# trig3_board_de0-nano_rack.net
KiCad netlist of a schematic drawn in EAGLE
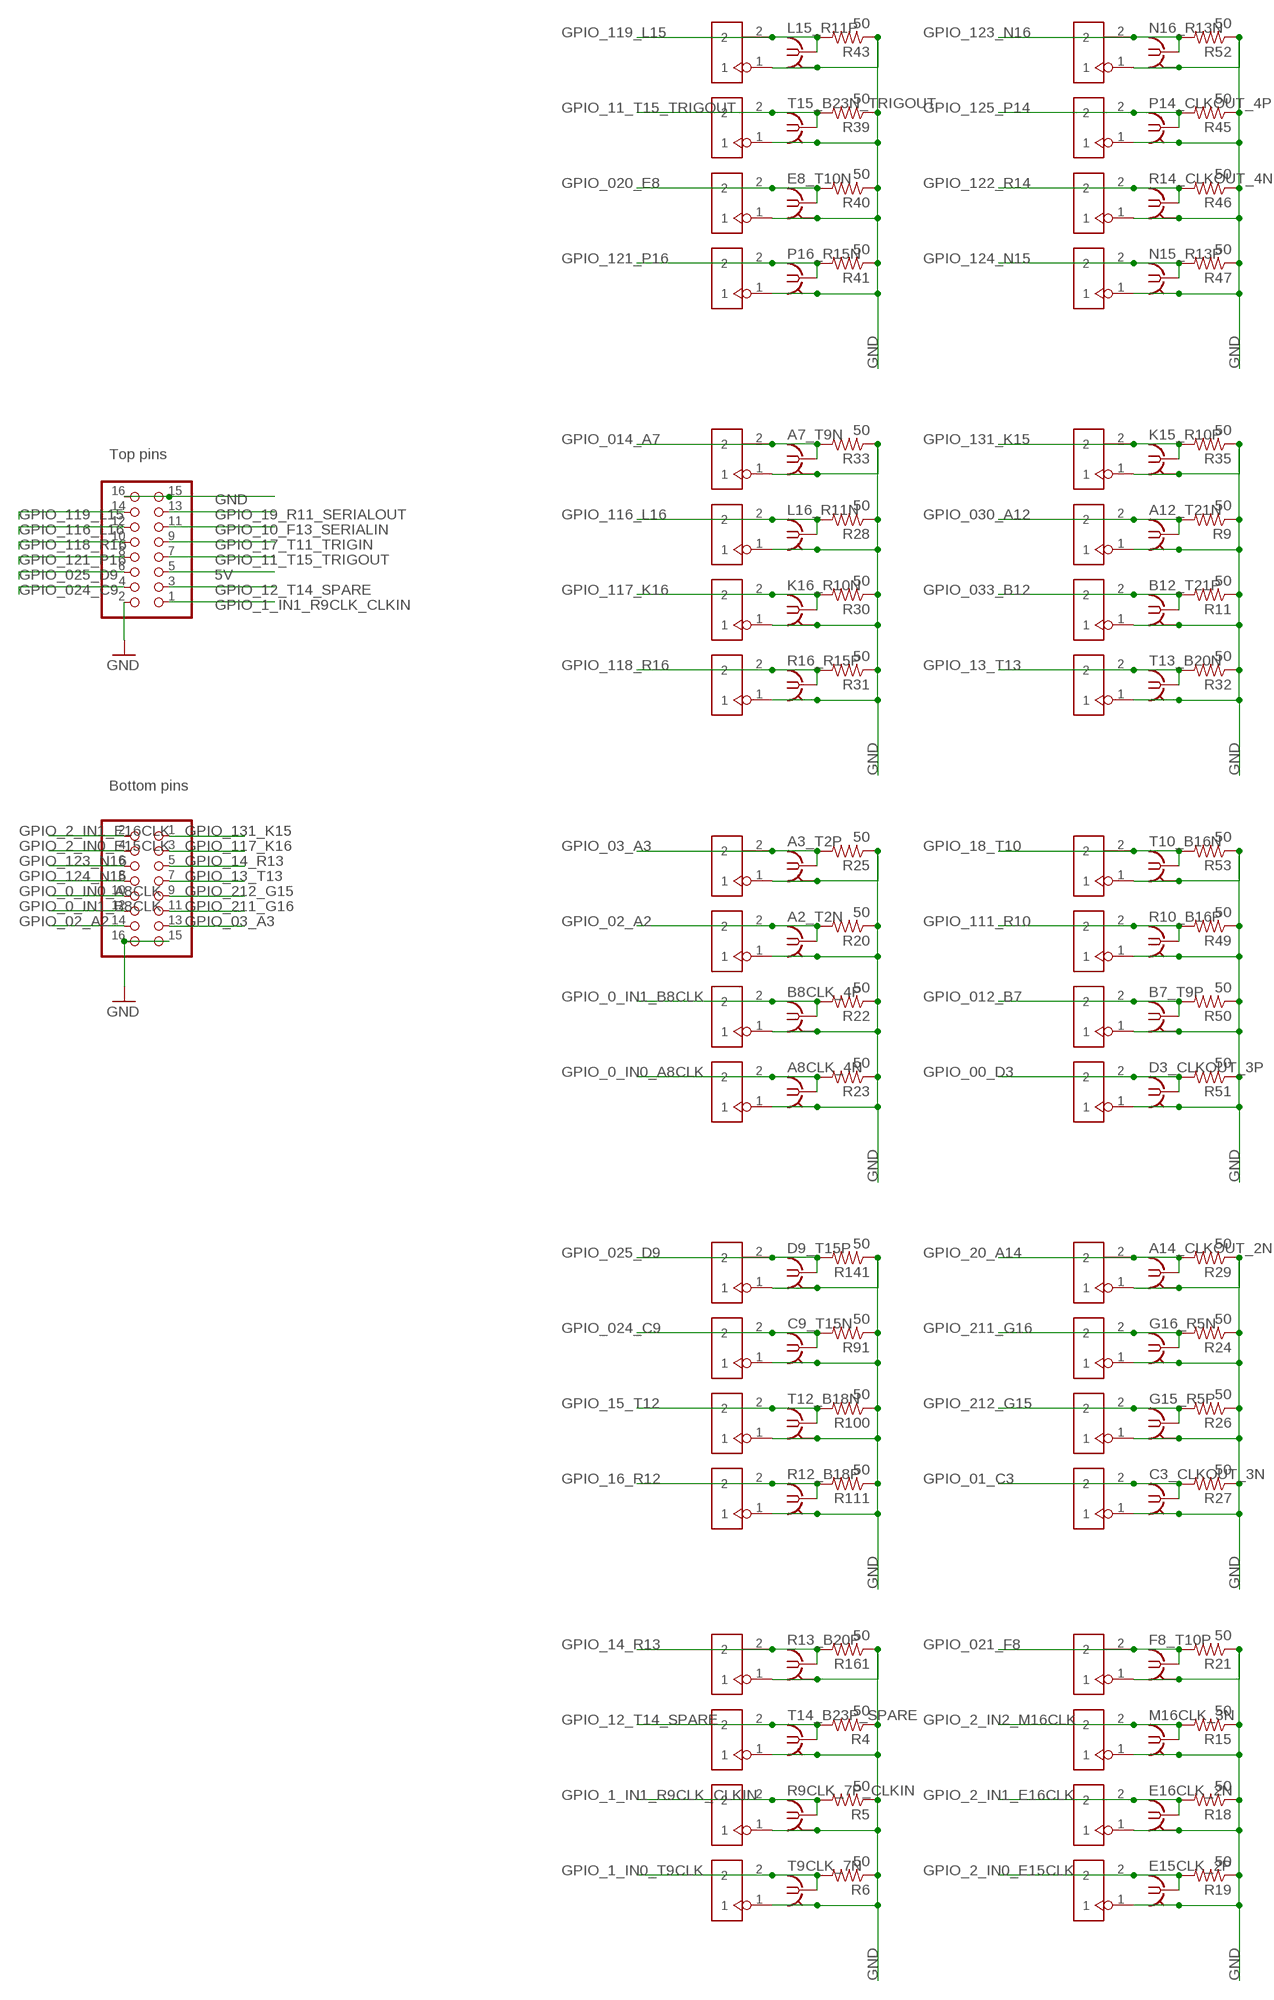
[diagram p0: schematic, sheet 1, part 1 of 3]
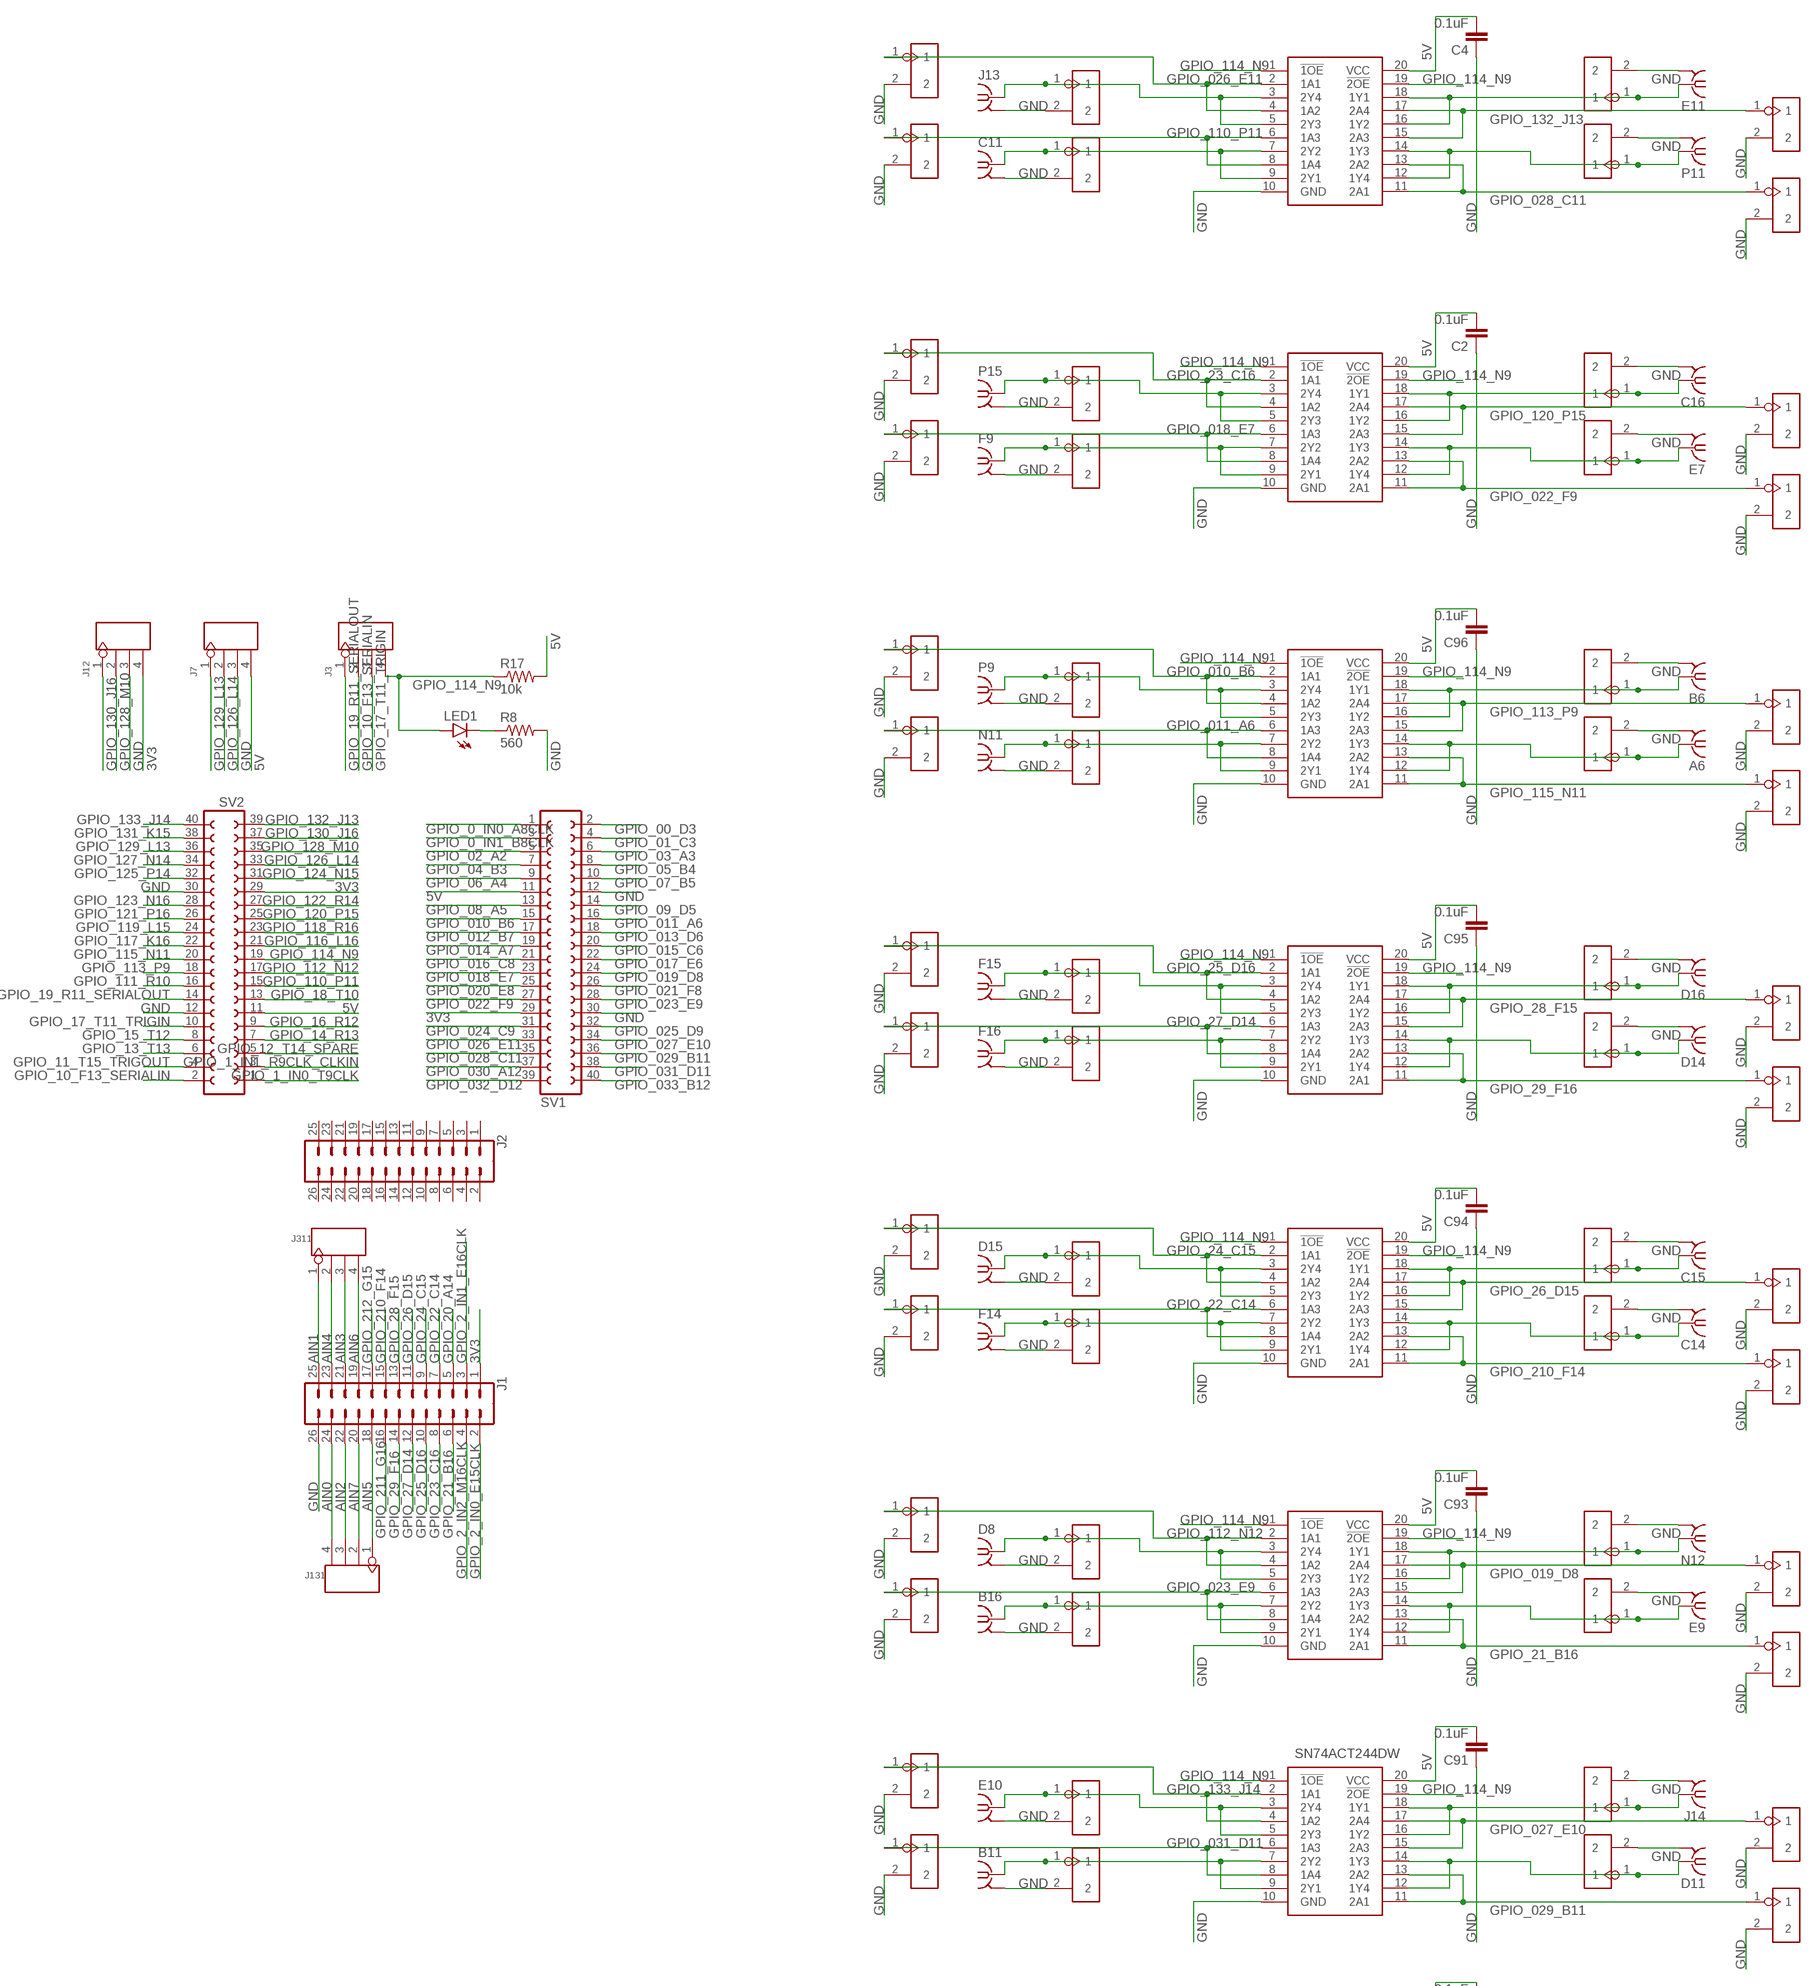
[diagram p1: schematic, sheet 1, part 2 of 3]
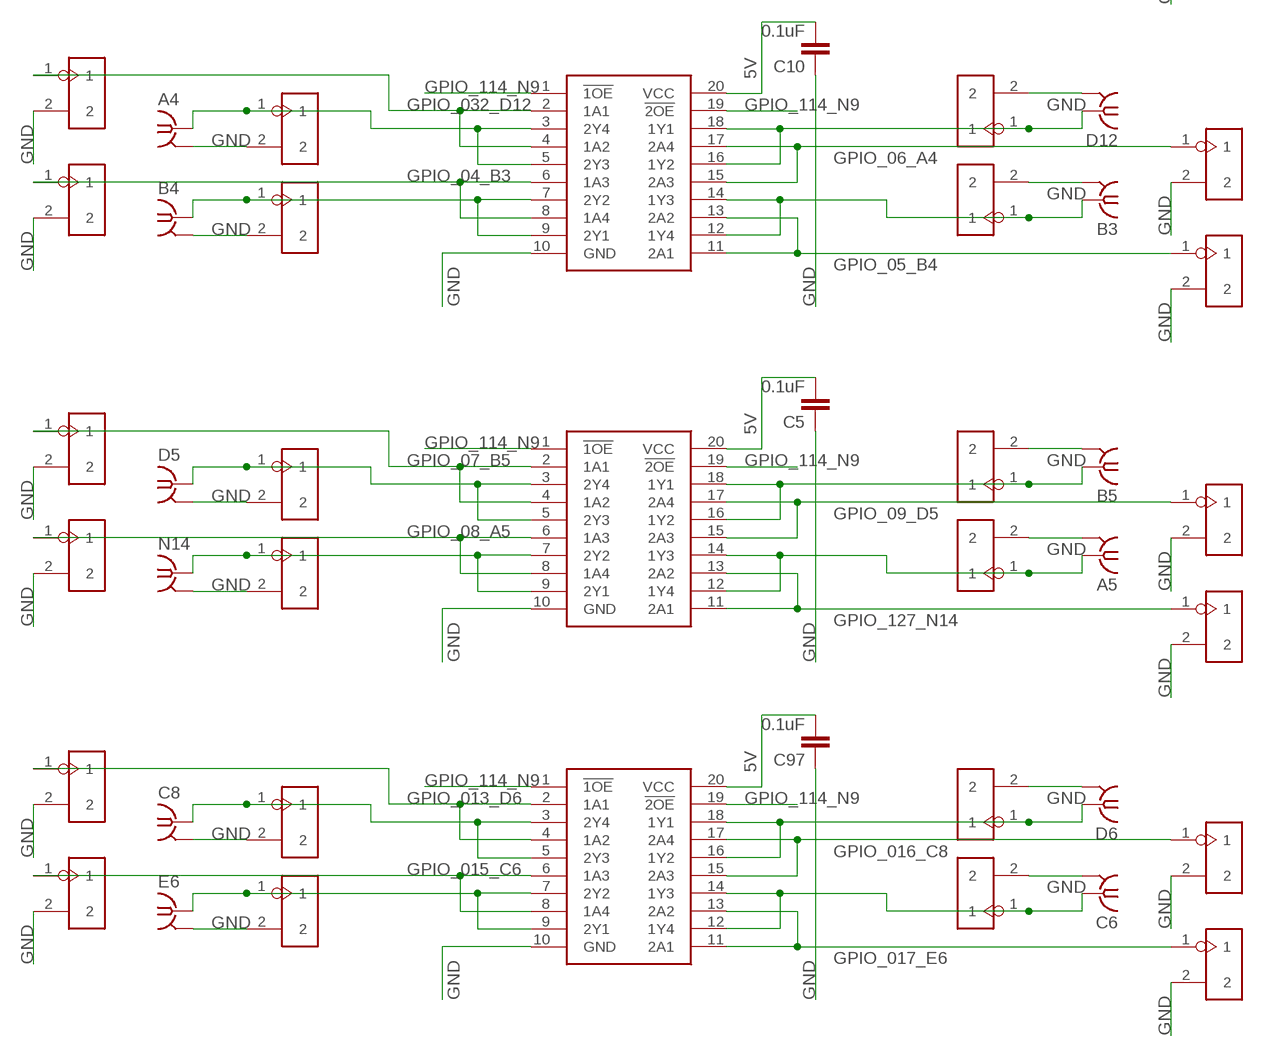
[diagram p2: schematic, sheet 1, part 3 of 3]

(export (version "E")
  (design (tool "Eeschema 10.0.6"))
  (components
    (comp (ref "A2_T2N")
      (value "BU-SMB-V")
      (footprint "eagle-import:BU-SMB-V")
      (libsource (lib "eagle-import") (part "BU-SMB-V"))
    )
    (comp (ref "A3_T2P")
      (value "BU-SMB-V")
      (footprint "eagle-import:BU-SMB-V")
      (libsource (lib "eagle-import") (part "BU-SMB-V"))
    )
    (comp (ref "A4")
      (value "BU-SMB-V")
      (footprint "eagle-import:BU-SMB-V")
      (libsource (lib "eagle-import") (part "BU-SMB-V"))
    )
    (comp (ref "A5")
      (value "BU-SMB-V")
      (footprint "eagle-import:BU-SMB-V")
      (libsource (lib "eagle-import") (part "BU-SMB-V"))
    )
    (comp (ref "A6")
      (value "BU-SMB-V")
      (footprint "eagle-import:BU-SMB-V")
      (libsource (lib "eagle-import") (part "BU-SMB-V"))
    )
    (comp (ref "A7_T9N")
      (value "BU-SMB-V")
      (footprint "eagle-import:BU-SMB-V")
      (libsource (lib "eagle-import") (part "BU-SMB-V"))
    )
    (comp (ref "A8CLK_4N")
      (value "BU-SMB-V")
      (footprint "eagle-import:BU-SMB-V")
      (libsource (lib "eagle-import") (part "BU-SMB-V"))
    )
    (comp (ref "A12_T21N")
      (value "BU-SMB-V")
      (footprint "eagle-import:BU-SMB-V")
      (libsource (lib "eagle-import") (part "BU-SMB-V"))
    )
    (comp (ref "A14_CLKOUT_2N")
      (value "BU-SMB-V")
      (footprint "eagle-import:BU-SMB-V")
      (libsource (lib "eagle-import") (part "BU-SMB-V"))
    )
    (comp (ref "B3")
      (value "BU-SMB-V")
      (footprint "eagle-import:BU-SMB-V")
      (libsource (lib "eagle-import") (part "BU-SMB-V"))
    )
    (comp (ref "B4")
      (value "BU-SMB-V")
      (footprint "eagle-import:BU-SMB-V")
      (libsource (lib "eagle-import") (part "BU-SMB-V"))
    )
    (comp (ref "B5")
      (value "BU-SMB-V")
      (footprint "eagle-import:BU-SMB-V")
      (libsource (lib "eagle-import") (part "BU-SMB-V"))
    )
    (comp (ref "B6")
      (value "BU-SMB-V")
      (footprint "eagle-import:BU-SMB-V")
      (libsource (lib "eagle-import") (part "BU-SMB-V"))
    )
    (comp (ref "B7_T9P")
      (value "BU-SMB-V")
      (footprint "eagle-import:BU-SMB-V")
      (libsource (lib "eagle-import") (part "BU-SMB-V"))
    )
    (comp (ref "B8CLK_4P")
      (value "BU-SMB-V")
      (footprint "eagle-import:BU-SMB-V")
      (libsource (lib "eagle-import") (part "BU-SMB-V"))
    )
    (comp (ref "B11")
      (value "BU-SMB-V")
      (footprint "eagle-import:BU-SMB-V")
      (libsource (lib "eagle-import") (part "BU-SMB-V"))
    )
    (comp (ref "B12_T21P")
      (value "BU-SMB-V")
      (footprint "eagle-import:BU-SMB-V")
      (libsource (lib "eagle-import") (part "BU-SMB-V"))
    )
    (comp (ref "B16")
      (value "BU-SMB-V")
      (footprint "eagle-import:BU-SMB-V")
      (libsource (lib "eagle-import") (part "BU-SMB-V"))
    )
    (comp (ref "C2")
      (value "0.1uF")
      (footprint "eagle-import:0805")
      (libsource (lib "eagle-import") (part "CAP0805"))
    )
    (comp (ref "C3_CLKOUT_3N")
      (value "BU-SMB-V")
      (footprint "eagle-import:BU-SMB-V")
      (libsource (lib "eagle-import") (part "BU-SMB-V"))
    )
    (comp (ref "C4")
      (value "0.1uF")
      (footprint "eagle-import:0805")
      (libsource (lib "eagle-import") (part "CAP0805"))
    )
    (comp (ref "C5")
      (value "0.1uF")
      (footprint "eagle-import:0805")
      (libsource (lib "eagle-import") (part "CAP0805"))
    )
    (comp (ref "C6")
      (value "BU-SMB-V")
      (footprint "eagle-import:BU-SMB-V")
      (libsource (lib "eagle-import") (part "BU-SMB-V"))
    )
    (comp (ref "C8")
      (value "BU-SMB-V")
      (footprint "eagle-import:BU-SMB-V")
      (libsource (lib "eagle-import") (part "BU-SMB-V"))
    )
    (comp (ref "C9_T15N")
      (value "BU-SMB-V")
      (footprint "eagle-import:BU-SMB-V")
      (libsource (lib "eagle-import") (part "BU-SMB-V"))
    )
    (comp (ref "C10")
      (value "0.1uF")
      (footprint "eagle-import:0805")
      (libsource (lib "eagle-import") (part "CAP0805"))
    )
    (comp (ref "C11")
      (value "BU-SMB-V")
      (footprint "eagle-import:BU-SMB-V")
      (libsource (lib "eagle-import") (part "BU-SMB-V"))
    )
    (comp (ref "C14")
      (value "BU-SMB-V")
      (footprint "eagle-import:BU-SMB-V")
      (libsource (lib "eagle-import") (part "BU-SMB-V"))
    )
    (comp (ref "C15")
      (value "BU-SMB-V")
      (footprint "eagle-import:BU-SMB-V")
      (libsource (lib "eagle-import") (part "BU-SMB-V"))
    )
    (comp (ref "C16")
      (value "BU-SMB-V")
      (footprint "eagle-import:BU-SMB-V")
      (libsource (lib "eagle-import") (part "BU-SMB-V"))
    )
    (comp (ref "C91")
      (value "0.1uF")
      (footprint "eagle-import:0805")
      (libsource (lib "eagle-import") (part "CAP0805"))
    )
    (comp (ref "C93")
      (value "0.1uF")
      (footprint "eagle-import:0805")
      (libsource (lib "eagle-import") (part "CAP0805"))
    )
    (comp (ref "C94")
      (value "0.1uF")
      (footprint "eagle-import:0805")
      (libsource (lib "eagle-import") (part "CAP0805"))
    )
    (comp (ref "C95")
      (value "0.1uF")
      (footprint "eagle-import:0805")
      (libsource (lib "eagle-import") (part "CAP0805"))
    )
    (comp (ref "C96")
      (value "0.1uF")
      (footprint "eagle-import:0805")
      (libsource (lib "eagle-import") (part "CAP0805"))
    )
    (comp (ref "C97")
      (value "0.1uF")
      (footprint "eagle-import:0805")
      (libsource (lib "eagle-import") (part "CAP0805"))
    )
    (comp (ref "D3_CLKOUT_3P")
      (value "BU-SMB-V")
      (footprint "eagle-import:BU-SMB-V")
      (libsource (lib "eagle-import") (part "BU-SMB-V"))
    )
    (comp (ref "D5")
      (value "BU-SMB-V")
      (footprint "eagle-import:BU-SMB-V")
      (libsource (lib "eagle-import") (part "BU-SMB-V"))
    )
    (comp (ref "D6")
      (value "BU-SMB-V")
      (footprint "eagle-import:BU-SMB-V")
      (libsource (lib "eagle-import") (part "BU-SMB-V"))
    )
    (comp (ref "D8")
      (value "BU-SMB-V")
      (footprint "eagle-import:BU-SMB-V")
      (libsource (lib "eagle-import") (part "BU-SMB-V"))
    )
    (comp (ref "D9_T15P")
      (value "BU-SMB-V")
      (footprint "eagle-import:BU-SMB-V")
      (libsource (lib "eagle-import") (part "BU-SMB-V"))
    )
    (comp (ref "D11")
      (value "BU-SMB-V")
      (footprint "eagle-import:BU-SMB-V")
      (libsource (lib "eagle-import") (part "BU-SMB-V"))
    )
    (comp (ref "D12")
      (value "BU-SMB-V")
      (footprint "eagle-import:BU-SMB-V")
      (libsource (lib "eagle-import") (part "BU-SMB-V"))
    )
    (comp (ref "D14")
      (value "BU-SMB-V")
      (footprint "eagle-import:BU-SMB-V")
      (libsource (lib "eagle-import") (part "BU-SMB-V"))
    )
    (comp (ref "D15")
      (value "BU-SMB-V")
      (footprint "eagle-import:BU-SMB-V")
      (libsource (lib "eagle-import") (part "BU-SMB-V"))
    )
    (comp (ref "D16")
      (value "BU-SMB-V")
      (footprint "eagle-import:BU-SMB-V")
      (libsource (lib "eagle-import") (part "BU-SMB-V"))
    )
    (comp (ref "E6")
      (value "BU-SMB-V")
      (footprint "eagle-import:BU-SMB-V")
      (libsource (lib "eagle-import") (part "BU-SMB-V"))
    )
    (comp (ref "E7")
      (value "BU-SMB-V")
      (footprint "eagle-import:BU-SMB-V")
      (libsource (lib "eagle-import") (part "BU-SMB-V"))
    )
    (comp (ref "E8_T10N")
      (value "BU-SMB-V")
      (footprint "eagle-import:BU-SMB-V")
      (libsource (lib "eagle-import") (part "BU-SMB-V"))
    )
    (comp (ref "E9")
      (value "BU-SMB-V")
      (footprint "eagle-import:BU-SMB-V")
      (libsource (lib "eagle-import") (part "BU-SMB-V"))
    )
    (comp (ref "E10")
      (value "BU-SMB-V")
      (footprint "eagle-import:BU-SMB-V")
      (libsource (lib "eagle-import") (part "BU-SMB-V"))
    )
    (comp (ref "E11")
      (value "BU-SMB-V")
      (footprint "eagle-import:BU-SMB-V")
      (libsource (lib "eagle-import") (part "BU-SMB-V"))
    )
    (comp (ref "E15CLK_2P")
      (value "BU-SMB-V")
      (footprint "eagle-import:BU-SMB-V")
      (libsource (lib "eagle-import") (part "BU-SMB-V"))
    )
    (comp (ref "E16CLK_2N")
      (value "BU-SMB-V")
      (footprint "eagle-import:BU-SMB-V")
      (libsource (lib "eagle-import") (part "BU-SMB-V"))
    )
    (comp (ref "F8_T10P")
      (value "BU-SMB-V")
      (footprint "eagle-import:BU-SMB-V")
      (libsource (lib "eagle-import") (part "BU-SMB-V"))
    )
    (comp (ref "F9")
      (value "BU-SMB-V")
      (footprint "eagle-import:BU-SMB-V")
      (libsource (lib "eagle-import") (part "BU-SMB-V"))
    )
    (comp (ref "F14")
      (value "BU-SMB-V")
      (footprint "eagle-import:BU-SMB-V")
      (libsource (lib "eagle-import") (part "BU-SMB-V"))
    )
    (comp (ref "F15")
      (value "BU-SMB-V")
      (footprint "eagle-import:BU-SMB-V")
      (libsource (lib "eagle-import") (part "BU-SMB-V"))
    )
    (comp (ref "F16")
      (value "BU-SMB-V")
      (footprint "eagle-import:BU-SMB-V")
      (libsource (lib "eagle-import") (part "BU-SMB-V"))
    )
    (comp (ref "G15_R5P")
      (value "BU-SMB-V")
      (footprint "eagle-import:BU-SMB-V")
      (libsource (lib "eagle-import") (part "BU-SMB-V"))
    )
    (comp (ref "G16_R5N")
      (value "BU-SMB-V")
      (footprint "eagle-import:BU-SMB-V")
      (libsource (lib "eagle-import") (part "BU-SMB-V"))
    )
    (comp (ref "J1")
      (value "M13X22X13")
      (footprint "eagle-import:2X13")
      (libsource (lib "eagle-import") (part "M13X22X13"))
    )
    (comp (ref "J2")
      (value "M13X22X13")
      (footprint "eagle-import:2X13")
      (libsource (lib "eagle-import") (part "M13X22X13"))
    )
    (comp (ref "J3")
      (value "4p-2.54")
      (footprint "eagle-import:H4-2.54")
      (fields (field (name "MPN") "F185-1104A1BSYA1"))
      (libsource (lib "eagle-import") (part "DIP-BLACK-FEMALE-HEADER-VERT(4P-2.54)"))
    )
    (comp (ref "J4")
      (value "2p-2.54")
      (footprint "eagle-import:H2-2.54")
      (fields (field (name "MPN") "P125-1102A0BS116A1"))
      (libsource (lib "eagle-import") (part "DIP-BLACK-MALE-HEADER-VERT(2P-2.54)"))
    )
    (comp (ref "J5")
      (value "2p-2.54")
      (footprint "eagle-import:H2-2.54")
      (fields (field (name "MPN") "P125-1102A0BS116A1"))
      (libsource (lib "eagle-import") (part "DIP-BLACK-MALE-HEADER-VERT(2P-2.54)"))
    )
    (comp (ref "J6")
      (value "2p-2.54")
      (footprint "eagle-import:H2-2.54")
      (fields (field (name "MPN") "P125-1102A0BS116A1"))
      (libsource (lib "eagle-import") (part "DIP-BLACK-MALE-HEADER-VERT(2P-2.54)"))
    )
    (comp (ref "J7")
      (value "4p-2.54")
      (footprint "eagle-import:H4-2.54")
      (fields (field (name "MPN") "F185-1104A1BSYA1"))
      (libsource (lib "eagle-import") (part "DIP-BLACK-FEMALE-HEADER-VERT(4P-2.54)"))
    )
    (comp (ref "J8")
      (value "2p-2.54")
      (footprint "eagle-import:H2-2.54")
      (fields (field (name "MPN") "P125-1102A0BS116A1"))
      (libsource (lib "eagle-import") (part "DIP-BLACK-MALE-HEADER-VERT(2P-2.54)"))
    )
    (comp (ref "J9")
      (value "2p-2.54")
      (footprint "eagle-import:H2-2.54")
      (fields (field (name "MPN") "P125-1102A0BS116A1"))
      (libsource (lib "eagle-import") (part "DIP-BLACK-MALE-HEADER-VERT(2P-2.54)"))
    )
    (comp (ref "J10")
      (value "2p-2.54")
      (footprint "eagle-import:H2-2.54")
      (fields (field (name "MPN") "P125-1102A0BS116A1"))
      (libsource (lib "eagle-import") (part "DIP-BLACK-MALE-HEADER-VERT(2P-2.54)"))
    )
    (comp (ref "J11")
      (value "2p-2.54")
      (footprint "eagle-import:H2-2.54")
      (fields (field (name "MPN") "P125-1102A0BS116A1"))
      (libsource (lib "eagle-import") (part "DIP-BLACK-MALE-HEADER-VERT(2P-2.54)"))
    )
    (comp (ref "J12")
      (value "4p-2.54")
      (footprint "eagle-import:H4-2.54")
      (fields (field (name "MPN") "F185-1104A1BSYA1"))
      (libsource (lib "eagle-import") (part "DIP-BLACK-FEMALE-HEADER-VERT(4P-2.54)"))
    )
    (comp (ref "J13")
      (value "BU-SMB-V")
      (footprint "eagle-import:BU-SMB-V")
      (libsource (lib "eagle-import") (part "BU-SMB-V"))
    )
    (comp (ref "J14")
      (value "BU-SMB-V")
      (footprint "eagle-import:BU-SMB-V")
      (libsource (lib "eagle-import") (part "BU-SMB-V"))
    )
    (comp (ref "J15")
      (value "2p-2.54")
      (footprint "eagle-import:H2-2.54")
      (fields (field (name "MPN") "P125-1102A0BS116A1"))
      (libsource (lib "eagle-import") (part "DIP-BLACK-MALE-HEADER-VERT(2P-2.54)"))
    )
    (comp (ref "J16")
      (value "2p-2.54")
      (footprint "eagle-import:H2-2.54")
      (fields (field (name "MPN") "P125-1102A0BS116A1"))
      (libsource (lib "eagle-import") (part "DIP-BLACK-MALE-HEADER-VERT(2P-2.54)"))
    )
    (comp (ref "J17")
      (value "2p-2.54")
      (footprint "eagle-import:H2-2.54")
      (fields (field (name "MPN") "P125-1102A0BS116A1"))
      (libsource (lib "eagle-import") (part "DIP-BLACK-MALE-HEADER-VERT(2P-2.54)"))
    )
    (comp (ref "J18")
      (value "2p-2.54")
      (footprint "eagle-import:H2-2.54")
      (fields (field (name "MPN") "P125-1102A0BS116A1"))
      (libsource (lib "eagle-import") (part "DIP-BLACK-MALE-HEADER-VERT(2P-2.54)"))
    )
    (comp (ref "J22")
      (value "2p-2.54")
      (footprint "eagle-import:H2-2.54")
      (fields (field (name "MPN") "P125-1102A0BS116A1"))
      (libsource (lib "eagle-import") (part "DIP-BLACK-MALE-HEADER-VERT(2P-2.54)"))
    )
    (comp (ref "J23")
      (value "2p-2.54")
      (footprint "eagle-import:H2-2.54")
      (fields (field (name "MPN") "P125-1102A0BS116A1"))
      (libsource (lib "eagle-import") (part "DIP-BLACK-MALE-HEADER-VERT(2P-2.54)"))
    )
    (comp (ref "J24")
      (value "2p-2.54")
      (footprint "eagle-import:H2-2.54")
      (fields (field (name "MPN") "P125-1102A0BS116A1"))
      (libsource (lib "eagle-import") (part "DIP-BLACK-MALE-HEADER-VERT(2P-2.54)"))
    )
    (comp (ref "J25")
      (value "2p-2.54")
      (footprint "eagle-import:H2-2.54")
      (fields (field (name "MPN") "P125-1102A0BS116A1"))
      (libsource (lib "eagle-import") (part "DIP-BLACK-MALE-HEADER-VERT(2P-2.54)"))
    )
    (comp (ref "J28")
      (value "2p-2.54")
      (footprint "eagle-import:H2-2.54")
      (fields (field (name "MPN") "P125-1102A0BS116A1"))
      (libsource (lib "eagle-import") (part "DIP-BLACK-MALE-HEADER-VERT(2P-2.54)"))
    )
    (comp (ref "J29")
      (value "2p-2.54")
      (footprint "eagle-import:H2-2.54")
      (fields (field (name "MPN") "P125-1102A0BS116A1"))
      (libsource (lib "eagle-import") (part "DIP-BLACK-MALE-HEADER-VERT(2P-2.54)"))
    )
    (comp (ref "J30")
      (value "2p-2.54")
      (footprint "eagle-import:H2-2.54")
      (fields (field (name "MPN") "P125-1102A0BS116A1"))
      (libsource (lib "eagle-import") (part "DIP-BLACK-MALE-HEADER-VERT(2P-2.54)"))
    )
    (comp (ref "J31")
      (value "2p-2.54")
      (footprint "eagle-import:H2-2.54")
      (fields (field (name "MPN") "P125-1102A0BS116A1"))
      (libsource (lib "eagle-import") (part "DIP-BLACK-MALE-HEADER-VERT(2P-2.54)"))
    )
    (comp (ref "J32")
      (value "2p-2.54")
      (footprint "eagle-import:H2-2.54")
      (fields (field (name "MPN") "P125-1102A0BS116A1"))
      (libsource (lib "eagle-import") (part "DIP-BLACK-MALE-HEADER-VERT(2P-2.54)"))
    )
    (comp (ref "J33")
      (value "2p-2.54")
      (footprint "eagle-import:H2-2.54")
      (fields (field (name "MPN") "P125-1102A0BS116A1"))
      (libsource (lib "eagle-import") (part "DIP-BLACK-MALE-HEADER-VERT(2P-2.54)"))
    )
    (comp (ref "J34")
      (value "2p-2.54")
      (footprint "eagle-import:H2-2.54")
      (fields (field (name "MPN") "P125-1102A0BS116A1"))
      (libsource (lib "eagle-import") (part "DIP-BLACK-MALE-HEADER-VERT(2P-2.54)"))
    )
    (comp (ref "J35")
      (value "2p-2.54")
      (footprint "eagle-import:H2-2.54")
      (fields (field (name "MPN") "P125-1102A0BS116A1"))
      (libsource (lib "eagle-import") (part "DIP-BLACK-MALE-HEADER-VERT(2P-2.54)"))
    )
    (comp (ref "J36")
      (value "2p-2.54")
      (footprint "eagle-import:H2-2.54")
      (fields (field (name "MPN") "P125-1102A0BS116A1"))
      (libsource (lib "eagle-import") (part "DIP-BLACK-MALE-HEADER-VERT(2P-2.54)"))
    )
    (comp (ref "J37")
      (value "2p-2.54")
      (footprint "eagle-import:H2-2.54")
      (fields (field (name "MPN") "P125-1102A0BS116A1"))
      (libsource (lib "eagle-import") (part "DIP-BLACK-MALE-HEADER-VERT(2P-2.54)"))
    )
    (comp (ref "J38")
      (value "2p-2.54")
      (footprint "eagle-import:H2-2.54")
      (fields (field (name "MPN") "P125-1102A0BS116A1"))
      (libsource (lib "eagle-import") (part "DIP-BLACK-MALE-HEADER-VERT(2P-2.54)"))
    )
    (comp (ref "J39")
      (value "2p-2.54")
      (footprint "eagle-import:H2-2.54")
      (fields (field (name "MPN") "P125-1102A0BS116A1"))
      (libsource (lib "eagle-import") (part "DIP-BLACK-MALE-HEADER-VERT(2P-2.54)"))
    )
    (comp (ref "J40")
      (value "2p-2.54")
      (footprint "eagle-import:H2-2.54")
      (fields (field (name "MPN") "P125-1102A0BS116A1"))
      (libsource (lib "eagle-import") (part "DIP-BLACK-MALE-HEADER-VERT(2P-2.54)"))
    )
    (comp (ref "J41")
      (value "2p-2.54")
      (footprint "eagle-import:H2-2.54")
      (fields (field (name "MPN") "P125-1102A0BS116A1"))
      (libsource (lib "eagle-import") (part "DIP-BLACK-MALE-HEADER-VERT(2P-2.54)"))
    )
    (comp (ref "J42")
      (value "2p-2.54")
      (footprint "eagle-import:H2-2.54")
      (fields (field (name "MPN") "P125-1102A0BS116A1"))
      (libsource (lib "eagle-import") (part "DIP-BLACK-MALE-HEADER-VERT(2P-2.54)"))
    )
    (comp (ref "J43")
      (value "2p-2.54")
      (footprint "eagle-import:H2-2.54")
      (fields (field (name "MPN") "P125-1102A0BS116A1"))
      (libsource (lib "eagle-import") (part "DIP-BLACK-MALE-HEADER-VERT(2P-2.54)"))
    )
    (comp (ref "J48")
      (value "2p-2.54")
      (footprint "eagle-import:H2-2.54")
      (fields (field (name "MPN") "P125-1102A0BS116A1"))
      (libsource (lib "eagle-import") (part "DIP-BLACK-MALE-HEADER-VERT(2P-2.54)"))
    )
    (comp (ref "J49")
      (value "2p-2.54")
      (footprint "eagle-import:H2-2.54")
      (fields (field (name "MPN") "P125-1102A0BS116A1"))
      (libsource (lib "eagle-import") (part "DIP-BLACK-MALE-HEADER-VERT(2P-2.54)"))
    )
    (comp (ref "J50")
      (value "2p-2.54")
      (footprint "eagle-import:H2-2.54")
      (fields (field (name "MPN") "P125-1102A0BS116A1"))
      (libsource (lib "eagle-import") (part "DIP-BLACK-MALE-HEADER-VERT(2P-2.54)"))
    )
    (comp (ref "J51")
      (value "2p-2.54")
      (footprint "eagle-import:H2-2.54")
      (fields (field (name "MPN") "P125-1102A0BS116A1"))
      (libsource (lib "eagle-import") (part "DIP-BLACK-MALE-HEADER-VERT(2P-2.54)"))
    )
    (comp (ref "J52")
      (value "2p-2.54")
      (footprint "eagle-import:H2-2.54")
      (fields (field (name "MPN") "P125-1102A0BS116A1"))
      (libsource (lib "eagle-import") (part "DIP-BLACK-MALE-HEADER-VERT(2P-2.54)"))
    )
    (comp (ref "J53")
      (value "2p-2.54")
      (footprint "eagle-import:H2-2.54")
      (fields (field (name "MPN") "P125-1102A0BS116A1"))
      (libsource (lib "eagle-import") (part "DIP-BLACK-MALE-HEADER-VERT(2P-2.54)"))
    )
    (comp (ref "J54")
      (value "2p-2.54")
      (footprint "eagle-import:H2-2.54")
      (fields (field (name "MPN") "P125-1102A0BS116A1"))
      (libsource (lib "eagle-import") (part "DIP-BLACK-MALE-HEADER-VERT(2P-2.54)"))
    )
    (comp (ref "J55")
      (value "2p-2.54")
      (footprint "eagle-import:H2-2.54")
      (fields (field (name "MPN") "P125-1102A0BS116A1"))
      (libsource (lib "eagle-import") (part "DIP-BLACK-MALE-HEADER-VERT(2P-2.54)"))
    )
    (comp (ref "J131")
      (value "4p-2.54")
      (footprint "eagle-import:H4-2.54")
      (fields (field (name "MPN") "F185-1104A1BSYA1"))
      (libsource (lib "eagle-import") (part "DIP-BLACK-FEMALE-HEADER-VERT(4P-2.54)"))
    )
    (comp (ref "J141")
      (value "2p-2.54")
      (footprint "eagle-import:H2-2.54")
      (fields (field (name "MPN") "P125-1102A0BS116A1"))
      (libsource (lib "eagle-import") (part "DIP-BLACK-MALE-HEADER-VERT(2P-2.54)"))
    )
    (comp (ref "J311")
      (value "4p-2.54")
      (footprint "eagle-import:H4-2.54")
      (fields (field (name "MPN") "F185-1104A1BSYA1"))
      (libsource (lib "eagle-import") (part "DIP-BLACK-FEMALE-HEADER-VERT(4P-2.54)"))
    )
    (comp (ref "K15_R10P")
      (value "BU-SMB-V")
      (footprint "eagle-import:BU-SMB-V")
      (libsource (lib "eagle-import") (part "BU-SMB-V"))
    )
    (comp (ref "K16_R10N")
      (value "BU-SMB-V")
      (footprint "eagle-import:BU-SMB-V")
      (libsource (lib "eagle-import") (part "BU-SMB-V"))
    )
    (comp (ref "L15_R11P")
      (value "BU-SMB-V")
      (footprint "eagle-import:BU-SMB-V")
      (libsource (lib "eagle-import") (part "BU-SMB-V"))
    )
    (comp (ref "L16_R11N")
      (value "BU-SMB-V")
      (footprint "eagle-import:BU-SMB-V")
      (libsource (lib "eagle-import") (part "BU-SMB-V"))
    )
    (comp (ref "LED1")
      (value "red")
      (footprint "eagle-import:CHIP-LED0805")
      (libsource (lib "eagle-import") (part "LEDCHIP-LED0805"))
    )
    (comp (ref "M16CLK_3N")
      (value "BU-SMB-V")
      (footprint "eagle-import:BU-SMB-V")
      (libsource (lib "eagle-import") (part "BU-SMB-V"))
    )
    (comp (ref "N11")
      (value "BU-SMB-V")
      (footprint "eagle-import:BU-SMB-V")
      (libsource (lib "eagle-import") (part "BU-SMB-V"))
    )
    (comp (ref "N12")
      (value "BU-SMB-V")
      (footprint "eagle-import:BU-SMB-V")
      (libsource (lib "eagle-import") (part "BU-SMB-V"))
    )
    (comp (ref "N14")
      (value "BU-SMB-V")
      (footprint "eagle-import:BU-SMB-V")
      (libsource (lib "eagle-import") (part "BU-SMB-V"))
    )
    (comp (ref "N15_R13P")
      (value "BU-SMB-V")
      (footprint "eagle-import:BU-SMB-V")
      (libsource (lib "eagle-import") (part "BU-SMB-V"))
    )
    (comp (ref "N16_R13N")
      (value "BU-SMB-V")
      (footprint "eagle-import:BU-SMB-V")
      (libsource (lib "eagle-import") (part "BU-SMB-V"))
    )
    (comp (ref "OJ1")
      (value "2p-2.54")
      (footprint "eagle-import:H2-2.54")
      (fields (field (name "MPN") "P125-1102A0BS116A1"))
      (libsource (lib "eagle-import") (part "DIP-BLACK-MALE-HEADER-VERT(2P-2.54)"))
    )
    (comp (ref "OJ2")
      (value "2p-2.54")
      (footprint "eagle-import:H2-2.54")
      (fields (field (name "MPN") "P125-1102A0BS116A1"))
      (libsource (lib "eagle-import") (part "DIP-BLACK-MALE-HEADER-VERT(2P-2.54)"))
    )
    (comp (ref "OJ3")
      (value "2p-2.54")
      (footprint "eagle-import:H2-2.54")
      (fields (field (name "MPN") "P125-1102A0BS116A1"))
      (libsource (lib "eagle-import") (part "DIP-BLACK-MALE-HEADER-VERT(2P-2.54)"))
    )
    (comp (ref "OJ4")
      (value "2p-2.54")
      (footprint "eagle-import:H2-2.54")
      (fields (field (name "MPN") "P125-1102A0BS116A1"))
      (libsource (lib "eagle-import") (part "DIP-BLACK-MALE-HEADER-VERT(2P-2.54)"))
    )
    (comp (ref "OJ5")
      (value "2p-2.54")
      (footprint "eagle-import:H2-2.54")
      (fields (field (name "MPN") "P125-1102A0BS116A1"))
      (libsource (lib "eagle-import") (part "DIP-BLACK-MALE-HEADER-VERT(2P-2.54)"))
    )
    (comp (ref "OJ6")
      (value "2p-2.54")
      (footprint "eagle-import:H2-2.54")
      (fields (field (name "MPN") "P125-1102A0BS116A1"))
      (libsource (lib "eagle-import") (part "DIP-BLACK-MALE-HEADER-VERT(2P-2.54)"))
    )
    (comp (ref "OJ7")
      (value "2p-2.54")
      (footprint "eagle-import:H2-2.54")
      (fields (field (name "MPN") "P125-1102A0BS116A1"))
      (libsource (lib "eagle-import") (part "DIP-BLACK-MALE-HEADER-VERT(2P-2.54)"))
    )
    (comp (ref "OJ8")
      (value "2p-2.54")
      (footprint "eagle-import:H2-2.54")
      (fields (field (name "MPN") "P125-1102A0BS116A1"))
      (libsource (lib "eagle-import") (part "DIP-BLACK-MALE-HEADER-VERT(2P-2.54)"))
    )
    (comp (ref "OJ17")
      (value "2p-2.54")
      (footprint "eagle-import:H2-2.54")
      (fields (field (name "MPN") "P125-1102A0BS116A1"))
      (libsource (lib "eagle-import") (part "DIP-BLACK-MALE-HEADER-VERT(2P-2.54)"))
    )
    (comp (ref "OJ18")
      (value "2p-2.54")
      (footprint "eagle-import:H2-2.54")
      (fields (field (name "MPN") "P125-1102A0BS116A1"))
      (libsource (lib "eagle-import") (part "DIP-BLACK-MALE-HEADER-VERT(2P-2.54)"))
    )
    (comp (ref "OJ19")
      (value "2p-2.54")
      (footprint "eagle-import:H2-2.54")
      (fields (field (name "MPN") "P125-1102A0BS116A1"))
      (libsource (lib "eagle-import") (part "DIP-BLACK-MALE-HEADER-VERT(2P-2.54)"))
    )
    (comp (ref "OJ20")
      (value "2p-2.54")
      (footprint "eagle-import:H2-2.54")
      (fields (field (name "MPN") "P125-1102A0BS116A1"))
      (libsource (lib "eagle-import") (part "DIP-BLACK-MALE-HEADER-VERT(2P-2.54)"))
    )
    (comp (ref "OJ21")
      (value "2p-2.54")
      (footprint "eagle-import:H2-2.54")
      (fields (field (name "MPN") "P125-1102A0BS116A1"))
      (libsource (lib "eagle-import") (part "DIP-BLACK-MALE-HEADER-VERT(2P-2.54)"))
    )
    (comp (ref "OJ22")
      (value "2p-2.54")
      (footprint "eagle-import:H2-2.54")
      (fields (field (name "MPN") "P125-1102A0BS116A1"))
      (libsource (lib "eagle-import") (part "DIP-BLACK-MALE-HEADER-VERT(2P-2.54)"))
    )
    (comp (ref "OJ23")
      (value "2p-2.54")
      (footprint "eagle-import:H2-2.54")
      (fields (field (name "MPN") "P125-1102A0BS116A1"))
      (libsource (lib "eagle-import") (part "DIP-BLACK-MALE-HEADER-VERT(2P-2.54)"))
    )
    (comp (ref "OJ24")
      (value "2p-2.54")
      (footprint "eagle-import:H2-2.54")
      (fields (field (name "MPN") "P125-1102A0BS116A1"))
      (libsource (lib "eagle-import") (part "DIP-BLACK-MALE-HEADER-VERT(2P-2.54)"))
    )
    (comp (ref "OJ25")
      (value "2p-2.54")
      (footprint "eagle-import:H2-2.54")
      (fields (field (name "MPN") "P125-1102A0BS116A1"))
      (libsource (lib "eagle-import") (part "DIP-BLACK-MALE-HEADER-VERT(2P-2.54)"))
    )
    (comp (ref "OJ26")
      (value "2p-2.54")
      (footprint "eagle-import:H2-2.54")
      (fields (field (name "MPN") "P125-1102A0BS116A1"))
      (libsource (lib "eagle-import") (part "DIP-BLACK-MALE-HEADER-VERT(2P-2.54)"))
    )
    (comp (ref "OJ27")
      (value "2p-2.54")
      (footprint "eagle-import:H2-2.54")
      (fields (field (name "MPN") "P125-1102A0BS116A1"))
      (libsource (lib "eagle-import") (part "DIP-BLACK-MALE-HEADER-VERT(2P-2.54)"))
    )
    (comp (ref "OJ28")
      (value "2p-2.54")
      (footprint "eagle-import:H2-2.54")
      (fields (field (name "MPN") "P125-1102A0BS116A1"))
      (libsource (lib "eagle-import") (part "DIP-BLACK-MALE-HEADER-VERT(2P-2.54)"))
    )
    (comp (ref "OJ29")
      (value "2p-2.54")
      (footprint "eagle-import:H2-2.54")
      (fields (field (name "MPN") "P125-1102A0BS116A1"))
      (libsource (lib "eagle-import") (part "DIP-BLACK-MALE-HEADER-VERT(2P-2.54)"))
    )
    (comp (ref "OJ30")
      (value "2p-2.54")
      (footprint "eagle-import:H2-2.54")
      (fields (field (name "MPN") "P125-1102A0BS116A1"))
      (libsource (lib "eagle-import") (part "DIP-BLACK-MALE-HEADER-VERT(2P-2.54)"))
    )
    (comp (ref "OJ31")
      (value "2p-2.54")
      (footprint "eagle-import:H2-2.54")
      (fields (field (name "MPN") "P125-1102A0BS116A1"))
      (libsource (lib "eagle-import") (part "DIP-BLACK-MALE-HEADER-VERT(2P-2.54)"))
    )
    (comp (ref "OJ32")
      (value "2p-2.54")
      (footprint "eagle-import:H2-2.54")
      (fields (field (name "MPN") "P125-1102A0BS116A1"))
      (libsource (lib "eagle-import") (part "DIP-BLACK-MALE-HEADER-VERT(2P-2.54)"))
    )
    (comp (ref "OJ33")
      (value "2p-2.54")
      (footprint "eagle-import:H2-2.54")
      (fields (field (name "MPN") "P125-1102A0BS116A1"))
      (libsource (lib "eagle-import") (part "DIP-BLACK-MALE-HEADER-VERT(2P-2.54)"))
    )
    (comp (ref "OJ34")
      (value "2p-2.54")
      (footprint "eagle-import:H2-2.54")
      (fields (field (name "MPN") "P125-1102A0BS116A1"))
      (libsource (lib "eagle-import") (part "DIP-BLACK-MALE-HEADER-VERT(2P-2.54)"))
    )
    (comp (ref "OJ35")
      (value "2p-2.54")
      (footprint "eagle-import:H2-2.54")
      (fields (field (name "MPN") "P125-1102A0BS116A1"))
      (libsource (lib "eagle-import") (part "DIP-BLACK-MALE-HEADER-VERT(2P-2.54)"))
    )
    (comp (ref "OJ36")
      (value "2p-2.54")
      (footprint "eagle-import:H2-2.54")
      (fields (field (name "MPN") "P125-1102A0BS116A1"))
      (libsource (lib "eagle-import") (part "DIP-BLACK-MALE-HEADER-VERT(2P-2.54)"))
    )
    (comp (ref "OJ37")
      (value "2p-2.54")
      (footprint "eagle-import:H2-2.54")
      (fields (field (name "MPN") "P125-1102A0BS116A1"))
      (libsource (lib "eagle-import") (part "DIP-BLACK-MALE-HEADER-VERT(2P-2.54)"))
    )
    (comp (ref "OJ38")
      (value "2p-2.54")
      (footprint "eagle-import:H2-2.54")
      (fields (field (name "MPN") "P125-1102A0BS116A1"))
      (libsource (lib "eagle-import") (part "DIP-BLACK-MALE-HEADER-VERT(2P-2.54)"))
    )
    (comp (ref "OJ39")
      (value "2p-2.54")
      (footprint "eagle-import:H2-2.54")
      (fields (field (name "MPN") "P125-1102A0BS116A1"))
      (libsource (lib "eagle-import") (part "DIP-BLACK-MALE-HEADER-VERT(2P-2.54)"))
    )
    (comp (ref "OJ40")
      (value "2p-2.54")
      (footprint "eagle-import:H2-2.54")
      (fields (field (name "MPN") "P125-1102A0BS116A1"))
      (libsource (lib "eagle-import") (part "DIP-BLACK-MALE-HEADER-VERT(2P-2.54)"))
    )
    (comp (ref "OJ41")
      (value "2p-2.54")
      (footprint "eagle-import:H2-2.54")
      (fields (field (name "MPN") "P125-1102A0BS116A1"))
      (libsource (lib "eagle-import") (part "DIP-BLACK-MALE-HEADER-VERT(2P-2.54)"))
    )
    (comp (ref "OJ42")
      (value "2p-2.54")
      (footprint "eagle-import:H2-2.54")
      (fields (field (name "MPN") "P125-1102A0BS116A1"))
      (libsource (lib "eagle-import") (part "DIP-BLACK-MALE-HEADER-VERT(2P-2.54)"))
    )
    (comp (ref "OJ43")
      (value "2p-2.54")
      (footprint "eagle-import:H2-2.54")
      (fields (field (name "MPN") "P125-1102A0BS116A1"))
      (libsource (lib "eagle-import") (part "DIP-BLACK-MALE-HEADER-VERT(2P-2.54)"))
    )
    (comp (ref "OJ44")
      (value "2p-2.54")
      (footprint "eagle-import:H2-2.54")
      (fields (field (name "MPN") "P125-1102A0BS116A1"))
      (libsource (lib "eagle-import") (part "DIP-BLACK-MALE-HEADER-VERT(2P-2.54)"))
    )
    (comp (ref "OJ45")
      (value "2p-2.54")
      (footprint "eagle-import:H2-2.54")
      (fields (field (name "MPN") "P125-1102A0BS116A1"))
      (libsource (lib "eagle-import") (part "DIP-BLACK-MALE-HEADER-VERT(2P-2.54)"))
    )
    (comp (ref "OJ46")
      (value "2p-2.54")
      (footprint "eagle-import:H2-2.54")
      (fields (field (name "MPN") "P125-1102A0BS116A1"))
      (libsource (lib "eagle-import") (part "DIP-BLACK-MALE-HEADER-VERT(2P-2.54)"))
    )
    (comp (ref "OJ47")
      (value "2p-2.54")
      (footprint "eagle-import:H2-2.54")
      (fields (field (name "MPN") "P125-1102A0BS116A1"))
      (libsource (lib "eagle-import") (part "DIP-BLACK-MALE-HEADER-VERT(2P-2.54)"))
    )
    (comp (ref "OJ48")
      (value "2p-2.54")
      (footprint "eagle-import:H2-2.54")
      (fields (field (name "MPN") "P125-1102A0BS116A1"))
      (libsource (lib "eagle-import") (part "DIP-BLACK-MALE-HEADER-VERT(2P-2.54)"))
    )
    (comp (ref "OJ49")
      (value "2p-2.54")
      (footprint "eagle-import:H2-2.54")
      (fields (field (name "MPN") "P125-1102A0BS116A1"))
      (libsource (lib "eagle-import") (part "DIP-BLACK-MALE-HEADER-VERT(2P-2.54)"))
    )
    (comp (ref "OJ50")
      (value "2p-2.54")
      (footprint "eagle-import:H2-2.54")
      (fields (field (name "MPN") "P125-1102A0BS116A1"))
      (libsource (lib "eagle-import") (part "DIP-BLACK-MALE-HEADER-VERT(2P-2.54)"))
    )
    (comp (ref "OJ51")
      (value "2p-2.54")
      (footprint "eagle-import:H2-2.54")
      (fields (field (name "MPN") "P125-1102A0BS116A1"))
      (libsource (lib "eagle-import") (part "DIP-BLACK-MALE-HEADER-VERT(2P-2.54)"))
    )
    (comp (ref "OJ52")
      (value "2p-2.54")
      (footprint "eagle-import:H2-2.54")
      (fields (field (name "MPN") "P125-1102A0BS116A1"))
      (libsource (lib "eagle-import") (part "DIP-BLACK-MALE-HEADER-VERT(2P-2.54)"))
    )
    (comp (ref "OJ53")
      (value "2p-2.54")
      (footprint "eagle-import:H2-2.54")
      (fields (field (name "MPN") "P125-1102A0BS116A1"))
      (libsource (lib "eagle-import") (part "DIP-BLACK-MALE-HEADER-VERT(2P-2.54)"))
    )
    (comp (ref "OJ54")
      (value "2p-2.54")
      (footprint "eagle-import:H2-2.54")
      (fields (field (name "MPN") "P125-1102A0BS116A1"))
      (libsource (lib "eagle-import") (part "DIP-BLACK-MALE-HEADER-VERT(2P-2.54)"))
    )
    (comp (ref "OJ55")
      (value "2p-2.54")
      (footprint "eagle-import:H2-2.54")
      (fields (field (name "MPN") "P125-1102A0BS116A1"))
      (libsource (lib "eagle-import") (part "DIP-BLACK-MALE-HEADER-VERT(2P-2.54)"))
    )
    (comp (ref "OJ56")
      (value "2p-2.54")
      (footprint "eagle-import:H2-2.54")
      (fields (field (name "MPN") "P125-1102A0BS116A1"))
      (libsource (lib "eagle-import") (part "DIP-BLACK-MALE-HEADER-VERT(2P-2.54)"))
    )
    (comp (ref "OJ57")
      (value "2p-2.54")
      (footprint "eagle-import:H2-2.54")
      (fields (field (name "MPN") "P125-1102A0BS116A1"))
      (libsource (lib "eagle-import") (part "DIP-BLACK-MALE-HEADER-VERT(2P-2.54)"))
    )
    (comp (ref "OJ58")
      (value "2p-2.54")
      (footprint "eagle-import:H2-2.54")
      (fields (field (name "MPN") "P125-1102A0BS116A1"))
      (libsource (lib "eagle-import") (part "DIP-BLACK-MALE-HEADER-VERT(2P-2.54)"))
    )
    (comp (ref "OJ59")
      (value "2p-2.54")
      (footprint "eagle-import:H2-2.54")
      (fields (field (name "MPN") "P125-1102A0BS116A1"))
      (libsource (lib "eagle-import") (part "DIP-BLACK-MALE-HEADER-VERT(2P-2.54)"))
    )
    (comp (ref "OJ60")
      (value "2p-2.54")
      (footprint "eagle-import:H2-2.54")
      (fields (field (name "MPN") "P125-1102A0BS116A1"))
      (libsource (lib "eagle-import") (part "DIP-BLACK-MALE-HEADER-VERT(2P-2.54)"))
    )
    (comp (ref "OJ61")
      (value "2p-2.54")
      (footprint "eagle-import:H2-2.54")
      (fields (field (name "MPN") "P125-1102A0BS116A1"))
      (libsource (lib "eagle-import") (part "DIP-BLACK-MALE-HEADER-VERT(2P-2.54)"))
    )
    (comp (ref "OJ62")
      (value "2p-2.54")
      (footprint "eagle-import:H2-2.54")
      (fields (field (name "MPN") "P125-1102A0BS116A1"))
      (libsource (lib "eagle-import") (part "DIP-BLACK-MALE-HEADER-VERT(2P-2.54)"))
    )
    (comp (ref "OJ63")
      (value "2p-2.54")
      (footprint "eagle-import:H2-2.54")
      (fields (field (name "MPN") "P125-1102A0BS116A1"))
      (libsource (lib "eagle-import") (part "DIP-BLACK-MALE-HEADER-VERT(2P-2.54)"))
    )
    (comp (ref "OJ64")
      (value "2p-2.54")
      (footprint "eagle-import:H2-2.54")
      (fields (field (name "MPN") "P125-1102A0BS116A1"))
      (libsource (lib "eagle-import") (part "DIP-BLACK-MALE-HEADER-VERT(2P-2.54)"))
    )
    (comp (ref "OJ65")
      (value "2p-2.54")
      (footprint "eagle-import:H2-2.54")
      (fields (field (name "MPN") "P125-1102A0BS116A1"))
      (libsource (lib "eagle-import") (part "DIP-BLACK-MALE-HEADER-VERT(2P-2.54)"))
    )
    (comp (ref "OJ66")
      (value "2p-2.54")
      (footprint "eagle-import:H2-2.54")
      (fields (field (name "MPN") "P125-1102A0BS116A1"))
      (libsource (lib "eagle-import") (part "DIP-BLACK-MALE-HEADER-VERT(2P-2.54)"))
    )
    (comp (ref "OJ67")
      (value "2p-2.54")
      (footprint "eagle-import:H2-2.54")
      (fields (field (name "MPN") "P125-1102A0BS116A1"))
      (libsource (lib "eagle-import") (part "DIP-BLACK-MALE-HEADER-VERT(2P-2.54)"))
    )
    (comp (ref "OJ68")
      (value "2p-2.54")
      (footprint "eagle-import:H2-2.54")
      (fields (field (name "MPN") "P125-1102A0BS116A1"))
      (libsource (lib "eagle-import") (part "DIP-BLACK-MALE-HEADER-VERT(2P-2.54)"))
    )
    (comp (ref "OJ69")
      (value "2p-2.54")
      (footprint "eagle-import:H2-2.54")
      (fields (field (name "MPN") "P125-1102A0BS116A1"))
      (libsource (lib "eagle-import") (part "DIP-BLACK-MALE-HEADER-VERT(2P-2.54)"))
    )
    (comp (ref "OJ70")
      (value "2p-2.54")
      (footprint "eagle-import:H2-2.54")
      (fields (field (name "MPN") "P125-1102A0BS116A1"))
      (libsource (lib "eagle-import") (part "DIP-BLACK-MALE-HEADER-VERT(2P-2.54)"))
    )
    (comp (ref "OJ71")
      (value "2p-2.54")
      (footprint "eagle-import:H2-2.54")
      (fields (field (name "MPN") "P125-1102A0BS116A1"))
      (libsource (lib "eagle-import") (part "DIP-BLACK-MALE-HEADER-VERT(2P-2.54)"))
    )
    (comp (ref "OJ72")
      (value "2p-2.54")
      (footprint "eagle-import:H2-2.54")
      (fields (field (name "MPN") "P125-1102A0BS116A1"))
      (libsource (lib "eagle-import") (part "DIP-BLACK-MALE-HEADER-VERT(2P-2.54)"))
    )
    (comp (ref "OJ73")
      (value "2p-2.54")
      (footprint "eagle-import:H2-2.54")
      (fields (field (name "MPN") "P125-1102A0BS116A1"))
      (libsource (lib "eagle-import") (part "DIP-BLACK-MALE-HEADER-VERT(2P-2.54)"))
    )
    (comp (ref "OJ74")
      (value "2p-2.54")
      (footprint "eagle-import:H2-2.54")
      (fields (field (name "MPN") "P125-1102A0BS116A1"))
      (libsource (lib "eagle-import") (part "DIP-BLACK-MALE-HEADER-VERT(2P-2.54)"))
    )
    (comp (ref "OJ75")
      (value "2p-2.54")
      (footprint "eagle-import:H2-2.54")
      (fields (field (name "MPN") "P125-1102A0BS116A1"))
      (libsource (lib "eagle-import") (part "DIP-BLACK-MALE-HEADER-VERT(2P-2.54)"))
    )
    (comp (ref "OJ76")
      (value "2p-2.54")
      (footprint "eagle-import:H2-2.54")
      (fields (field (name "MPN") "P125-1102A0BS116A1"))
      (libsource (lib "eagle-import") (part "DIP-BLACK-MALE-HEADER-VERT(2P-2.54)"))
    )
    (comp (ref "OJ77")
      (value "2p-2.54")
      (footprint "eagle-import:H2-2.54")
      (fields (field (name "MPN") "P125-1102A0BS116A1"))
      (libsource (lib "eagle-import") (part "DIP-BLACK-MALE-HEADER-VERT(2P-2.54)"))
    )
    (comp (ref "OJ78")
      (value "2p-2.54")
      (footprint "eagle-import:H2-2.54")
      (fields (field (name "MPN") "P125-1102A0BS116A1"))
      (libsource (lib "eagle-import") (part "DIP-BLACK-MALE-HEADER-VERT(2P-2.54)"))
    )
    (comp (ref "OJ79")
      (value "2p-2.54")
      (footprint "eagle-import:H2-2.54")
      (fields (field (name "MPN") "P125-1102A0BS116A1"))
      (libsource (lib "eagle-import") (part "DIP-BLACK-MALE-HEADER-VERT(2P-2.54)"))
    )
    (comp (ref "OJ80")
      (value "2p-2.54")
      (footprint "eagle-import:H2-2.54")
      (fields (field (name "MPN") "P125-1102A0BS116A1"))
      (libsource (lib "eagle-import") (part "DIP-BLACK-MALE-HEADER-VERT(2P-2.54)"))
    )
    (comp (ref "OJ89")
      (value "2p-2.54")
      (footprint "eagle-import:H2-2.54")
      (fields (field (name "MPN") "P125-1102A0BS116A1"))
      (libsource (lib "eagle-import") (part "DIP-BLACK-MALE-HEADER-VERT(2P-2.54)"))
    )
    (comp (ref "OJ90")
      (value "2p-2.54")
      (footprint "eagle-import:H2-2.54")
      (fields (field (name "MPN") "P125-1102A0BS116A1"))
      (libsource (lib "eagle-import") (part "DIP-BLACK-MALE-HEADER-VERT(2P-2.54)"))
    )
    (comp (ref "OJ91")
      (value "2p-2.54")
      (footprint "eagle-import:H2-2.54")
      (fields (field (name "MPN") "P125-1102A0BS116A1"))
      (libsource (lib "eagle-import") (part "DIP-BLACK-MALE-HEADER-VERT(2P-2.54)"))
    )
    (comp (ref "OJ92")
      (value "2p-2.54")
      (footprint "eagle-import:H2-2.54")
      (fields (field (name "MPN") "P125-1102A0BS116A1"))
      (libsource (lib "eagle-import") (part "DIP-BLACK-MALE-HEADER-VERT(2P-2.54)"))
    )
    (comp (ref "OJ93")
      (value "2p-2.54")
      (footprint "eagle-import:H2-2.54")
      (fields (field (name "MPN") "P125-1102A0BS116A1"))
      (libsource (lib "eagle-import") (part "DIP-BLACK-MALE-HEADER-VERT(2P-2.54)"))
    )
    (comp (ref "OJ94")
      (value "2p-2.54")
      (footprint "eagle-import:H2-2.54")
      (fields (field (name "MPN") "P125-1102A0BS116A1"))
      (libsource (lib "eagle-import") (part "DIP-BLACK-MALE-HEADER-VERT(2P-2.54)"))
    )
    (comp (ref "OJ95")
      (value "2p-2.54")
      (footprint "eagle-import:H2-2.54")
      (fields (field (name "MPN") "P125-1102A0BS116A1"))
      (libsource (lib "eagle-import") (part "DIP-BLACK-MALE-HEADER-VERT(2P-2.54)"))
    )
    (comp (ref "OJ96")
      (value "2p-2.54")
      (footprint "eagle-import:H2-2.54")
      (fields (field (name "MPN") "P125-1102A0BS116A1"))
      (libsource (lib "eagle-import") (part "DIP-BLACK-MALE-HEADER-VERT(2P-2.54)"))
    )
    (comp (ref "P9")
      (value "BU-SMB-V")
      (footprint "eagle-import:BU-SMB-V")
      (libsource (lib "eagle-import") (part "BU-SMB-V"))
    )
    (comp (ref "P11")
      (value "BU-SMB-V")
      (footprint "eagle-import:BU-SMB-V")
      (libsource (lib "eagle-import") (part "BU-SMB-V"))
    )
    (comp (ref "P14_CLKOUT_4P")
      (value "BU-SMB-V")
      (footprint "eagle-import:BU-SMB-V")
      (libsource (lib "eagle-import") (part "BU-SMB-V"))
    )
    (comp (ref "P15")
      (value "BU-SMB-V")
      (footprint "eagle-import:BU-SMB-V")
      (libsource (lib "eagle-import") (part "BU-SMB-V"))
    )
    (comp (ref "P16_R15N")
      (value "BU-SMB-V")
      (footprint "eagle-import:BU-SMB-V")
      (libsource (lib "eagle-import") (part "BU-SMB-V"))
    )
    (comp (ref "PIN_AIN_PWRGND21")
      (value "15-91-2160")
      (footprint "eagle-import:2X08_90")
      (libsource (lib "eagle-import") (part "PINHD-2X8/90"))
    )
    (comp (ref "PIN_ANALOG_21")
      (value "15-91-2160")
      (footprint "eagle-import:2X08_90")
      (libsource (lib "eagle-import") (part "PINHD-2X8/90"))
    )
    (comp (ref "R4")
      (value "50")
      (footprint "eagle-import:AXIAL-0.3")
      (libsource (lib "eagle-import") (part "RESISTORAXIAL-0.3"))
    )
    (comp (ref "R5")
      (value "50")
      (footprint "eagle-import:AXIAL-0.3")
      (libsource (lib "eagle-import") (part "RESISTORAXIAL-0.3"))
    )
    (comp (ref "R6")
      (value "50")
      (footprint "eagle-import:AXIAL-0.3")
      (libsource (lib "eagle-import") (part "RESISTORAXIAL-0.3"))
    )
    (comp (ref "R8")
      (value "560")
      (footprint "eagle-import:R0805")
      (libsource (lib "eagle-import") (part "R-US_R0805"))
    )
    (comp (ref "R9")
      (value "50")
      (footprint "eagle-import:AXIAL-0.3")
      (libsource (lib "eagle-import") (part "RESISTORAXIAL-0.3"))
    )
    (comp (ref "R9CLK_7P_CLKIN")
      (value "BU-SMB-V")
      (footprint "eagle-import:BU-SMB-V")
      (libsource (lib "eagle-import") (part "BU-SMB-V"))
    )
    (comp (ref "R10_B16P")
      (value "BU-SMB-V")
      (footprint "eagle-import:BU-SMB-V")
      (libsource (lib "eagle-import") (part "BU-SMB-V"))
    )
    (comp (ref "R11")
      (value "50")
      (footprint "eagle-import:AXIAL-0.3")
      (libsource (lib "eagle-import") (part "RESISTORAXIAL-0.3"))
    )
    (comp (ref "R12_B18P")
      (value "BU-SMB-V")
      (footprint "eagle-import:BU-SMB-V")
      (libsource (lib "eagle-import") (part "BU-SMB-V"))
    )
    (comp (ref "R13_B20P")
      (value "BU-SMB-V")
      (footprint "eagle-import:BU-SMB-V")
      (libsource (lib "eagle-import") (part "BU-SMB-V"))
    )
    (comp (ref "R14_CLKOUT_4N")
      (value "BU-SMB-V")
      (footprint "eagle-import:BU-SMB-V")
      (libsource (lib "eagle-import") (part "BU-SMB-V"))
    )
    (comp (ref "R15")
      (value "50")
      (footprint "eagle-import:AXIAL-0.3")
      (libsource (lib "eagle-import") (part "RESISTORAXIAL-0.3"))
    )
    (comp (ref "R16_R15P")
      (value "BU-SMB-V")
      (footprint "eagle-import:BU-SMB-V")
      (libsource (lib "eagle-import") (part "BU-SMB-V"))
    )
    (comp (ref "R17")
      (value "10k")
      (footprint "eagle-import:R0805")
      (libsource (lib "eagle-import") (part "R-US_R0805"))
    )
    (comp (ref "R18")
      (value "50")
      (footprint "eagle-import:AXIAL-0.3")
      (libsource (lib "eagle-import") (part "RESISTORAXIAL-0.3"))
    )
    (comp (ref "R19")
      (value "50")
      (footprint "eagle-import:AXIAL-0.3")
      (libsource (lib "eagle-import") (part "RESISTORAXIAL-0.3"))
    )
    (comp (ref "R20")
      (value "50")
      (footprint "eagle-import:AXIAL-0.3")
      (libsource (lib "eagle-import") (part "RESISTORAXIAL-0.3"))
    )
    (comp (ref "R21")
      (value "50")
      (footprint "eagle-import:AXIAL-0.3")
      (libsource (lib "eagle-import") (part "RESISTORAXIAL-0.3"))
    )
    (comp (ref "R22")
      (value "50")
      (footprint "eagle-import:AXIAL-0.3")
      (libsource (lib "eagle-import") (part "RESISTORAXIAL-0.3"))
    )
    (comp (ref "R23")
      (value "50")
      (footprint "eagle-import:AXIAL-0.3")
      (libsource (lib "eagle-import") (part "RESISTORAXIAL-0.3"))
    )
    (comp (ref "R24")
      (value "50")
      (footprint "eagle-import:AXIAL-0.3")
      (libsource (lib "eagle-import") (part "RESISTORAXIAL-0.3"))
    )
    (comp (ref "R25")
      (value "50")
      (footprint "eagle-import:AXIAL-0.3")
      (libsource (lib "eagle-import") (part "RESISTORAXIAL-0.3"))
    )
    (comp (ref "R26")
      (value "50")
      (footprint "eagle-import:AXIAL-0.3")
      (libsource (lib "eagle-import") (part "RESISTORAXIAL-0.3"))
    )
    (comp (ref "R27")
      (value "50")
      (footprint "eagle-import:AXIAL-0.3")
      (libsource (lib "eagle-import") (part "RESISTORAXIAL-0.3"))
    )
    (comp (ref "R28")
      (value "50")
      (footprint "eagle-import:AXIAL-0.3")
      (libsource (lib "eagle-import") (part "RESISTORAXIAL-0.3"))
    )
    (comp (ref "R29")
      (value "50")
      (footprint "eagle-import:AXIAL-0.3")
      (libsource (lib "eagle-import") (part "RESISTORAXIAL-0.3"))
    )
    (comp (ref "R30")
      (value "50")
      (footprint "eagle-import:AXIAL-0.3")
      (libsource (lib "eagle-import") (part "RESISTORAXIAL-0.3"))
    )
    (comp (ref "R31")
      (value "50")
      (footprint "eagle-import:AXIAL-0.3")
      (libsource (lib "eagle-import") (part "RESISTORAXIAL-0.3"))
    )
    (comp (ref "R32")
      (value "50")
      (footprint "eagle-import:AXIAL-0.3")
      (libsource (lib "eagle-import") (part "RESISTORAXIAL-0.3"))
    )
    (comp (ref "R33")
      (value "50")
      (footprint "eagle-import:AXIAL-0.3")
      (libsource (lib "eagle-import") (part "RESISTORAXIAL-0.3"))
    )
    (comp (ref "R35")
      (value "50")
      (footprint "eagle-import:AXIAL-0.3")
      (libsource (lib "eagle-import") (part "RESISTORAXIAL-0.3"))
    )
    (comp (ref "R39")
      (value "50")
      (footprint "eagle-import:AXIAL-0.3")
      (libsource (lib "eagle-import") (part "RESISTORAXIAL-0.3"))
    )
    (comp (ref "R40")
      (value "50")
      (footprint "eagle-import:AXIAL-0.3")
      (libsource (lib "eagle-import") (part "RESISTORAXIAL-0.3"))
    )
    (comp (ref "R41")
      (value "50")
      (footprint "eagle-import:AXIAL-0.3")
      (libsource (lib "eagle-import") (part "RESISTORAXIAL-0.3"))
    )
    (comp (ref "R43")
      (value "50")
      (footprint "eagle-import:AXIAL-0.3")
      (libsource (lib "eagle-import") (part "RESISTORAXIAL-0.3"))
    )
    (comp (ref "R45")
      (value "50")
      (footprint "eagle-import:AXIAL-0.3")
      (libsource (lib "eagle-import") (part "RESISTORAXIAL-0.3"))
    )
    (comp (ref "R46")
      (value "50")
      (footprint "eagle-import:AXIAL-0.3")
      (libsource (lib "eagle-import") (part "RESISTORAXIAL-0.3"))
    )
    (comp (ref "R47")
      (value "50")
      (footprint "eagle-import:AXIAL-0.3")
      (libsource (lib "eagle-import") (part "RESISTORAXIAL-0.3"))
    )
    (comp (ref "R49")
      (value "50")
      (footprint "eagle-import:AXIAL-0.3")
      (libsource (lib "eagle-import") (part "RESISTORAXIAL-0.3"))
    )
    (comp (ref "R50")
      (value "50")
      (footprint "eagle-import:AXIAL-0.3")
      (libsource (lib "eagle-import") (part "RESISTORAXIAL-0.3"))
    )
    (comp (ref "R51")
      (value "50")
      (footprint "eagle-import:AXIAL-0.3")
      (libsource (lib "eagle-import") (part "RESISTORAXIAL-0.3"))
    )
    (comp (ref "R52")
      (value "50")
      (footprint "eagle-import:AXIAL-0.3")
      (libsource (lib "eagle-import") (part "RESISTORAXIAL-0.3"))
    )
    (comp (ref "R53")
      (value "50")
      (footprint "eagle-import:AXIAL-0.3")
      (libsource (lib "eagle-import") (part "RESISTORAXIAL-0.3"))
    )
    (comp (ref "R91")
      (value "50")
      (footprint "eagle-import:AXIAL-0.3")
      (libsource (lib "eagle-import") (part "RESISTORAXIAL-0.3"))
    )
    (comp (ref "R100")
      (value "50")
      (footprint "eagle-import:AXIAL-0.3")
      (libsource (lib "eagle-import") (part "RESISTORAXIAL-0.3"))
    )
    (comp (ref "R111")
      (value "50")
      (footprint "eagle-import:AXIAL-0.3")
      (libsource (lib "eagle-import") (part "RESISTORAXIAL-0.3"))
    )
    (comp (ref "R141")
      (value "50")
      (footprint "eagle-import:AXIAL-0.3")
      (libsource (lib "eagle-import") (part "RESISTORAXIAL-0.3"))
    )
    (comp (ref "R161")
      (value "50")
      (footprint "eagle-import:AXIAL-0.3")
      (libsource (lib "eagle-import") (part "RESISTORAXIAL-0.3"))
    )
    (comp (ref "SV1")
      (value "FE20-2")
      (footprint "eagle-import:FE20-2")
      (libsource (lib "eagle-import") (part "FE20-2"))
    )
    (comp (ref "SV2")
      (value "FE20-2")
      (footprint "eagle-import:FE20-2")
      (libsource (lib "eagle-import") (part "FE20-2"))
    )
    (comp (ref "T9CLK_7N")
      (value "BU-SMB-V")
      (footprint "eagle-import:BU-SMB-V")
      (libsource (lib "eagle-import") (part "BU-SMB-V"))
    )
    (comp (ref "T10_B16N")
      (value "BU-SMB-V")
      (footprint "eagle-import:BU-SMB-V")
      (libsource (lib "eagle-import") (part "BU-SMB-V"))
    )
    (comp (ref "T12_B18N")
      (value "BU-SMB-V")
      (footprint "eagle-import:BU-SMB-V")
      (libsource (lib "eagle-import") (part "BU-SMB-V"))
    )
    (comp (ref "T13_B20N")
      (value "BU-SMB-V")
      (footprint "eagle-import:BU-SMB-V")
      (libsource (lib "eagle-import") (part "BU-SMB-V"))
    )
    (comp (ref "T14_B23P_SPARE")
      (value "BU-SMB-V")
      (footprint "eagle-import:BU-SMB-V")
      (libsource (lib "eagle-import") (part "BU-SMB-V"))
    )
    (comp (ref "T15_B23N_TRIGOUT")
      (value "BU-SMB-V")
      (footprint "eagle-import:BU-SMB-V")
      (libsource (lib "eagle-import") (part "BU-SMB-V"))
    )
    (comp (ref "VSLUE")
      (value "SN74ACT244DW")
      (footprint "eagle-import:SOIC127P1030X265-20N")
      (fields (field (name "RS_PART_NUMBER") "4363169"))
      (libsource (lib "eagle-import") (part "SN74ACT244DW"))
    )
    (comp (ref "VSLUE2")
      (value "SN74ACT244DW")
      (footprint "eagle-import:SOIC127P1030X265-20N")
      (fields (field (name "RS_PART_NUMBER") "4363169"))
      (libsource (lib "eagle-import") (part "SN74ACT244DW"))
    )
    (comp (ref "VSLUE3")
      (value "SN74ACT244DW")
      (footprint "eagle-import:SOIC127P1030X265-20N")
      (fields (field (name "RS_PART_NUMBER") "4363169"))
      (libsource (lib "eagle-import") (part "SN74ACT244DW"))
    )
    (comp (ref "VSLUE4")
      (value "SN74ACT244DW")
      (footprint "eagle-import:SOIC127P1030X265-20N")
      (fields (field (name "RS_PART_NUMBER") "4363169"))
      (libsource (lib "eagle-import") (part "SN74ACT244DW"))
    )
    (comp (ref "VSLUE5")
      (value "SN74ACT244DW")
      (footprint "eagle-import:SOIC127P1030X265-20N")
      (fields (field (name "RS_PART_NUMBER") "4363169"))
      (libsource (lib "eagle-import") (part "SN74ACT244DW"))
    )
    (comp (ref "VSLUE6")
      (value "SN74ACT244DW")
      (footprint "eagle-import:SOIC127P1030X265-20N")
      (fields (field (name "RS_PART_NUMBER") "4363169"))
      (libsource (lib "eagle-import") (part "SN74ACT244DW"))
    )
    (comp (ref "VSLUE7")
      (value "SN74ACT244DW")
      (footprint "eagle-import:SOIC127P1030X265-20N")
      (fields (field (name "RS_PART_NUMBER") "4363169"))
      (libsource (lib "eagle-import") (part "SN74ACT244DW"))
    )
    (comp (ref "VSLUE8")
      (value "SN74ACT244DW")
      (footprint "eagle-import:SOIC127P1030X265-20N")
      (fields (field (name "RS_PART_NUMBER") "4363169"))
      (libsource (lib "eagle-import") (part "SN74ACT244DW"))
    )
    (comp (ref "VSLUE9")
      (value "SN74ACT244DW")
      (footprint "eagle-import:SOIC127P1030X265-20N")
      (fields (field (name "RS_PART_NUMBER") "4363169"))
      (libsource (lib "eagle-import") (part "SN74ACT244DW"))
    )
    (comp (ref "VSLUE11")
      (value "SN74ACT244DW")
      (footprint "eagle-import:SOIC127P1030X265-20N")
      (fields (field (name "RS_PART_NUMBER") "4363169"))
      (libsource (lib "eagle-import") (part "SN74ACT244DW"))
    )
  )
  (nets
    (net (code "1") (name "/3V3") (class "Default")
      (node (ref "J1") (pin "1") (pinfunction "1_1") (pintype "passive"))
      (node (ref "J12") (pin "4") (pinfunction "P$4_4") (pintype "bidirectional"))
      (node (ref "SV1") (pin "29") (pinfunction "29_29") (pintype "passive"))
      (node (ref "SV2") (pin "29") (pinfunction "29_29") (pintype "passive"))
    )
    (net (code "2") (name "/5V") (class "Default")
      (node (ref "C10") (pin "2") (pinfunction "2_2") (pintype "passive"))
      (node (ref "C2") (pin "2") (pinfunction "2_2") (pintype "passive"))
      (node (ref "C4") (pin "2") (pinfunction "2_2") (pintype "passive"))
      (node (ref "C5") (pin "2") (pinfunction "2_2") (pintype "passive"))
      (node (ref "C91") (pin "2") (pinfunction "2_2") (pintype "passive"))
      (node (ref "C93") (pin "2") (pinfunction "2_2") (pintype "passive"))
      (node (ref "C94") (pin "2") (pinfunction "2_2") (pintype "passive"))
      (node (ref "C95") (pin "2") (pinfunction "2_2") (pintype "passive"))
      (node (ref "C96") (pin "2") (pinfunction "2_2") (pintype "passive"))
      (node (ref "C97") (pin "2") (pinfunction "2_2") (pintype "passive"))
      (node (ref "J7") (pin "4") (pinfunction "P$4_4") (pintype "bidirectional"))
      (node (ref "PIN_ANALOG_21") (pin "5") (pinfunction "5_5") (pintype "passive"))
      (node (ref "R17") (pin "2") (pinfunction "2_2") (pintype "passive"))
      (node (ref "SV1") (pin "11") (pinfunction "11_11") (pintype "passive"))
      (node (ref "SV2") (pin "11") (pinfunction "11_11") (pintype "passive"))
      (node (ref "VSLUE") (pin "20") (pinfunction "VCC_20") (pintype "power_in"))
      (node (ref "VSLUE11") (pin "20") (pinfunction "VCC_20") (pintype "power_in"))
      (node (ref "VSLUE2") (pin "20") (pinfunction "VCC_20") (pintype "power_in"))
      (node (ref "VSLUE3") (pin "20") (pinfunction "VCC_20") (pintype "power_in"))
      (node (ref "VSLUE4") (pin "20") (pinfunction "VCC_20") (pintype "power_in"))
      (node (ref "VSLUE5") (pin "20") (pinfunction "VCC_20") (pintype "power_in"))
      (node (ref "VSLUE6") (pin "20") (pinfunction "VCC_20") (pintype "power_in"))
      (node (ref "VSLUE7") (pin "20") (pinfunction "VCC_20") (pintype "power_in"))
      (node (ref "VSLUE8") (pin "20") (pinfunction "VCC_20") (pintype "power_in"))
      (node (ref "VSLUE9") (pin "20") (pinfunction "VCC_20") (pintype "power_in"))
    )
    (net (code "3") (name "/AIN0") (class "Default")
      (node (ref "J1") (pin "24") (pinfunction "24_24") (pintype "passive"))
      (node (ref "J131") (pin "4") (pinfunction "P$4_4") (pintype "bidirectional"))
    )
    (net (code "4") (name "/AIN1") (class "Default")
      (node (ref "J1") (pin "25") (pinfunction "25_25") (pintype "passive"))
      (node (ref "J311") (pin "1") (pinfunction "P$1_1") (pintype "bidirectional"))
    )
    (net (code "5") (name "/AIN2") (class "Default")
      (node (ref "J1") (pin "22") (pinfunction "22_22") (pintype "passive"))
      (node (ref "J131") (pin "3") (pinfunction "P$3_3") (pintype "bidirectional"))
    )
    (net (code "6") (name "/AIN3") (class "Default")
      (node (ref "J1") (pin "21") (pinfunction "21_21") (pintype "passive"))
      (node (ref "J311") (pin "3") (pinfunction "P$3_3") (pintype "bidirectional"))
    )
    (net (code "7") (name "/AIN4") (class "Default")
      (node (ref "J1") (pin "23") (pinfunction "23_23") (pintype "passive"))
      (node (ref "J311") (pin "2") (pinfunction "P$2_2") (pintype "bidirectional"))
    )
    (net (code "8") (name "/AIN5") (class "Default")
      (node (ref "J1") (pin "18") (pinfunction "18_18") (pintype "passive"))
      (node (ref "J131") (pin "1") (pinfunction "P$1_1") (pintype "bidirectional"))
    )
    (net (code "9") (name "/AIN6") (class "Default")
      (node (ref "J1") (pin "19") (pinfunction "19_19") (pintype "passive"))
      (node (ref "J311") (pin "4") (pinfunction "P$4_4") (pintype "bidirectional"))
    )
    (net (code "10") (name "/AIN7") (class "Default")
      (node (ref "J1") (pin "20") (pinfunction "20_20") (pintype "passive"))
      (node (ref "J131") (pin "2") (pinfunction "P$2_2") (pintype "bidirectional"))
    )
    (net (code "11") (name "/GPIO_00_D3") (class "Default")
      (node (ref "D3_CLKOUT_3P") (pin "1") (pinfunction "1_1") (pintype "passive"))
      (node (ref "J50") (pin "2") (pinfunction "2_2") (pintype "bidirectional"))
      (node (ref "R51") (pin "P$2") (pinfunction "2_P$2") (pintype "passive"))
      (node (ref "SV1") (pin "2") (pinfunction "2_2") (pintype "passive"))
    )
    (net (code "12") (name "/GPIO_0_IN0_A8CLK") (class "Default")
      (node (ref "A8CLK_4N") (pin "1") (pinfunction "1_1") (pintype "passive"))
      (node (ref "J24") (pin "2") (pinfunction "2_2") (pintype "bidirectional"))
      (node (ref "PIN_AIN_PWRGND21") (pin "10") (pinfunction "10_10") (pintype "passive"))
      (node (ref "R23") (pin "P$2") (pinfunction "2_P$2") (pintype "passive"))
      (node (ref "SV1") (pin "1") (pinfunction "1_1") (pintype "passive"))
    )
    (net (code "13") (name "/GPIO_0_IN1_B8CLK") (class "Default")
      (node (ref "B8CLK_4P") (pin "1") (pinfunction "1_1") (pintype "passive"))
      (node (ref "J23") (pin "2") (pinfunction "2_2") (pintype "bidirectional"))
      (node (ref "PIN_AIN_PWRGND21") (pin "12") (pinfunction "12_12") (pintype "passive"))
      (node (ref "R22") (pin "P$2") (pinfunction "2_P$2") (pintype "passive"))
      (node (ref "SV1") (pin "3") (pinfunction "3_3") (pintype "passive"))
    )
    (net (code "14") (name "/GPIO_01_C3") (class "Default")
      (node (ref "C3_CLKOUT_3N") (pin "1") (pinfunction "1_1") (pintype "passive"))
      (node (ref "J30") (pin "2") (pinfunction "2_2") (pintype "bidirectional"))
      (node (ref "R27") (pin "P$2") (pinfunction "2_P$2") (pintype "passive"))
      (node (ref "SV1") (pin "4") (pinfunction "4_4") (pintype "passive"))
    )
    (net (code "15") (name "/GPIO_1_IN0_T9CLK") (class "Default")
      (node (ref "J6") (pin "2") (pinfunction "2_2") (pintype "bidirectional"))
      (node (ref "R6") (pin "P$2") (pinfunction "2_P$2") (pintype "passive"))
      (node (ref "SV2") (pin "1") (pinfunction "1_1") (pintype "passive"))
      (node (ref "T9CLK_7N") (pin "1") (pinfunction "1_1") (pintype "passive"))
    )
    (net (code "16") (name "/GPIO_1_IN1_R9CLK_CLKIN") (class "Default")
      (node (ref "J5") (pin "2") (pinfunction "2_2") (pintype "bidirectional"))
      (node (ref "PIN_ANALOG_21") (pin "1") (pinfunction "1_1") (pintype "passive"))
      (node (ref "R5") (pin "P$2") (pinfunction "2_P$2") (pintype "passive"))
      (node (ref "R9CLK_7P_CLKIN") (pin "1") (pinfunction "1_1") (pintype "passive"))
      (node (ref "SV2") (pin "3") (pinfunction "3_3") (pintype "passive"))
    )
    (net (code "17") (name "/GPIO_02_A2") (class "Default")
      (node (ref "A2_T2N") (pin "1") (pinfunction "1_1") (pintype "passive"))
      (node (ref "J22") (pin "2") (pinfunction "2_2") (pintype "bidirectional"))
      (node (ref "PIN_AIN_PWRGND21") (pin "14") (pinfunction "14_14") (pintype "passive"))
      (node (ref "R20") (pin "P$2") (pinfunction "2_P$2") (pintype "passive"))
      (node (ref "SV1") (pin "5") (pinfunction "5_5") (pintype "passive"))
    )
    (net (code "18") (name "/GPIO_2_IN0_E15CLK") (class "Default")
      (node (ref "E15CLK_2P") (pin "1") (pinfunction "1_1") (pintype "passive"))
      (node (ref "J1") (pin "2") (pinfunction "2_2") (pintype "passive"))
      (node (ref "J16") (pin "2") (pinfunction "2_2") (pintype "bidirectional"))
      (node (ref "PIN_AIN_PWRGND21") (pin "4") (pinfunction "4_4") (pintype "passive"))
      (node (ref "R19") (pin "P$2") (pinfunction "2_P$2") (pintype "passive"))
    )
    (net (code "19") (name "/GPIO_2_IN1_E16CLK") (class "Default")
      (node (ref "E16CLK_2N") (pin "1") (pinfunction "1_1") (pintype "passive"))
      (node (ref "J1") (pin "3") (pinfunction "3_3") (pintype "passive"))
      (node (ref "J15") (pin "2") (pinfunction "2_2") (pintype "bidirectional"))
      (node (ref "PIN_AIN_PWRGND21") (pin "2") (pinfunction "2_2") (pintype "passive"))
      (node (ref "R18") (pin "P$2") (pinfunction "2_P$2") (pintype "passive"))
    )
    (net (code "20") (name "/GPIO_2_IN2_M16CLK") (class "Default")
      (node (ref "J1") (pin "4") (pinfunction "4_4") (pintype "passive"))
      (node (ref "J141") (pin "2") (pinfunction "2_2") (pintype "bidirectional"))
      (node (ref "M16CLK_3N") (pin "1") (pinfunction "1_1") (pintype "passive"))
      (node (ref "R15") (pin "P$2") (pinfunction "2_P$2") (pintype "passive"))
    )
    (net (code "21") (name "/GPIO_03_A3") (class "Default")
      (node (ref "A3_T2P") (pin "1") (pinfunction "1_1") (pintype "passive"))
      (node (ref "J25") (pin "2") (pinfunction "2_2") (pintype "bidirectional"))
      (node (ref "PIN_AIN_PWRGND21") (pin "13") (pinfunction "13_13") (pintype "passive"))
      (node (ref "R25") (pin "P$2") (pinfunction "2_P$2") (pintype "passive"))
      (node (ref "SV1") (pin "6") (pinfunction "6_6") (pintype "passive"))
    )
    (net (code "22") (name "/GPIO_04_B3") (class "Default")
      (node (ref "OJ96") (pin "1") (pinfunction "1_1") (pintype "bidirectional"))
      (node (ref "SV1") (pin "7") (pinfunction "7_7") (pintype "passive"))
      (node (ref "VSLUE11") (pin "6") (pinfunction "1A3_6") (pintype "input"))
      (node (ref "VSLUE11") (pin "8") (pinfunction "1A4_8") (pintype "input"))
    )
    (net (code "23") (name "/GPIO_05_B4") (class "Default")
      (node (ref "OJ94") (pin "1") (pinfunction "1_1") (pintype "bidirectional"))
      (node (ref "SV1") (pin "8") (pinfunction "8_8") (pintype "passive"))
      (node (ref "VSLUE11") (pin "11") (pinfunction "2A1_11") (pintype "input"))
      (node (ref "VSLUE11") (pin "13") (pinfunction "2A2_13") (pintype "input"))
    )
    (net (code "24") (name "/GPIO_06_A4") (class "Default")
      (node (ref "OJ93") (pin "1") (pinfunction "1_1") (pintype "bidirectional"))
      (node (ref "SV1") (pin "9") (pinfunction "9_9") (pintype "passive"))
      (node (ref "VSLUE11") (pin "15") (pinfunction "2A3_15") (pintype "input"))
      (node (ref "VSLUE11") (pin "17") (pinfunction "2A4_17") (pintype "input"))
    )
    (net (code "25") (name "/GPIO_07_B5") (class "Default")
      (node (ref "OJ71") (pin "1") (pinfunction "1_1") (pintype "bidirectional"))
      (node (ref "SV1") (pin "10") (pinfunction "10_10") (pintype "passive"))
      (node (ref "VSLUE8") (pin "2") (pinfunction "1A1_2") (pintype "input"))
      (node (ref "VSLUE8") (pin "4") (pinfunction "1A2_4") (pintype "input"))
    )
    (net (code "26") (name "/GPIO_08_A5") (class "Default")
      (node (ref "OJ72") (pin "1") (pinfunction "1_1") (pintype "bidirectional"))
      (node (ref "SV1") (pin "13") (pinfunction "13_13") (pintype "passive"))
      (node (ref "VSLUE8") (pin "6") (pinfunction "1A3_6") (pintype "input"))
      (node (ref "VSLUE8") (pin "8") (pinfunction "1A4_8") (pintype "input"))
    )
    (net (code "27") (name "/GPIO_09_D5") (class "Default")
      (node (ref "OJ69") (pin "1") (pinfunction "1_1") (pintype "bidirectional"))
      (node (ref "SV1") (pin "14") (pinfunction "14_14") (pintype "passive"))
      (node (ref "VSLUE8") (pin "15") (pinfunction "2A3_15") (pintype "input"))
      (node (ref "VSLUE8") (pin "17") (pinfunction "2A4_17") (pintype "input"))
    )
    (net (code "28") (name "/GPIO_010_B6") (class "Default")
      (node (ref "OJ47") (pin "1") (pinfunction "1_1") (pintype "bidirectional"))
      (node (ref "SV1") (pin "15") (pinfunction "15_15") (pintype "passive"))
      (node (ref "VSLUE5") (pin "2") (pinfunction "1A1_2") (pintype "input"))
      (node (ref "VSLUE5") (pin "4") (pinfunction "1A2_4") (pintype "input"))
    )
    (net (code "29") (name "/GPIO_10_F13_SERIALIN") (class "Default")
      (node (ref "J3") (pin "2") (pinfunction "P$2_2") (pintype "bidirectional"))
      (node (ref "PIN_ANALOG_21") (pin "11") (pinfunction "11_11") (pintype "passive"))
      (node (ref "SV2") (pin "2") (pinfunction "2_2") (pintype "passive"))
    )
    (net (code "30") (name "/GPIO_011_A6") (class "Default")
      (node (ref "OJ48") (pin "1") (pinfunction "1_1") (pintype "bidirectional"))
      (node (ref "SV1") (pin "16") (pinfunction "16_16") (pintype "passive"))
      (node (ref "VSLUE5") (pin "6") (pinfunction "1A3_6") (pintype "input"))
      (node (ref "VSLUE5") (pin "8") (pinfunction "1A4_8") (pintype "input"))
    )
    (net (code "31") (name "/GPIO_11_T15_TRIGOUT") (class "Default")
      (node (ref "J40") (pin "2") (pinfunction "2_2") (pintype "bidirectional"))
      (node (ref "PIN_ANALOG_21") (pin "7") (pinfunction "7_7") (pintype "passive"))
      (node (ref "R39") (pin "P$2") (pinfunction "2_P$2") (pintype "passive"))
      (node (ref "SV2") (pin "4") (pinfunction "4_4") (pintype "passive"))
      (node (ref "T15_B23N_TRIGOUT") (pin "1") (pinfunction "1_1") (pintype "passive"))
    )
    (net (code "32") (name "/GPIO_012_B7") (class "Default")
      (node (ref "B7_T9P") (pin "1") (pinfunction "1_1") (pintype "passive"))
      (node (ref "J49") (pin "2") (pinfunction "2_2") (pintype "bidirectional"))
      (node (ref "R50") (pin "P$2") (pinfunction "2_P$2") (pintype "passive"))
      (node (ref "SV1") (pin "17") (pinfunction "17_17") (pintype "passive"))
    )
    (net (code "33") (name "/GPIO_12_T14_SPARE") (class "Default")
      (node (ref "J4") (pin "2") (pinfunction "2_2") (pintype "bidirectional"))
      (node (ref "PIN_ANALOG_21") (pin "3") (pinfunction "3_3") (pintype "passive"))
      (node (ref "R4") (pin "P$2") (pinfunction "2_P$2") (pintype "passive"))
      (node (ref "SV2") (pin "5") (pinfunction "5_5") (pintype "passive"))
      (node (ref "T14_B23P_SPARE") (pin "1") (pinfunction "1_1") (pintype "passive"))
    )
    (net (code "34") (name "/GPIO_013_D6") (class "Default")
      (node (ref "OJ55") (pin "1") (pinfunction "1_1") (pintype "bidirectional"))
      (node (ref "SV1") (pin "18") (pinfunction "18_18") (pintype "passive"))
      (node (ref "VSLUE6") (pin "2") (pinfunction "1A1_2") (pintype "input"))
      (node (ref "VSLUE6") (pin "4") (pinfunction "1A2_4") (pintype "input"))
    )
    (net (code "35") (name "/GPIO_13_T13") (class "Default")
      (node (ref "J38") (pin "2") (pinfunction "2_2") (pintype "bidirectional"))
      (node (ref "PIN_AIN_PWRGND21") (pin "7") (pinfunction "7_7") (pintype "passive"))
      (node (ref "R32") (pin "P$2") (pinfunction "2_P$2") (pintype "passive"))
      (node (ref "SV2") (pin "6") (pinfunction "6_6") (pintype "passive"))
      (node (ref "T13_B20N") (pin "1") (pinfunction "1_1") (pintype "passive"))
    )
    (net (code "36") (name "/GPIO_014_A7") (class "Default")
      (node (ref "A7_T9N") (pin "1") (pinfunction "1_1") (pintype "passive"))
      (node (ref "J35") (pin "2") (pinfunction "2_2") (pintype "bidirectional"))
      (node (ref "R33") (pin "P$2") (pinfunction "2_P$2") (pintype "passive"))
      (node (ref "SV1") (pin "19") (pinfunction "19_19") (pintype "passive"))
    )
    (net (code "37") (name "/GPIO_14_R13") (class "Default")
      (node (ref "J17") (pin "2") (pinfunction "2_2") (pintype "bidirectional"))
      (node (ref "PIN_AIN_PWRGND21") (pin "5") (pinfunction "5_5") (pintype "passive"))
      (node (ref "R13_B20P") (pin "1") (pinfunction "1_1") (pintype "passive"))
      (node (ref "R161") (pin "P$2") (pinfunction "2_P$2") (pintype "passive"))
      (node (ref "SV2") (pin "7") (pinfunction "7_7") (pintype "passive"))
    )
    (net (code "38") (name "/GPIO_015_C6") (class "Default")
      (node (ref "OJ56") (pin "1") (pinfunction "1_1") (pintype "bidirectional"))
      (node (ref "SV1") (pin "20") (pinfunction "20_20") (pintype "passive"))
      (node (ref "VSLUE6") (pin "6") (pinfunction "1A3_6") (pintype "input"))
      (node (ref "VSLUE6") (pin "8") (pinfunction "1A4_8") (pintype "input"))
    )
    (net (code "39") (name "/GPIO_15_T12") (class "Default")
      (node (ref "J9") (pin "2") (pinfunction "2_2") (pintype "bidirectional"))
      (node (ref "R100") (pin "P$2") (pinfunction "2_P$2") (pintype "passive"))
      (node (ref "SV2") (pin "8") (pinfunction "8_8") (pintype "passive"))
      (node (ref "T12_B18N") (pin "1") (pinfunction "1_1") (pintype "passive"))
    )
    (net (code "40") (name "/GPIO_016_C8") (class "Default")
      (node (ref "OJ53") (pin "1") (pinfunction "1_1") (pintype "bidirectional"))
      (node (ref "SV1") (pin "21") (pinfunction "21_21") (pintype "passive"))
      (node (ref "VSLUE6") (pin "15") (pinfunction "2A3_15") (pintype "input"))
      (node (ref "VSLUE6") (pin "17") (pinfunction "2A4_17") (pintype "input"))
    )
    (net (code "41") (name "/GPIO_16_R12") (class "Default")
      (node (ref "J10") (pin "2") (pinfunction "2_2") (pintype "bidirectional"))
      (node (ref "R111") (pin "P$2") (pinfunction "2_P$2") (pintype "passive"))
      (node (ref "R12_B18P") (pin "1") (pinfunction "1_1") (pintype "passive"))
      (node (ref "SV2") (pin "9") (pinfunction "9_9") (pintype "passive"))
    )
    (net (code "42") (name "/GPIO_017_E6") (class "Default")
      (node (ref "OJ54") (pin "1") (pinfunction "1_1") (pintype "bidirectional"))
      (node (ref "SV1") (pin "22") (pinfunction "22_22") (pintype "passive"))
      (node (ref "VSLUE6") (pin "11") (pinfunction "2A1_11") (pintype "input"))
      (node (ref "VSLUE6") (pin "13") (pinfunction "2A2_13") (pintype "input"))
    )
    (net (code "43") (name "/GPIO_17_T11_TRIGIN") (class "Default")
      (node (ref "J3") (pin "3") (pinfunction "P$3_3") (pintype "bidirectional"))
      (node (ref "PIN_ANALOG_21") (pin "9") (pinfunction "9_9") (pintype "passive"))
      (node (ref "SV2") (pin "10") (pinfunction "10_10") (pintype "passive"))
    )
    (net (code "44") (name "/GPIO_018_E7") (class "Default")
      (node (ref "OJ64") (pin "1") (pinfunction "1_1") (pintype "bidirectional"))
      (node (ref "SV1") (pin "23") (pinfunction "23_23") (pintype "passive"))
      (node (ref "VSLUE7") (pin "6") (pinfunction "1A3_6") (pintype "input"))
      (node (ref "VSLUE7") (pin "8") (pinfunction "1A4_8") (pintype "input"))
    )
    (net (code "45") (name "/GPIO_18_T10") (class "Default")
      (node (ref "J51") (pin "2") (pinfunction "2_2") (pintype "bidirectional"))
      (node (ref "R53") (pin "P$2") (pinfunction "2_P$2") (pintype "passive"))
      (node (ref "SV2") (pin "13") (pinfunction "13_13") (pintype "passive"))
      (node (ref "T10_B16N") (pin "1") (pinfunction "1_1") (pintype "passive"))
    )
    (net (code "46") (name "/GPIO_019_D8") (class "Default")
      (node (ref "OJ21") (pin "1") (pinfunction "1_1") (pintype "bidirectional"))
      (node (ref "SV1") (pin "24") (pinfunction "24_24") (pintype "passive"))
      (node (ref "VSLUE2") (pin "15") (pinfunction "2A3_15") (pintype "input"))
      (node (ref "VSLUE2") (pin "17") (pinfunction "2A4_17") (pintype "input"))
    )
    (net (code "47") (name "/GPIO_19_R11_SERIALOUT") (class "Default")
      (node (ref "J3") (pin "1") (pinfunction "P$1_1") (pintype "bidirectional"))
      (node (ref "PIN_ANALOG_21") (pin "13") (pinfunction "13_13") (pintype "passive"))
      (node (ref "SV2") (pin "14") (pinfunction "14_14") (pintype "passive"))
    )
    (net (code "48") (name "/GPIO_20_A14") (class "Default")
      (node (ref "A14_CLKOUT_2N") (pin "1") (pinfunction "1_1") (pintype "passive"))
      (node (ref "J1") (pin "5") (pinfunction "5_5") (pintype "passive"))
      (node (ref "J31") (pin "2") (pinfunction "2_2") (pintype "bidirectional"))
      (node (ref "R29") (pin "P$2") (pinfunction "2_P$2") (pintype "passive"))
    )
    (net (code "49") (name "/GPIO_020_E8") (class "Default")
      (node (ref "E8_T10N") (pin "1") (pinfunction "1_1") (pintype "passive"))
      (node (ref "J41") (pin "2") (pinfunction "2_2") (pintype "bidirectional"))
      (node (ref "R40") (pin "P$2") (pinfunction "2_P$2") (pintype "passive"))
      (node (ref "SV1") (pin "25") (pinfunction "25_25") (pintype "passive"))
    )
    (net (code "50") (name "/GPIO_21_B16") (class "Default")
      (node (ref "J1") (pin "6") (pinfunction "6_6") (pintype "passive"))
      (node (ref "OJ22") (pin "1") (pinfunction "1_1") (pintype "bidirectional"))
      (node (ref "VSLUE2") (pin "11") (pinfunction "2A1_11") (pintype "input"))
      (node (ref "VSLUE2") (pin "13") (pinfunction "2A2_13") (pintype "input"))
    )
    (net (code "51") (name "/GPIO_021_F8") (class "Default")
      (node (ref "F8_T10P") (pin "1") (pinfunction "1_1") (pintype "passive"))
      (node (ref "J18") (pin "2") (pinfunction "2_2") (pintype "bidirectional"))
      (node (ref "R21") (pin "P$2") (pinfunction "2_P$2") (pintype "passive"))
      (node (ref "SV1") (pin "26") (pinfunction "26_26") (pintype "passive"))
    )
    (net (code "52") (name "/GPIO_22_C14") (class "Default")
      (node (ref "J1") (pin "7") (pinfunction "7_7") (pintype "passive"))
      (node (ref "OJ32") (pin "1") (pinfunction "1_1") (pintype "bidirectional"))
      (node (ref "VSLUE3") (pin "6") (pinfunction "1A3_6") (pintype "input"))
      (node (ref "VSLUE3") (pin "8") (pinfunction "1A4_8") (pintype "input"))
    )
    (net (code "53") (name "/GPIO_022_F9") (class "Default")
      (node (ref "OJ62") (pin "1") (pinfunction "1_1") (pintype "bidirectional"))
      (node (ref "SV1") (pin "27") (pinfunction "27_27") (pintype "passive"))
      (node (ref "VSLUE7") (pin "11") (pinfunction "2A1_11") (pintype "input"))
      (node (ref "VSLUE7") (pin "13") (pinfunction "2A2_13") (pintype "input"))
    )
    (net (code "54") (name "/GPIO_23_C16") (class "Default")
      (node (ref "J1") (pin "8") (pinfunction "8_8") (pintype "passive"))
      (node (ref "OJ63") (pin "1") (pinfunction "1_1") (pintype "bidirectional"))
      (node (ref "VSLUE7") (pin "2") (pinfunction "1A1_2") (pintype "input"))
      (node (ref "VSLUE7") (pin "4") (pinfunction "1A2_4") (pintype "input"))
    )
    (net (code "55") (name "/GPIO_023_E9") (class "Default")
      (node (ref "OJ24") (pin "1") (pinfunction "1_1") (pintype "bidirectional"))
      (node (ref "SV1") (pin "28") (pinfunction "28_28") (pintype "passive"))
      (node (ref "VSLUE2") (pin "6") (pinfunction "1A3_6") (pintype "input"))
      (node (ref "VSLUE2") (pin "8") (pinfunction "1A4_8") (pintype "input"))
    )
    (net (code "56") (name "/GPIO_024_C9") (class "Default")
      (node (ref "C9_T15N") (pin "1") (pinfunction "1_1") (pintype "passive"))
      (node (ref "J8") (pin "2") (pinfunction "2_2") (pintype "bidirectional"))
      (node (ref "PIN_ANALOG_21") (pin "4") (pinfunction "4_4") (pintype "passive"))
      (node (ref "R91") (pin "P$2") (pinfunction "2_P$2") (pintype "passive"))
      (node (ref "SV1") (pin "31") (pinfunction "31_31") (pintype "passive"))
    )
    (net (code "57") (name "/GPIO_24_C15") (class "Default")
      (node (ref "J1") (pin "9") (pinfunction "9_9") (pintype "passive"))
      (node (ref "OJ31") (pin "1") (pinfunction "1_1") (pintype "bidirectional"))
      (node (ref "VSLUE3") (pin "2") (pinfunction "1A1_2") (pintype "input"))
      (node (ref "VSLUE3") (pin "4") (pinfunction "1A2_4") (pintype "input"))
    )
    (net (code "58") (name "/GPIO_025_D9") (class "Default")
      (node (ref "D9_T15P") (pin "1") (pinfunction "1_1") (pintype "passive"))
      (node (ref "J11") (pin "2") (pinfunction "2_2") (pintype "bidirectional"))
      (node (ref "PIN_ANALOG_21") (pin "6") (pinfunction "6_6") (pintype "passive"))
      (node (ref "R141") (pin "P$2") (pinfunction "2_P$2") (pintype "passive"))
      (node (ref "SV1") (pin "32") (pinfunction "32_32") (pintype "passive"))
    )
    (net (code "59") (name "/GPIO_25_D16") (class "Default")
      (node (ref "J1") (pin "10") (pinfunction "10_10") (pintype "passive"))
      (node (ref "OJ39") (pin "1") (pinfunction "1_1") (pintype "bidirectional"))
      (node (ref "VSLUE4") (pin "2") (pinfunction "1A1_2") (pintype "input"))
      (node (ref "VSLUE4") (pin "4") (pinfunction "1A2_4") (pintype "input"))
    )
    (net (code "60") (name "/GPIO_26_D15") (class "Default")
      (node (ref "J1") (pin "11") (pinfunction "11_11") (pintype "passive"))
      (node (ref "OJ29") (pin "1") (pinfunction "1_1") (pintype "bidirectional"))
      (node (ref "VSLUE3") (pin "15") (pinfunction "2A3_15") (pintype "input"))
      (node (ref "VSLUE3") (pin "17") (pinfunction "2A4_17") (pintype "input"))
    )
    (net (code "61") (name "/GPIO_026_E11") (class "Default")
      (node (ref "OJ79") (pin "1") (pinfunction "1_1") (pintype "bidirectional"))
      (node (ref "SV1") (pin "33") (pinfunction "33_33") (pintype "passive"))
      (node (ref "VSLUE9") (pin "2") (pinfunction "1A1_2") (pintype "input"))
      (node (ref "VSLUE9") (pin "4") (pinfunction "1A2_4") (pintype "input"))
    )
    (net (code "62") (name "/GPIO_27_D14") (class "Default")
      (node (ref "J1") (pin "12") (pinfunction "12_12") (pintype "passive"))
      (node (ref "OJ40") (pin "1") (pinfunction "1_1") (pintype "bidirectional"))
      (node (ref "VSLUE4") (pin "6") (pinfunction "1A3_6") (pintype "input"))
      (node (ref "VSLUE4") (pin "8") (pinfunction "1A4_8") (pintype "input"))
    )
    (net (code "63") (name "/GPIO_027_E10") (class "Default")
      (node (ref "OJ5") (pin "1") (pinfunction "1_1") (pintype "bidirectional"))
      (node (ref "SV1") (pin "34") (pinfunction "34_34") (pintype "passive"))
      (node (ref "VSLUE") (pin "15") (pinfunction "2A3_15") (pintype "input"))
      (node (ref "VSLUE") (pin "17") (pinfunction "2A4_17") (pintype "input"))
    )
    (net (code "64") (name "/GPIO_028_C11") (class "Default")
      (node (ref "OJ78") (pin "1") (pinfunction "1_1") (pintype "bidirectional"))
      (node (ref "SV1") (pin "35") (pinfunction "35_35") (pintype "passive"))
      (node (ref "VSLUE9") (pin "11") (pinfunction "2A1_11") (pintype "input"))
      (node (ref "VSLUE9") (pin "13") (pinfunction "2A2_13") (pintype "input"))
    )
    (net (code "65") (name "/GPIO_28_F15") (class "Default")
      (node (ref "J1") (pin "13") (pinfunction "13_13") (pintype "passive"))
      (node (ref "OJ37") (pin "1") (pinfunction "1_1") (pintype "bidirectional"))
      (node (ref "VSLUE4") (pin "15") (pinfunction "2A3_15") (pintype "input"))
      (node (ref "VSLUE4") (pin "17") (pinfunction "2A4_17") (pintype "input"))
    )
    (net (code "66") (name "/GPIO_029_B11") (class "Default")
      (node (ref "OJ6") (pin "1") (pinfunction "1_1") (pintype "bidirectional"))
      (node (ref "SV1") (pin "36") (pinfunction "36_36") (pintype "passive"))
      (node (ref "VSLUE") (pin "11") (pinfunction "2A1_11") (pintype "input"))
      (node (ref "VSLUE") (pin "13") (pinfunction "2A2_13") (pintype "input"))
    )
    (net (code "67") (name "/GPIO_29_F16") (class "Default")
      (node (ref "J1") (pin "14") (pinfunction "14_14") (pintype "passive"))
      (node (ref "OJ38") (pin "1") (pinfunction "1_1") (pintype "bidirectional"))
      (node (ref "VSLUE4") (pin "11") (pinfunction "2A1_11") (pintype "input"))
      (node (ref "VSLUE4") (pin "13") (pinfunction "2A2_13") (pintype "input"))
    )
    (net (code "68") (name "/GPIO_030_A12") (class "Default")
      (node (ref "A12_T21N") (pin "1") (pinfunction "1_1") (pintype "passive"))
      (node (ref "J36") (pin "2") (pinfunction "2_2") (pintype "bidirectional"))
      (node (ref "R9") (pin "P$2") (pinfunction "2_P$2") (pintype "passive"))
      (node (ref "SV1") (pin "37") (pinfunction "37_37") (pintype "passive"))
    )
    (net (code "69") (name "/GPIO_031_D11") (class "Default")
      (node (ref "OJ8") (pin "1") (pinfunction "1_1") (pintype "bidirectional"))
      (node (ref "SV1") (pin "38") (pinfunction "38_38") (pintype "passive"))
      (node (ref "VSLUE") (pin "6") (pinfunction "1A3_6") (pintype "input"))
      (node (ref "VSLUE") (pin "8") (pinfunction "1A4_8") (pintype "input"))
    )
    (net (code "70") (name "/GPIO_032_D12") (class "Default")
      (node (ref "OJ95") (pin "1") (pinfunction "1_1") (pintype "bidirectional"))
      (node (ref "SV1") (pin "39") (pinfunction "39_39") (pintype "passive"))
      (node (ref "VSLUE11") (pin "2") (pinfunction "1A1_2") (pintype "input"))
      (node (ref "VSLUE11") (pin "4") (pinfunction "1A2_4") (pintype "input"))
    )
    (net (code "71") (name "/GPIO_033_B12") (class "Default")
      (node (ref "B12_T21P") (pin "1") (pinfunction "1_1") (pintype "passive"))
      (node (ref "J37") (pin "2") (pinfunction "2_2") (pintype "bidirectional"))
      (node (ref "R11") (pin "P$2") (pinfunction "2_P$2") (pintype "passive"))
      (node (ref "SV1") (pin "40") (pinfunction "40_40") (pintype "passive"))
    )
    (net (code "72") (name "/GPIO_110_P11") (class "Default")
      (node (ref "OJ80") (pin "1") (pinfunction "1_1") (pintype "bidirectional"))
      (node (ref "SV2") (pin "15") (pinfunction "15_15") (pintype "passive"))
      (node (ref "VSLUE9") (pin "6") (pinfunction "1A3_6") (pintype "input"))
      (node (ref "VSLUE9") (pin "8") (pinfunction "1A4_8") (pintype "input"))
    )
    (net (code "73") (name "/GPIO_111_R10") (class "Default")
      (node (ref "J48") (pin "2") (pinfunction "2_2") (pintype "bidirectional"))
      (node (ref "R10_B16P") (pin "1") (pinfunction "1_1") (pintype "passive"))
      (node (ref "R49") (pin "P$2") (pinfunction "2_P$2") (pintype "passive"))
      (node (ref "SV2") (pin "16") (pinfunction "16_16") (pintype "passive"))
    )
    (net (code "74") (name "/GPIO_112_N12") (class "Default")
      (node (ref "OJ23") (pin "1") (pinfunction "1_1") (pintype "bidirectional"))
      (node (ref "SV2") (pin "17") (pinfunction "17_17") (pintype "passive"))
      (node (ref "VSLUE2") (pin "2") (pinfunction "1A1_2") (pintype "input"))
      (node (ref "VSLUE2") (pin "4") (pinfunction "1A2_4") (pintype "input"))
    )
    (net (code "75") (name "/GPIO_113_P9") (class "Default")
      (node (ref "OJ45") (pin "1") (pinfunction "1_1") (pintype "bidirectional"))
      (node (ref "SV2") (pin "18") (pinfunction "18_18") (pintype "passive"))
      (node (ref "VSLUE5") (pin "15") (pinfunction "2A3_15") (pintype "input"))
      (node (ref "VSLUE5") (pin "17") (pinfunction "2A4_17") (pintype "input"))
    )
    (net (code "76") (name "/GPIO_114_N9") (class "Default")
      (node (ref "J3") (pin "4") (pinfunction "P$4_4") (pintype "bidirectional"))
      (node (ref "LED1") (pin "A") (pinfunction "A_A") (pintype "passive"))
      (node (ref "R17") (pin "1") (pinfunction "1_1") (pintype "passive"))
      (node (ref "SV2") (pin "19") (pinfunction "19_19") (pintype "passive"))
      (node (ref "VSLUE") (pin "1") (pinfunction "~{1OE}_1") (pintype "input"))
      (node (ref "VSLUE") (pin "19") (pinfunction "~{2OE}_19") (pintype "input"))
      (node (ref "VSLUE11") (pin "1") (pinfunction "~{1OE}_1") (pintype "input"))
      (node (ref "VSLUE11") (pin "19") (pinfunction "~{2OE}_19") (pintype "input"))
      (node (ref "VSLUE2") (pin "1") (pinfunction "~{1OE}_1") (pintype "input"))
      (node (ref "VSLUE2") (pin "19") (pinfunction "~{2OE}_19") (pintype "input"))
      (node (ref "VSLUE3") (pin "1") (pinfunction "~{1OE}_1") (pintype "input"))
      (node (ref "VSLUE3") (pin "19") (pinfunction "~{2OE}_19") (pintype "input"))
      (node (ref "VSLUE4") (pin "1") (pinfunction "~{1OE}_1") (pintype "input"))
      (node (ref "VSLUE4") (pin "19") (pinfunction "~{2OE}_19") (pintype "input"))
      (node (ref "VSLUE5") (pin "1") (pinfunction "~{1OE}_1") (pintype "input"))
      (node (ref "VSLUE5") (pin "19") (pinfunction "~{2OE}_19") (pintype "input"))
      (node (ref "VSLUE6") (pin "1") (pinfunction "~{1OE}_1") (pintype "input"))
      (node (ref "VSLUE6") (pin "19") (pinfunction "~{2OE}_19") (pintype "input"))
      (node (ref "VSLUE7") (pin "1") (pinfunction "~{1OE}_1") (pintype "input"))
      (node (ref "VSLUE7") (pin "19") (pinfunction "~{2OE}_19") (pintype "input"))
      (node (ref "VSLUE8") (pin "1") (pinfunction "~{1OE}_1") (pintype "input"))
      (node (ref "VSLUE8") (pin "19") (pinfunction "~{2OE}_19") (pintype "input"))
      (node (ref "VSLUE9") (pin "1") (pinfunction "~{1OE}_1") (pintype "input"))
      (node (ref "VSLUE9") (pin "19") (pinfunction "~{2OE}_19") (pintype "input"))
    )
    (net (code "77") (name "/GPIO_115_N11") (class "Default")
      (node (ref "OJ46") (pin "1") (pinfunction "1_1") (pintype "bidirectional"))
      (node (ref "SV2") (pin "20") (pinfunction "20_20") (pintype "passive"))
      (node (ref "VSLUE5") (pin "11") (pinfunction "2A1_11") (pintype "input"))
      (node (ref "VSLUE5") (pin "13") (pinfunction "2A2_13") (pintype "input"))
    )
    (net (code "78") (name "/GPIO_116_L16") (class "Default")
      (node (ref "J32") (pin "2") (pinfunction "2_2") (pintype "bidirectional"))
      (node (ref "L16_R11N") (pin "1") (pinfunction "1_1") (pintype "passive"))
      (node (ref "PIN_ANALOG_21") (pin "12") (pinfunction "12_12") (pintype "passive"))
      (node (ref "R28") (pin "P$2") (pinfunction "2_P$2") (pintype "passive"))
      (node (ref "SV2") (pin "21") (pinfunction "21_21") (pintype "passive"))
    )
    (net (code "79") (name "/GPIO_117_K16") (class "Default")
      (node (ref "J33") (pin "2") (pinfunction "2_2") (pintype "bidirectional"))
      (node (ref "K16_R10N") (pin "1") (pinfunction "1_1") (pintype "passive"))
      (node (ref "PIN_AIN_PWRGND21") (pin "3") (pinfunction "3_3") (pintype "passive"))
      (node (ref "R30") (pin "P$2") (pinfunction "2_P$2") (pintype "passive"))
      (node (ref "SV2") (pin "22") (pinfunction "22_22") (pintype "passive"))
    )
    (net (code "80") (name "/GPIO_118_R16") (class "Default")
      (node (ref "J34") (pin "2") (pinfunction "2_2") (pintype "bidirectional"))
      (node (ref "PIN_ANALOG_21") (pin "10") (pinfunction "10_10") (pintype "passive"))
      (node (ref "R16_R15P") (pin "1") (pinfunction "1_1") (pintype "passive"))
      (node (ref "R31") (pin "P$2") (pinfunction "2_P$2") (pintype "passive"))
      (node (ref "SV2") (pin "23") (pinfunction "23_23") (pintype "passive"))
    )
    (net (code "81") (name "/GPIO_119_L15") (class "Default")
      (node (ref "J43") (pin "2") (pinfunction "2_2") (pintype "bidirectional"))
      (node (ref "L15_R11P") (pin "1") (pinfunction "1_1") (pintype "passive"))
      (node (ref "PIN_ANALOG_21") (pin "14") (pinfunction "14_14") (pintype "passive"))
      (node (ref "R43") (pin "P$2") (pinfunction "2_P$2") (pintype "passive"))
      (node (ref "SV2") (pin "24") (pinfunction "24_24") (pintype "passive"))
    )
    (net (code "82") (name "/GPIO_120_P15") (class "Default")
      (node (ref "OJ61") (pin "1") (pinfunction "1_1") (pintype "bidirectional"))
      (node (ref "SV2") (pin "25") (pinfunction "25_25") (pintype "passive"))
      (node (ref "VSLUE7") (pin "15") (pinfunction "2A3_15") (pintype "input"))
      (node (ref "VSLUE7") (pin "17") (pinfunction "2A4_17") (pintype "input"))
    )
    (net (code "83") (name "/GPIO_121_P16") (class "Default")
      (node (ref "J42") (pin "2") (pinfunction "2_2") (pintype "bidirectional"))
      (node (ref "P16_R15N") (pin "1") (pinfunction "1_1") (pintype "passive"))
      (node (ref "PIN_ANALOG_21") (pin "8") (pinfunction "8_8") (pintype "passive"))
      (node (ref "R41") (pin "P$2") (pinfunction "2_P$2") (pintype "passive"))
      (node (ref "SV2") (pin "26") (pinfunction "26_26") (pintype "passive"))
    )
    (net (code "84") (name "/GPIO_122_R14") (class "Default")
      (node (ref "J53") (pin "2") (pinfunction "2_2") (pintype "bidirectional"))
      (node (ref "R14_CLKOUT_4N") (pin "1") (pinfunction "1_1") (pintype "passive"))
      (node (ref "R46") (pin "P$2") (pinfunction "2_P$2") (pintype "passive"))
      (node (ref "SV2") (pin "27") (pinfunction "27_27") (pintype "passive"))
    )
    (net (code "85") (name "/GPIO_123_N16") (class "Default")
      (node (ref "J55") (pin "2") (pinfunction "2_2") (pintype "bidirectional"))
      (node (ref "N16_R13N") (pin "1") (pinfunction "1_1") (pintype "passive"))
      (node (ref "PIN_AIN_PWRGND21") (pin "6") (pinfunction "6_6") (pintype "passive"))
      (node (ref "R52") (pin "P$2") (pinfunction "2_P$2") (pintype "passive"))
      (node (ref "SV2") (pin "28") (pinfunction "28_28") (pintype "passive"))
    )
    (net (code "86") (name "/GPIO_124_N15") (class "Default")
      (node (ref "J54") (pin "2") (pinfunction "2_2") (pintype "bidirectional"))
      (node (ref "N15_R13P") (pin "1") (pinfunction "1_1") (pintype "passive"))
      (node (ref "PIN_AIN_PWRGND21") (pin "8") (pinfunction "8_8") (pintype "passive"))
      (node (ref "R47") (pin "P$2") (pinfunction "2_P$2") (pintype "passive"))
      (node (ref "SV2") (pin "31") (pinfunction "31_31") (pintype "passive"))
    )
    (net (code "87") (name "/GPIO_125_P14") (class "Default")
      (node (ref "J52") (pin "2") (pinfunction "2_2") (pintype "bidirectional"))
      (node (ref "P14_CLKOUT_4P") (pin "1") (pinfunction "1_1") (pintype "passive"))
      (node (ref "R45") (pin "P$2") (pinfunction "2_P$2") (pintype "passive"))
      (node (ref "SV2") (pin "32") (pinfunction "32_32") (pintype "passive"))
    )
    (net (code "88") (name "/GPIO_126_L14") (class "Default")
      (node (ref "J7") (pin "2") (pinfunction "P$2_2") (pintype "bidirectional"))
      (node (ref "SV2") (pin "33") (pinfunction "33_33") (pintype "passive"))
    )
    (net (code "89") (name "/GPIO_127_N14") (class "Default")
      (node (ref "OJ70") (pin "1") (pinfunction "1_1") (pintype "bidirectional"))
      (node (ref "SV2") (pin "34") (pinfunction "34_34") (pintype "passive"))
      (node (ref "VSLUE8") (pin "11") (pinfunction "2A1_11") (pintype "input"))
      (node (ref "VSLUE8") (pin "13") (pinfunction "2A2_13") (pintype "input"))
    )
    (net (code "90") (name "/GPIO_128_M10") (class "Default")
      (node (ref "J12") (pin "2") (pinfunction "P$2_2") (pintype "bidirectional"))
      (node (ref "SV2") (pin "35") (pinfunction "35_35") (pintype "passive"))
    )
    (net (code "91") (name "/GPIO_129_L13") (class "Default")
      (node (ref "J7") (pin "1") (pinfunction "P$1_1") (pintype "bidirectional"))
      (node (ref "SV2") (pin "36") (pinfunction "36_36") (pintype "passive"))
    )
    (net (code "92") (name "/GPIO_130_J16") (class "Default")
      (node (ref "J12") (pin "1") (pinfunction "P$1_1") (pintype "bidirectional"))
      (node (ref "SV2") (pin "37") (pinfunction "37_37") (pintype "passive"))
    )
    (net (code "93") (name "/GPIO_131_K15") (class "Default")
      (node (ref "J39") (pin "2") (pinfunction "2_2") (pintype "bidirectional"))
      (node (ref "K15_R10P") (pin "1") (pinfunction "1_1") (pintype "passive"))
      (node (ref "PIN_AIN_PWRGND21") (pin "1") (pinfunction "1_1") (pintype "passive"))
      (node (ref "R35") (pin "P$2") (pinfunction "2_P$2") (pintype "passive"))
      (node (ref "SV2") (pin "38") (pinfunction "38_38") (pintype "passive"))
    )
    (net (code "94") (name "/GPIO_132_J13") (class "Default")
      (node (ref "OJ77") (pin "1") (pinfunction "1_1") (pintype "bidirectional"))
      (node (ref "SV2") (pin "39") (pinfunction "39_39") (pintype "passive"))
      (node (ref "VSLUE9") (pin "15") (pinfunction "2A3_15") (pintype "input"))
      (node (ref "VSLUE9") (pin "17") (pinfunction "2A4_17") (pintype "input"))
    )
    (net (code "95") (name "/GPIO_133_J14") (class "Default")
      (node (ref "OJ7") (pin "1") (pinfunction "1_1") (pintype "bidirectional"))
      (node (ref "SV2") (pin "40") (pinfunction "40_40") (pintype "passive"))
      (node (ref "VSLUE") (pin "2") (pinfunction "1A1_2") (pintype "input"))
      (node (ref "VSLUE") (pin "4") (pinfunction "1A2_4") (pintype "input"))
    )
    (net (code "96") (name "/GPIO_210_F14") (class "Default")
      (node (ref "J1") (pin "15") (pinfunction "15_15") (pintype "passive"))
      (node (ref "OJ30") (pin "1") (pinfunction "1_1") (pintype "bidirectional"))
      (node (ref "VSLUE3") (pin "11") (pinfunction "2A1_11") (pintype "input"))
      (node (ref "VSLUE3") (pin "13") (pinfunction "2A2_13") (pintype "input"))
    )
    (net (code "97") (name "/GPIO_211_G16") (class "Default")
      (node (ref "G16_R5N") (pin "1") (pinfunction "1_1") (pintype "passive"))
      (node (ref "J1") (pin "16") (pinfunction "16_16") (pintype "passive"))
      (node (ref "J28") (pin "2") (pinfunction "2_2") (pintype "bidirectional"))
      (node (ref "PIN_AIN_PWRGND21") (pin "11") (pinfunction "11_11") (pintype "passive"))
      (node (ref "R24") (pin "P$2") (pinfunction "2_P$2") (pintype "passive"))
    )
    (net (code "98") (name "/GPIO_212_G15") (class "Default")
      (node (ref "G15_R5P") (pin "1") (pinfunction "1_1") (pintype "passive"))
      (node (ref "J1") (pin "17") (pinfunction "17_17") (pintype "passive"))
      (node (ref "J29") (pin "2") (pinfunction "2_2") (pintype "bidirectional"))
      (node (ref "PIN_AIN_PWRGND21") (pin "9") (pinfunction "9_9") (pintype "passive"))
      (node (ref "R26") (pin "P$2") (pinfunction "2_P$2") (pintype "passive"))
    )
    (net (code "99") (name "GND") (class "Default")
      (node (ref "A12_T21N") (pin "2") (pinfunction "2_2") (pintype "passive"))
      (node (ref "A12_T21N") (pin "3") (pinfunction "2_3") (pintype "passive"))
      (node (ref "A12_T21N") (pin "4") (pinfunction "2_4") (pintype "passive"))
      (node (ref "A12_T21N") (pin "5") (pinfunction "2_5") (pintype "passive"))
      (node (ref "A14_CLKOUT_2N") (pin "2") (pinfunction "2_2") (pintype "passive"))
      (node (ref "A14_CLKOUT_2N") (pin "3") (pinfunction "2_3") (pintype "passive"))
      (node (ref "A14_CLKOUT_2N") (pin "4") (pinfunction "2_4") (pintype "passive"))
      (node (ref "A14_CLKOUT_2N") (pin "5") (pinfunction "2_5") (pintype "passive"))
      (node (ref "A2_T2N") (pin "2") (pinfunction "2_2") (pintype "passive"))
      (node (ref "A2_T2N") (pin "3") (pinfunction "2_3") (pintype "passive"))
      (node (ref "A2_T2N") (pin "4") (pinfunction "2_4") (pintype "passive"))
      (node (ref "A2_T2N") (pin "5") (pinfunction "2_5") (pintype "passive"))
      (node (ref "A3_T2P") (pin "2") (pinfunction "2_2") (pintype "passive"))
      (node (ref "A3_T2P") (pin "3") (pinfunction "2_3") (pintype "passive"))
      (node (ref "A3_T2P") (pin "4") (pinfunction "2_4") (pintype "passive"))
      (node (ref "A3_T2P") (pin "5") (pinfunction "2_5") (pintype "passive"))
      (node (ref "A4") (pin "2") (pinfunction "2_2") (pintype "passive"))
      (node (ref "A4") (pin "3") (pinfunction "2_3") (pintype "passive"))
      (node (ref "A4") (pin "4") (pinfunction "2_4") (pintype "passive"))
      (node (ref "A4") (pin "5") (pinfunction "2_5") (pintype "passive"))
      (node (ref "A5") (pin "2") (pinfunction "2_2") (pintype "passive"))
      (node (ref "A5") (pin "3") (pinfunction "2_3") (pintype "passive"))
      (node (ref "A5") (pin "4") (pinfunction "2_4") (pintype "passive"))
      (node (ref "A5") (pin "5") (pinfunction "2_5") (pintype "passive"))
      (node (ref "A6") (pin "2") (pinfunction "2_2") (pintype "passive"))
      (node (ref "A6") (pin "3") (pinfunction "2_3") (pintype "passive"))
      (node (ref "A6") (pin "4") (pinfunction "2_4") (pintype "passive"))
      (node (ref "A6") (pin "5") (pinfunction "2_5") (pintype "passive"))
      (node (ref "A7_T9N") (pin "2") (pinfunction "2_2") (pintype "passive"))
      (node (ref "A7_T9N") (pin "3") (pinfunction "2_3") (pintype "passive"))
      (node (ref "A7_T9N") (pin "4") (pinfunction "2_4") (pintype "passive"))
      (node (ref "A7_T9N") (pin "5") (pinfunction "2_5") (pintype "passive"))
      (node (ref "A8CLK_4N") (pin "2") (pinfunction "2_2") (pintype "passive"))
      (node (ref "A8CLK_4N") (pin "3") (pinfunction "2_3") (pintype "passive"))
      (node (ref "A8CLK_4N") (pin "4") (pinfunction "2_4") (pintype "passive"))
      (node (ref "A8CLK_4N") (pin "5") (pinfunction "2_5") (pintype "passive"))
      (node (ref "B11") (pin "2") (pinfunction "2_2") (pintype "passive"))
      (node (ref "B11") (pin "3") (pinfunction "2_3") (pintype "passive"))
      (node (ref "B11") (pin "4") (pinfunction "2_4") (pintype "passive"))
      (node (ref "B11") (pin "5") (pinfunction "2_5") (pintype "passive"))
      (node (ref "B12_T21P") (pin "2") (pinfunction "2_2") (pintype "passive"))
      (node (ref "B12_T21P") (pin "3") (pinfunction "2_3") (pintype "passive"))
      (node (ref "B12_T21P") (pin "4") (pinfunction "2_4") (pintype "passive"))
      (node (ref "B12_T21P") (pin "5") (pinfunction "2_5") (pintype "passive"))
      (node (ref "B16") (pin "2") (pinfunction "2_2") (pintype "passive"))
      (node (ref "B16") (pin "3") (pinfunction "2_3") (pintype "passive"))
      (node (ref "B16") (pin "4") (pinfunction "2_4") (pintype "passive"))
      (node (ref "B16") (pin "5") (pinfunction "2_5") (pintype "passive"))
      (node (ref "B3") (pin "2") (pinfunction "2_2") (pintype "passive"))
      (node (ref "B3") (pin "3") (pinfunction "2_3") (pintype "passive"))
      (node (ref "B3") (pin "4") (pinfunction "2_4") (pintype "passive"))
      (node (ref "B3") (pin "5") (pinfunction "2_5") (pintype "passive"))
      (node (ref "B4") (pin "2") (pinfunction "2_2") (pintype "passive"))
      (node (ref "B4") (pin "3") (pinfunction "2_3") (pintype "passive"))
      (node (ref "B4") (pin "4") (pinfunction "2_4") (pintype "passive"))
      (node (ref "B4") (pin "5") (pinfunction "2_5") (pintype "passive"))
      (node (ref "B5") (pin "2") (pinfunction "2_2") (pintype "passive"))
      (node (ref "B5") (pin "3") (pinfunction "2_3") (pintype "passive"))
      (node (ref "B5") (pin "4") (pinfunction "2_4") (pintype "passive"))
      (node (ref "B5") (pin "5") (pinfunction "2_5") (pintype "passive"))
      (node (ref "B6") (pin "2") (pinfunction "2_2") (pintype "passive"))
      (node (ref "B6") (pin "3") (pinfunction "2_3") (pintype "passive"))
      (node (ref "B6") (pin "4") (pinfunction "2_4") (pintype "passive"))
      (node (ref "B6") (pin "5") (pinfunction "2_5") (pintype "passive"))
      (node (ref "B7_T9P") (pin "2") (pinfunction "2_2") (pintype "passive"))
      (node (ref "B7_T9P") (pin "3") (pinfunction "2_3") (pintype "passive"))
      (node (ref "B7_T9P") (pin "4") (pinfunction "2_4") (pintype "passive"))
      (node (ref "B7_T9P") (pin "5") (pinfunction "2_5") (pintype "passive"))
      (node (ref "B8CLK_4P") (pin "2") (pinfunction "2_2") (pintype "passive"))
      (node (ref "B8CLK_4P") (pin "3") (pinfunction "2_3") (pintype "passive"))
      (node (ref "B8CLK_4P") (pin "4") (pinfunction "2_4") (pintype "passive"))
      (node (ref "B8CLK_4P") (pin "5") (pinfunction "2_5") (pintype "passive"))
      (node (ref "C10") (pin "1") (pinfunction "1_1") (pintype "passive"))
      (node (ref "C11") (pin "2") (pinfunction "2_2") (pintype "passive"))
      (node (ref "C11") (pin "3") (pinfunction "2_3") (pintype "passive"))
      (node (ref "C11") (pin "4") (pinfunction "2_4") (pintype "passive"))
      (node (ref "C11") (pin "5") (pinfunction "2_5") (pintype "passive"))
      (node (ref "C14") (pin "2") (pinfunction "2_2") (pintype "passive"))
      (node (ref "C14") (pin "3") (pinfunction "2_3") (pintype "passive"))
      (node (ref "C14") (pin "4") (pinfunction "2_4") (pintype "passive"))
      (node (ref "C14") (pin "5") (pinfunction "2_5") (pintype "passive"))
      (node (ref "C15") (pin "2") (pinfunction "2_2") (pintype "passive"))
      (node (ref "C15") (pin "3") (pinfunction "2_3") (pintype "passive"))
      (node (ref "C15") (pin "4") (pinfunction "2_4") (pintype "passive"))
      (node (ref "C15") (pin "5") (pinfunction "2_5") (pintype "passive"))
      (node (ref "C16") (pin "2") (pinfunction "2_2") (pintype "passive"))
      (node (ref "C16") (pin "3") (pinfunction "2_3") (pintype "passive"))
      (node (ref "C16") (pin "4") (pinfunction "2_4") (pintype "passive"))
      (node (ref "C16") (pin "5") (pinfunction "2_5") (pintype "passive"))
      (node (ref "C2") (pin "1") (pinfunction "1_1") (pintype "passive"))
      (node (ref "C3_CLKOUT_3N") (pin "2") (pinfunction "2_2") (pintype "passive"))
      (node (ref "C3_CLKOUT_3N") (pin "3") (pinfunction "2_3") (pintype "passive"))
      (node (ref "C3_CLKOUT_3N") (pin "4") (pinfunction "2_4") (pintype "passive"))
      (node (ref "C3_CLKOUT_3N") (pin "5") (pinfunction "2_5") (pintype "passive"))
      (node (ref "C4") (pin "1") (pinfunction "1_1") (pintype "passive"))
      (node (ref "C5") (pin "1") (pinfunction "1_1") (pintype "passive"))
      (node (ref "C6") (pin "2") (pinfunction "2_2") (pintype "passive"))
      (node (ref "C6") (pin "3") (pinfunction "2_3") (pintype "passive"))
      (node (ref "C6") (pin "4") (pinfunction "2_4") (pintype "passive"))
      (node (ref "C6") (pin "5") (pinfunction "2_5") (pintype "passive"))
      (node (ref "C8") (pin "2") (pinfunction "2_2") (pintype "passive"))
      (node (ref "C8") (pin "3") (pinfunction "2_3") (pintype "passive"))
      (node (ref "C8") (pin "4") (pinfunction "2_4") (pintype "passive"))
      (node (ref "C8") (pin "5") (pinfunction "2_5") (pintype "passive"))
      (node (ref "C91") (pin "1") (pinfunction "1_1") (pintype "passive"))
      (node (ref "C93") (pin "1") (pinfunction "1_1") (pintype "passive"))
      (node (ref "C94") (pin "1") (pinfunction "1_1") (pintype "passive"))
      (node (ref "C95") (pin "1") (pinfunction "1_1") (pintype "passive"))
      (node (ref "C96") (pin "1") (pinfunction "1_1") (pintype "passive"))
      (node (ref "C97") (pin "1") (pinfunction "1_1") (pintype "passive"))
      (node (ref "C9_T15N") (pin "2") (pinfunction "2_2") (pintype "passive"))
      (node (ref "C9_T15N") (pin "3") (pinfunction "2_3") (pintype "passive"))
      (node (ref "C9_T15N") (pin "4") (pinfunction "2_4") (pintype "passive"))
      (node (ref "C9_T15N") (pin "5") (pinfunction "2_5") (pintype "passive"))
      (node (ref "D11") (pin "2") (pinfunction "2_2") (pintype "passive"))
      (node (ref "D11") (pin "3") (pinfunction "2_3") (pintype "passive"))
      (node (ref "D11") (pin "4") (pinfunction "2_4") (pintype "passive"))
      (node (ref "D11") (pin "5") (pinfunction "2_5") (pintype "passive"))
      (node (ref "D12") (pin "2") (pinfunction "2_2") (pintype "passive"))
      (node (ref "D12") (pin "3") (pinfunction "2_3") (pintype "passive"))
      (node (ref "D12") (pin "4") (pinfunction "2_4") (pintype "passive"))
      (node (ref "D12") (pin "5") (pinfunction "2_5") (pintype "passive"))
      (node (ref "D14") (pin "2") (pinfunction "2_2") (pintype "passive"))
      (node (ref "D14") (pin "3") (pinfunction "2_3") (pintype "passive"))
      (node (ref "D14") (pin "4") (pinfunction "2_4") (pintype "passive"))
      (node (ref "D14") (pin "5") (pinfunction "2_5") (pintype "passive"))
      (node (ref "D15") (pin "2") (pinfunction "2_2") (pintype "passive"))
      (node (ref "D15") (pin "3") (pinfunction "2_3") (pintype "passive"))
      (node (ref "D15") (pin "4") (pinfunction "2_4") (pintype "passive"))
      (node (ref "D15") (pin "5") (pinfunction "2_5") (pintype "passive"))
      (node (ref "D16") (pin "2") (pinfunction "2_2") (pintype "passive"))
      (node (ref "D16") (pin "3") (pinfunction "2_3") (pintype "passive"))
      (node (ref "D16") (pin "4") (pinfunction "2_4") (pintype "passive"))
      (node (ref "D16") (pin "5") (pinfunction "2_5") (pintype "passive"))
      (node (ref "D3_CLKOUT_3P") (pin "2") (pinfunction "2_2") (pintype "passive"))
      (node (ref "D3_CLKOUT_3P") (pin "3") (pinfunction "2_3") (pintype "passive"))
      (node (ref "D3_CLKOUT_3P") (pin "4") (pinfunction "2_4") (pintype "passive"))
      (node (ref "D3_CLKOUT_3P") (pin "5") (pinfunction "2_5") (pintype "passive"))
      (node (ref "D5") (pin "2") (pinfunction "2_2") (pintype "passive"))
      (node (ref "D5") (pin "3") (pinfunction "2_3") (pintype "passive"))
      (node (ref "D5") (pin "4") (pinfunction "2_4") (pintype "passive"))
      (node (ref "D5") (pin "5") (pinfunction "2_5") (pintype "passive"))
      (node (ref "D6") (pin "2") (pinfunction "2_2") (pintype "passive"))
      (node (ref "D6") (pin "3") (pinfunction "2_3") (pintype "passive"))
      (node (ref "D6") (pin "4") (pinfunction "2_4") (pintype "passive"))
      (node (ref "D6") (pin "5") (pinfunction "2_5") (pintype "passive"))
      (node (ref "D8") (pin "2") (pinfunction "2_2") (pintype "passive"))
      (node (ref "D8") (pin "3") (pinfunction "2_3") (pintype "passive"))
      (node (ref "D8") (pin "4") (pinfunction "2_4") (pintype "passive"))
      (node (ref "D8") (pin "5") (pinfunction "2_5") (pintype "passive"))
      (node (ref "D9_T15P") (pin "2") (pinfunction "2_2") (pintype "passive"))
      (node (ref "D9_T15P") (pin "3") (pinfunction "2_3") (pintype "passive"))
      (node (ref "D9_T15P") (pin "4") (pinfunction "2_4") (pintype "passive"))
      (node (ref "D9_T15P") (pin "5") (pinfunction "2_5") (pintype "passive"))
      (node (ref "E10") (pin "2") (pinfunction "2_2") (pintype "passive"))
      (node (ref "E10") (pin "3") (pinfunction "2_3") (pintype "passive"))
      (node (ref "E10") (pin "4") (pinfunction "2_4") (pintype "passive"))
      (node (ref "E10") (pin "5") (pinfunction "2_5") (pintype "passive"))
      (node (ref "E11") (pin "2") (pinfunction "2_2") (pintype "passive"))
      (node (ref "E11") (pin "3") (pinfunction "2_3") (pintype "passive"))
      (node (ref "E11") (pin "4") (pinfunction "2_4") (pintype "passive"))
      (node (ref "E11") (pin "5") (pinfunction "2_5") (pintype "passive"))
      (node (ref "E15CLK_2P") (pin "2") (pinfunction "2_2") (pintype "passive"))
      (node (ref "E15CLK_2P") (pin "3") (pinfunction "2_3") (pintype "passive"))
      (node (ref "E15CLK_2P") (pin "4") (pinfunction "2_4") (pintype "passive"))
      (node (ref "E15CLK_2P") (pin "5") (pinfunction "2_5") (pintype "passive"))
      (node (ref "E16CLK_2N") (pin "2") (pinfunction "2_2") (pintype "passive"))
      (node (ref "E16CLK_2N") (pin "3") (pinfunction "2_3") (pintype "passive"))
      (node (ref "E16CLK_2N") (pin "4") (pinfunction "2_4") (pintype "passive"))
      (node (ref "E16CLK_2N") (pin "5") (pinfunction "2_5") (pintype "passive"))
      (node (ref "E6") (pin "2") (pinfunction "2_2") (pintype "passive"))
      (node (ref "E6") (pin "3") (pinfunction "2_3") (pintype "passive"))
      (node (ref "E6") (pin "4") (pinfunction "2_4") (pintype "passive"))
      (node (ref "E6") (pin "5") (pinfunction "2_5") (pintype "passive"))
      (node (ref "E7") (pin "2") (pinfunction "2_2") (pintype "passive"))
      (node (ref "E7") (pin "3") (pinfunction "2_3") (pintype "passive"))
      (node (ref "E7") (pin "4") (pinfunction "2_4") (pintype "passive"))
      (node (ref "E7") (pin "5") (pinfunction "2_5") (pintype "passive"))
      (node (ref "E8_T10N") (pin "2") (pinfunction "2_2") (pintype "passive"))
      (node (ref "E8_T10N") (pin "3") (pinfunction "2_3") (pintype "passive"))
      (node (ref "E8_T10N") (pin "4") (pinfunction "2_4") (pintype "passive"))
      (node (ref "E8_T10N") (pin "5") (pinfunction "2_5") (pintype "passive"))
      (node (ref "E9") (pin "2") (pinfunction "2_2") (pintype "passive"))
      (node (ref "E9") (pin "3") (pinfunction "2_3") (pintype "passive"))
      (node (ref "E9") (pin "4") (pinfunction "2_4") (pintype "passive"))
      (node (ref "E9") (pin "5") (pinfunction "2_5") (pintype "passive"))
      (node (ref "F14") (pin "2") (pinfunction "2_2") (pintype "passive"))
      (node (ref "F14") (pin "3") (pinfunction "2_3") (pintype "passive"))
      (node (ref "F14") (pin "4") (pinfunction "2_4") (pintype "passive"))
      (node (ref "F14") (pin "5") (pinfunction "2_5") (pintype "passive"))
      (node (ref "F15") (pin "2") (pinfunction "2_2") (pintype "passive"))
      (node (ref "F15") (pin "3") (pinfunction "2_3") (pintype "passive"))
      (node (ref "F15") (pin "4") (pinfunction "2_4") (pintype "passive"))
      (node (ref "F15") (pin "5") (pinfunction "2_5") (pintype "passive"))
      (node (ref "F16") (pin "2") (pinfunction "2_2") (pintype "passive"))
      (node (ref "F16") (pin "3") (pinfunction "2_3") (pintype "passive"))
      (node (ref "F16") (pin "4") (pinfunction "2_4") (pintype "passive"))
      (node (ref "F16") (pin "5") (pinfunction "2_5") (pintype "passive"))
      (node (ref "F8_T10P") (pin "2") (pinfunction "2_2") (pintype "passive"))
      (node (ref "F8_T10P") (pin "3") (pinfunction "2_3") (pintype "passive"))
      (node (ref "F8_T10P") (pin "4") (pinfunction "2_4") (pintype "passive"))
      (node (ref "F8_T10P") (pin "5") (pinfunction "2_5") (pintype "passive"))
      (node (ref "F9") (pin "2") (pinfunction "2_2") (pintype "passive"))
      (node (ref "F9") (pin "3") (pinfunction "2_3") (pintype "passive"))
      (node (ref "F9") (pin "4") (pinfunction "2_4") (pintype "passive"))
      (node (ref "F9") (pin "5") (pinfunction "2_5") (pintype "passive"))
      (node (ref "G15_R5P") (pin "2") (pinfunction "2_2") (pintype "passive"))
      (node (ref "G15_R5P") (pin "3") (pinfunction "2_3") (pintype "passive"))
      (node (ref "G15_R5P") (pin "4") (pinfunction "2_4") (pintype "passive"))
      (node (ref "G15_R5P") (pin "5") (pinfunction "2_5") (pintype "passive"))
      (node (ref "G16_R5N") (pin "2") (pinfunction "2_2") (pintype "passive"))
      (node (ref "G16_R5N") (pin "3") (pinfunction "2_3") (pintype "passive"))
      (node (ref "G16_R5N") (pin "4") (pinfunction "2_4") (pintype "passive"))
      (node (ref "G16_R5N") (pin "5") (pinfunction "2_5") (pintype "passive"))
      (node (ref "J1") (pin "26") (pinfunction "26_26") (pintype "passive"))
      (node (ref "J10") (pin "1") (pinfunction "1_1") (pintype "bidirectional"))
      (node (ref "J11") (pin "1") (pinfunction "1_1") (pintype "bidirectional"))
      (node (ref "J12") (pin "3") (pinfunction "P$3_3") (pintype "bidirectional"))
      (node (ref "J13") (pin "2") (pinfunction "2_2") (pintype "passive"))
      (node (ref "J13") (pin "3") (pinfunction "2_3") (pintype "passive"))
      (node (ref "J13") (pin "4") (pinfunction "2_4") (pintype "passive"))
      (node (ref "J13") (pin "5") (pinfunction "2_5") (pintype "passive"))
      (node (ref "J14") (pin "2") (pinfunction "2_2") (pintype "passive"))
      (node (ref "J14") (pin "3") (pinfunction "2_3") (pintype "passive"))
      (node (ref "J14") (pin "4") (pinfunction "2_4") (pintype "passive"))
      (node (ref "J14") (pin "5") (pinfunction "2_5") (pintype "passive"))
      (node (ref "J141") (pin "1") (pinfunction "1_1") (pintype "bidirectional"))
      (node (ref "J15") (pin "1") (pinfunction "1_1") (pintype "bidirectional"))
      (node (ref "J16") (pin "1") (pinfunction "1_1") (pintype "bidirectional"))
      (node (ref "J17") (pin "1") (pinfunction "1_1") (pintype "bidirectional"))
      (node (ref "J18") (pin "1") (pinfunction "1_1") (pintype "bidirectional"))
      (node (ref "J22") (pin "1") (pinfunction "1_1") (pintype "bidirectional"))
      (node (ref "J23") (pin "1") (pinfunction "1_1") (pintype "bidirectional"))
      (node (ref "J24") (pin "1") (pinfunction "1_1") (pintype "bidirectional"))
      (node (ref "J25") (pin "1") (pinfunction "1_1") (pintype "bidirectional"))
      (node (ref "J28") (pin "1") (pinfunction "1_1") (pintype "bidirectional"))
      (node (ref "J29") (pin "1") (pinfunction "1_1") (pintype "bidirectional"))
      (node (ref "J30") (pin "1") (pinfunction "1_1") (pintype "bidirectional"))
      (node (ref "J31") (pin "1") (pinfunction "1_1") (pintype "bidirectional"))
      (node (ref "J32") (pin "1") (pinfunction "1_1") (pintype "bidirectional"))
      (node (ref "J33") (pin "1") (pinfunction "1_1") (pintype "bidirectional"))
      (node (ref "J34") (pin "1") (pinfunction "1_1") (pintype "bidirectional"))
      (node (ref "J35") (pin "1") (pinfunction "1_1") (pintype "bidirectional"))
      (node (ref "J36") (pin "1") (pinfunction "1_1") (pintype "bidirectional"))
      (node (ref "J37") (pin "1") (pinfunction "1_1") (pintype "bidirectional"))
      (node (ref "J38") (pin "1") (pinfunction "1_1") (pintype "bidirectional"))
      (node (ref "J39") (pin "1") (pinfunction "1_1") (pintype "bidirectional"))
      (node (ref "J4") (pin "1") (pinfunction "1_1") (pintype "bidirectional"))
      (node (ref "J40") (pin "1") (pinfunction "1_1") (pintype "bidirectional"))
      (node (ref "J41") (pin "1") (pinfunction "1_1") (pintype "bidirectional"))
      (node (ref "J42") (pin "1") (pinfunction "1_1") (pintype "bidirectional"))
      (node (ref "J43") (pin "1") (pinfunction "1_1") (pintype "bidirectional"))
      (node (ref "J48") (pin "1") (pinfunction "1_1") (pintype "bidirectional"))
      (node (ref "J49") (pin "1") (pinfunction "1_1") (pintype "bidirectional"))
      (node (ref "J5") (pin "1") (pinfunction "1_1") (pintype "bidirectional"))
      (node (ref "J50") (pin "1") (pinfunction "1_1") (pintype "bidirectional"))
      (node (ref "J51") (pin "1") (pinfunction "1_1") (pintype "bidirectional"))
      (node (ref "J52") (pin "1") (pinfunction "1_1") (pintype "bidirectional"))
      (node (ref "J53") (pin "1") (pinfunction "1_1") (pintype "bidirectional"))
      (node (ref "J54") (pin "1") (pinfunction "1_1") (pintype "bidirectional"))
      (node (ref "J55") (pin "1") (pinfunction "1_1") (pintype "bidirectional"))
      (node (ref "J6") (pin "1") (pinfunction "1_1") (pintype "bidirectional"))
      (node (ref "J7") (pin "3") (pinfunction "P$3_3") (pintype "bidirectional"))
      (node (ref "J8") (pin "1") (pinfunction "1_1") (pintype "bidirectional"))
      (node (ref "J9") (pin "1") (pinfunction "1_1") (pintype "bidirectional"))
      (node (ref "K15_R10P") (pin "2") (pinfunction "2_2") (pintype "passive"))
      (node (ref "K15_R10P") (pin "3") (pinfunction "2_3") (pintype "passive"))
      (node (ref "K15_R10P") (pin "4") (pinfunction "2_4") (pintype "passive"))
      (node (ref "K15_R10P") (pin "5") (pinfunction "2_5") (pintype "passive"))
      (node (ref "K16_R10N") (pin "2") (pinfunction "2_2") (pintype "passive"))
      (node (ref "K16_R10N") (pin "3") (pinfunction "2_3") (pintype "passive"))
      (node (ref "K16_R10N") (pin "4") (pinfunction "2_4") (pintype "passive"))
      (node (ref "K16_R10N") (pin "5") (pinfunction "2_5") (pintype "passive"))
      (node (ref "L15_R11P") (pin "2") (pinfunction "2_2") (pintype "passive"))
      (node (ref "L15_R11P") (pin "3") (pinfunction "2_3") (pintype "passive"))
      (node (ref "L15_R11P") (pin "4") (pinfunction "2_4") (pintype "passive"))
      (node (ref "L15_R11P") (pin "5") (pinfunction "2_5") (pintype "passive"))
      (node (ref "L16_R11N") (pin "2") (pinfunction "2_2") (pintype "passive"))
      (node (ref "L16_R11N") (pin "3") (pinfunction "2_3") (pintype "passive"))
      (node (ref "L16_R11N") (pin "4") (pinfunction "2_4") (pintype "passive"))
      (node (ref "L16_R11N") (pin "5") (pinfunction "2_5") (pintype "passive"))
      (node (ref "M16CLK_3N") (pin "2") (pinfunction "2_2") (pintype "passive"))
      (node (ref "M16CLK_3N") (pin "3") (pinfunction "2_3") (pintype "passive"))
      (node (ref "M16CLK_3N") (pin "4") (pinfunction "2_4") (pintype "passive"))
      (node (ref "M16CLK_3N") (pin "5") (pinfunction "2_5") (pintype "passive"))
      (node (ref "N11") (pin "2") (pinfunction "2_2") (pintype "passive"))
      (node (ref "N11") (pin "3") (pinfunction "2_3") (pintype "passive"))
      (node (ref "N11") (pin "4") (pinfunction "2_4") (pintype "passive"))
      (node (ref "N11") (pin "5") (pinfunction "2_5") (pintype "passive"))
      (node (ref "N12") (pin "2") (pinfunction "2_2") (pintype "passive"))
      (node (ref "N12") (pin "3") (pinfunction "2_3") (pintype "passive"))
      (node (ref "N12") (pin "4") (pinfunction "2_4") (pintype "passive"))
      (node (ref "N12") (pin "5") (pinfunction "2_5") (pintype "passive"))
      (node (ref "N14") (pin "2") (pinfunction "2_2") (pintype "passive"))
      (node (ref "N14") (pin "3") (pinfunction "2_3") (pintype "passive"))
      (node (ref "N14") (pin "4") (pinfunction "2_4") (pintype "passive"))
      (node (ref "N14") (pin "5") (pinfunction "2_5") (pintype "passive"))
      (node (ref "N15_R13P") (pin "2") (pinfunction "2_2") (pintype "passive"))
      (node (ref "N15_R13P") (pin "3") (pinfunction "2_3") (pintype "passive"))
      (node (ref "N15_R13P") (pin "4") (pinfunction "2_4") (pintype "passive"))
      (node (ref "N15_R13P") (pin "5") (pinfunction "2_5") (pintype "passive"))
      (node (ref "N16_R13N") (pin "2") (pinfunction "2_2") (pintype "passive"))
      (node (ref "N16_R13N") (pin "3") (pinfunction "2_3") (pintype "passive"))
      (node (ref "N16_R13N") (pin "4") (pinfunction "2_4") (pintype "passive"))
      (node (ref "N16_R13N") (pin "5") (pinfunction "2_5") (pintype "passive"))
      (node (ref "OJ1") (pin "2") (pinfunction "2_2") (pintype "bidirectional"))
      (node (ref "OJ17") (pin "2") (pinfunction "2_2") (pintype "bidirectional"))
      (node (ref "OJ18") (pin "2") (pinfunction "2_2") (pintype "bidirectional"))
      (node (ref "OJ19") (pin "2") (pinfunction "2_2") (pintype "bidirectional"))
      (node (ref "OJ2") (pin "2") (pinfunction "2_2") (pintype "bidirectional"))
      (node (ref "OJ20") (pin "2") (pinfunction "2_2") (pintype "bidirectional"))
      (node (ref "OJ21") (pin "2") (pinfunction "2_2") (pintype "bidirectional"))
      (node (ref "OJ22") (pin "2") (pinfunction "2_2") (pintype "bidirectional"))
      (node (ref "OJ23") (pin "2") (pinfunction "2_2") (pintype "bidirectional"))
      (node (ref "OJ24") (pin "2") (pinfunction "2_2") (pintype "bidirectional"))
      (node (ref "OJ25") (pin "2") (pinfunction "2_2") (pintype "bidirectional"))
      (node (ref "OJ26") (pin "2") (pinfunction "2_2") (pintype "bidirectional"))
      (node (ref "OJ27") (pin "2") (pinfunction "2_2") (pintype "bidirectional"))
      (node (ref "OJ28") (pin "2") (pinfunction "2_2") (pintype "bidirectional"))
      (node (ref "OJ29") (pin "2") (pinfunction "2_2") (pintype "bidirectional"))
      (node (ref "OJ3") (pin "2") (pinfunction "2_2") (pintype "bidirectional"))
      (node (ref "OJ30") (pin "2") (pinfunction "2_2") (pintype "bidirectional"))
      (node (ref "OJ31") (pin "2") (pinfunction "2_2") (pintype "bidirectional"))
      (node (ref "OJ32") (pin "2") (pinfunction "2_2") (pintype "bidirectional"))
      (node (ref "OJ33") (pin "2") (pinfunction "2_2") (pintype "bidirectional"))
      (node (ref "OJ34") (pin "2") (pinfunction "2_2") (pintype "bidirectional"))
      (node (ref "OJ35") (pin "2") (pinfunction "2_2") (pintype "bidirectional"))
      (node (ref "OJ36") (pin "2") (pinfunction "2_2") (pintype "bidirectional"))
      (node (ref "OJ37") (pin "2") (pinfunction "2_2") (pintype "bidirectional"))
      (node (ref "OJ38") (pin "2") (pinfunction "2_2") (pintype "bidirectional"))
      (node (ref "OJ39") (pin "2") (pinfunction "2_2") (pintype "bidirectional"))
      (node (ref "OJ4") (pin "2") (pinfunction "2_2") (pintype "bidirectional"))
      (node (ref "OJ40") (pin "2") (pinfunction "2_2") (pintype "bidirectional"))
      (node (ref "OJ41") (pin "2") (pinfunction "2_2") (pintype "bidirectional"))
      (node (ref "OJ42") (pin "2") (pinfunction "2_2") (pintype "bidirectional"))
      (node (ref "OJ43") (pin "2") (pinfunction "2_2") (pintype "bidirectional"))
      (node (ref "OJ44") (pin "2") (pinfunction "2_2") (pintype "bidirectional"))
      (node (ref "OJ45") (pin "2") (pinfunction "2_2") (pintype "bidirectional"))
      (node (ref "OJ46") (pin "2") (pinfunction "2_2") (pintype "bidirectional"))
      (node (ref "OJ47") (pin "2") (pinfunction "2_2") (pintype "bidirectional"))
      (node (ref "OJ48") (pin "2") (pinfunction "2_2") (pintype "bidirectional"))
      (node (ref "OJ49") (pin "2") (pinfunction "2_2") (pintype "bidirectional"))
      (node (ref "OJ5") (pin "2") (pinfunction "2_2") (pintype "bidirectional"))
      (node (ref "OJ50") (pin "2") (pinfunction "2_2") (pintype "bidirectional"))
      (node (ref "OJ51") (pin "2") (pinfunction "2_2") (pintype "bidirectional"))
      (node (ref "OJ52") (pin "2") (pinfunction "2_2") (pintype "bidirectional"))
      (node (ref "OJ53") (pin "2") (pinfunction "2_2") (pintype "bidirectional"))
      (node (ref "OJ54") (pin "2") (pinfunction "2_2") (pintype "bidirectional"))
      (node (ref "OJ55") (pin "2") (pinfunction "2_2") (pintype "bidirectional"))
      (node (ref "OJ56") (pin "2") (pinfunction "2_2") (pintype "bidirectional"))
      (node (ref "OJ57") (pin "2") (pinfunction "2_2") (pintype "bidirectional"))
      (node (ref "OJ58") (pin "2") (pinfunction "2_2") (pintype "bidirectional"))
      (node (ref "OJ59") (pin "2") (pinfunction "2_2") (pintype "bidirectional"))
      (node (ref "OJ6") (pin "2") (pinfunction "2_2") (pintype "bidirectional"))
      (node (ref "OJ60") (pin "2") (pinfunction "2_2") (pintype "bidirectional"))
      (node (ref "OJ61") (pin "2") (pinfunction "2_2") (pintype "bidirectional"))
      (node (ref "OJ62") (pin "2") (pinfunction "2_2") (pintype "bidirectional"))
      (node (ref "OJ63") (pin "2") (pinfunction "2_2") (pintype "bidirectional"))
      (node (ref "OJ64") (pin "2") (pinfunction "2_2") (pintype "bidirectional"))
      (node (ref "OJ65") (pin "2") (pinfunction "2_2") (pintype "bidirectional"))
      (node (ref "OJ66") (pin "2") (pinfunction "2_2") (pintype "bidirectional"))
      (node (ref "OJ67") (pin "2") (pinfunction "2_2") (pintype "bidirectional"))
      (node (ref "OJ68") (pin "2") (pinfunction "2_2") (pintype "bidirectional"))
      (node (ref "OJ69") (pin "2") (pinfunction "2_2") (pintype "bidirectional"))
      (node (ref "OJ7") (pin "2") (pinfunction "2_2") (pintype "bidirectional"))
      (node (ref "OJ70") (pin "2") (pinfunction "2_2") (pintype "bidirectional"))
      (node (ref "OJ71") (pin "2") (pinfunction "2_2") (pintype "bidirectional"))
      (node (ref "OJ72") (pin "2") (pinfunction "2_2") (pintype "bidirectional"))
      (node (ref "OJ73") (pin "2") (pinfunction "2_2") (pintype "bidirectional"))
      (node (ref "OJ74") (pin "2") (pinfunction "2_2") (pintype "bidirectional"))
      (node (ref "OJ75") (pin "2") (pinfunction "2_2") (pintype "bidirectional"))
      (node (ref "OJ76") (pin "2") (pinfunction "2_2") (pintype "bidirectional"))
      (node (ref "OJ77") (pin "2") (pinfunction "2_2") (pintype "bidirectional"))
      (node (ref "OJ78") (pin "2") (pinfunction "2_2") (pintype "bidirectional"))
      (node (ref "OJ79") (pin "2") (pinfunction "2_2") (pintype "bidirectional"))
      (node (ref "OJ8") (pin "2") (pinfunction "2_2") (pintype "bidirectional"))
      (node (ref "OJ80") (pin "2") (pinfunction "2_2") (pintype "bidirectional"))
      (node (ref "OJ89") (pin "2") (pinfunction "2_2") (pintype "bidirectional"))
      (node (ref "OJ90") (pin "2") (pinfunction "2_2") (pintype "bidirectional"))
      (node (ref "OJ91") (pin "2") (pinfunction "2_2") (pintype "bidirectional"))
      (node (ref "OJ92") (pin "2") (pinfunction "2_2") (pintype "bidirectional"))
      (node (ref "OJ93") (pin "2") (pinfunction "2_2") (pintype "bidirectional"))
      (node (ref "OJ94") (pin "2") (pinfunction "2_2") (pintype "bidirectional"))
      (node (ref "OJ95") (pin "2") (pinfunction "2_2") (pintype "bidirectional"))
      (node (ref "OJ96") (pin "2") (pinfunction "2_2") (pintype "bidirectional"))
      (node (ref "P11") (pin "2") (pinfunction "2_2") (pintype "passive"))
      (node (ref "P11") (pin "3") (pinfunction "2_3") (pintype "passive"))
      (node (ref "P11") (pin "4") (pinfunction "2_4") (pintype "passive"))
      (node (ref "P11") (pin "5") (pinfunction "2_5") (pintype "passive"))
      (node (ref "P14_CLKOUT_4P") (pin "2") (pinfunction "2_2") (pintype "passive"))
      (node (ref "P14_CLKOUT_4P") (pin "3") (pinfunction "2_3") (pintype "passive"))
      (node (ref "P14_CLKOUT_4P") (pin "4") (pinfunction "2_4") (pintype "passive"))
      (node (ref "P14_CLKOUT_4P") (pin "5") (pinfunction "2_5") (pintype "passive"))
      (node (ref "P15") (pin "2") (pinfunction "2_2") (pintype "passive"))
      (node (ref "P15") (pin "3") (pinfunction "2_3") (pintype "passive"))
      (node (ref "P15") (pin "4") (pinfunction "2_4") (pintype "passive"))
      (node (ref "P15") (pin "5") (pinfunction "2_5") (pintype "passive"))
      (node (ref "P16_R15N") (pin "2") (pinfunction "2_2") (pintype "passive"))
      (node (ref "P16_R15N") (pin "3") (pinfunction "2_3") (pintype "passive"))
      (node (ref "P16_R15N") (pin "4") (pinfunction "2_4") (pintype "passive"))
      (node (ref "P16_R15N") (pin "5") (pinfunction "2_5") (pintype "passive"))
      (node (ref "P9") (pin "2") (pinfunction "2_2") (pintype "passive"))
      (node (ref "P9") (pin "3") (pinfunction "2_3") (pintype "passive"))
      (node (ref "P9") (pin "4") (pinfunction "2_4") (pintype "passive"))
      (node (ref "P9") (pin "5") (pinfunction "2_5") (pintype "passive"))
      (node (ref "PIN_AIN_PWRGND21") (pin "15") (pinfunction "15_15") (pintype "passive"))
      (node (ref "PIN_AIN_PWRGND21") (pin "16") (pinfunction "16_16") (pintype "passive"))
      (node (ref "PIN_ANALOG_21") (pin "15") (pinfunction "15_15") (pintype "passive"))
      (node (ref "PIN_ANALOG_21") (pin "16") (pinfunction "16_16") (pintype "passive"))
      (node (ref "PIN_ANALOG_21") (pin "2") (pinfunction "2_2") (pintype "passive"))
      (node (ref "R100") (pin "P$1") (pinfunction "1_P$1") (pintype "passive"))
      (node (ref "R10_B16P") (pin "2") (pinfunction "2_2") (pintype "passive"))
      (node (ref "R10_B16P") (pin "3") (pinfunction "2_3") (pintype "passive"))
      (node (ref "R10_B16P") (pin "4") (pinfunction "2_4") (pintype "passive"))
      (node (ref "R10_B16P") (pin "5") (pinfunction "2_5") (pintype "passive"))
      (node (ref "R11") (pin "P$1") (pinfunction "1_P$1") (pintype "passive"))
      (node (ref "R111") (pin "P$1") (pinfunction "1_P$1") (pintype "passive"))
      (node (ref "R12_B18P") (pin "2") (pinfunction "2_2") (pintype "passive"))
      (node (ref "R12_B18P") (pin "3") (pinfunction "2_3") (pintype "passive"))
      (node (ref "R12_B18P") (pin "4") (pinfunction "2_4") (pintype "passive"))
      (node (ref "R12_B18P") (pin "5") (pinfunction "2_5") (pintype "passive"))
      (node (ref "R13_B20P") (pin "2") (pinfunction "2_2") (pintype "passive"))
      (node (ref "R13_B20P") (pin "3") (pinfunction "2_3") (pintype "passive"))
      (node (ref "R13_B20P") (pin "4") (pinfunction "2_4") (pintype "passive"))
      (node (ref "R13_B20P") (pin "5") (pinfunction "2_5") (pintype "passive"))
      (node (ref "R141") (pin "P$1") (pinfunction "1_P$1") (pintype "passive"))
      (node (ref "R14_CLKOUT_4N") (pin "2") (pinfunction "2_2") (pintype "passive"))
      (node (ref "R14_CLKOUT_4N") (pin "3") (pinfunction "2_3") (pintype "passive"))
      (node (ref "R14_CLKOUT_4N") (pin "4") (pinfunction "2_4") (pintype "passive"))
      (node (ref "R14_CLKOUT_4N") (pin "5") (pinfunction "2_5") (pintype "passive"))
      (node (ref "R15") (pin "P$1") (pinfunction "1_P$1") (pintype "passive"))
      (node (ref "R161") (pin "P$1") (pinfunction "1_P$1") (pintype "passive"))
      (node (ref "R16_R15P") (pin "2") (pinfunction "2_2") (pintype "passive"))
      (node (ref "R16_R15P") (pin "3") (pinfunction "2_3") (pintype "passive"))
      (node (ref "R16_R15P") (pin "4") (pinfunction "2_4") (pintype "passive"))
      (node (ref "R16_R15P") (pin "5") (pinfunction "2_5") (pintype "passive"))
      (node (ref "R18") (pin "P$1") (pinfunction "1_P$1") (pintype "passive"))
      (node (ref "R19") (pin "P$1") (pinfunction "1_P$1") (pintype "passive"))
      (node (ref "R20") (pin "P$1") (pinfunction "1_P$1") (pintype "passive"))
      (node (ref "R21") (pin "P$1") (pinfunction "1_P$1") (pintype "passive"))
      (node (ref "R22") (pin "P$1") (pinfunction "1_P$1") (pintype "passive"))
      (node (ref "R23") (pin "P$1") (pinfunction "1_P$1") (pintype "passive"))
      (node (ref "R24") (pin "P$1") (pinfunction "1_P$1") (pintype "passive"))
      (node (ref "R25") (pin "P$1") (pinfunction "1_P$1") (pintype "passive"))
      (node (ref "R26") (pin "P$1") (pinfunction "1_P$1") (pintype "passive"))
      (node (ref "R27") (pin "P$1") (pinfunction "1_P$1") (pintype "passive"))
      (node (ref "R28") (pin "P$1") (pinfunction "1_P$1") (pintype "passive"))
      (node (ref "R29") (pin "P$1") (pinfunction "1_P$1") (pintype "passive"))
      (node (ref "R30") (pin "P$1") (pinfunction "1_P$1") (pintype "passive"))
      (node (ref "R31") (pin "P$1") (pinfunction "1_P$1") (pintype "passive"))
      (node (ref "R32") (pin "P$1") (pinfunction "1_P$1") (pintype "passive"))
      (node (ref "R33") (pin "P$1") (pinfunction "1_P$1") (pintype "passive"))
      (node (ref "R35") (pin "P$1") (pinfunction "1_P$1") (pintype "passive"))
      (node (ref "R39") (pin "P$1") (pinfunction "1_P$1") (pintype "passive"))
      (node (ref "R4") (pin "P$1") (pinfunction "1_P$1") (pintype "passive"))
      (node (ref "R40") (pin "P$1") (pinfunction "1_P$1") (pintype "passive"))
      (node (ref "R41") (pin "P$1") (pinfunction "1_P$1") (pintype "passive"))
      (node (ref "R43") (pin "P$1") (pinfunction "1_P$1") (pintype "passive"))
      (node (ref "R45") (pin "P$1") (pinfunction "1_P$1") (pintype "passive"))
      (node (ref "R46") (pin "P$1") (pinfunction "1_P$1") (pintype "passive"))
      (node (ref "R47") (pin "P$1") (pinfunction "1_P$1") (pintype "passive"))
      (node (ref "R49") (pin "P$1") (pinfunction "1_P$1") (pintype "passive"))
      (node (ref "R5") (pin "P$1") (pinfunction "1_P$1") (pintype "passive"))
      (node (ref "R50") (pin "P$1") (pinfunction "1_P$1") (pintype "passive"))
      (node (ref "R51") (pin "P$1") (pinfunction "1_P$1") (pintype "passive"))
      (node (ref "R52") (pin "P$1") (pinfunction "1_P$1") (pintype "passive"))
      (node (ref "R53") (pin "P$1") (pinfunction "1_P$1") (pintype "passive"))
      (node (ref "R6") (pin "P$1") (pinfunction "1_P$1") (pintype "passive"))
      (node (ref "R8") (pin "2") (pinfunction "2_2") (pintype "passive"))
      (node (ref "R9") (pin "P$1") (pinfunction "1_P$1") (pintype "passive"))
      (node (ref "R91") (pin "P$1") (pinfunction "1_P$1") (pintype "passive"))
      (node (ref "R9CLK_7P_CLKIN") (pin "2") (pinfunction "2_2") (pintype "passive"))
      (node (ref "R9CLK_7P_CLKIN") (pin "3") (pinfunction "2_3") (pintype "passive"))
      (node (ref "R9CLK_7P_CLKIN") (pin "4") (pinfunction "2_4") (pintype "passive"))
      (node (ref "R9CLK_7P_CLKIN") (pin "5") (pinfunction "2_5") (pintype "passive"))
      (node (ref "SV1") (pin "12") (pinfunction "12_12") (pintype "passive"))
      (node (ref "SV1") (pin "30") (pinfunction "30_30") (pintype "passive"))
      (node (ref "SV2") (pin "12") (pinfunction "12_12") (pintype "passive"))
      (node (ref "SV2") (pin "30") (pinfunction "30_30") (pintype "passive"))
      (node (ref "T10_B16N") (pin "2") (pinfunction "2_2") (pintype "passive"))
      (node (ref "T10_B16N") (pin "3") (pinfunction "2_3") (pintype "passive"))
      (node (ref "T10_B16N") (pin "4") (pinfunction "2_4") (pintype "passive"))
      (node (ref "T10_B16N") (pin "5") (pinfunction "2_5") (pintype "passive"))
      (node (ref "T12_B18N") (pin "2") (pinfunction "2_2") (pintype "passive"))
      (node (ref "T12_B18N") (pin "3") (pinfunction "2_3") (pintype "passive"))
      (node (ref "T12_B18N") (pin "4") (pinfunction "2_4") (pintype "passive"))
      (node (ref "T12_B18N") (pin "5") (pinfunction "2_5") (pintype "passive"))
      (node (ref "T13_B20N") (pin "2") (pinfunction "2_2") (pintype "passive"))
      (node (ref "T13_B20N") (pin "3") (pinfunction "2_3") (pintype "passive"))
      (node (ref "T13_B20N") (pin "4") (pinfunction "2_4") (pintype "passive"))
      (node (ref "T13_B20N") (pin "5") (pinfunction "2_5") (pintype "passive"))
      (node (ref "T14_B23P_SPARE") (pin "2") (pinfunction "2_2") (pintype "passive"))
      (node (ref "T14_B23P_SPARE") (pin "3") (pinfunction "2_3") (pintype "passive"))
      (node (ref "T14_B23P_SPARE") (pin "4") (pinfunction "2_4") (pintype "passive"))
      (node (ref "T14_B23P_SPARE") (pin "5") (pinfunction "2_5") (pintype "passive"))
      (node (ref "T15_B23N_TRIGOUT") (pin "2") (pinfunction "2_2") (pintype "passive"))
      (node (ref "T15_B23N_TRIGOUT") (pin "3") (pinfunction "2_3") (pintype "passive"))
      (node (ref "T15_B23N_TRIGOUT") (pin "4") (pinfunction "2_4") (pintype "passive"))
      (node (ref "T15_B23N_TRIGOUT") (pin "5") (pinfunction "2_5") (pintype "passive"))
      (node (ref "T9CLK_7N") (pin "2") (pinfunction "2_2") (pintype "passive"))
      (node (ref "T9CLK_7N") (pin "3") (pinfunction "2_3") (pintype "passive"))
      (node (ref "T9CLK_7N") (pin "4") (pinfunction "2_4") (pintype "passive"))
      (node (ref "T9CLK_7N") (pin "5") (pinfunction "2_5") (pintype "passive"))
      (node (ref "VSLUE") (pin "10") (pinfunction "GND_10") (pintype "power_in"))
      (node (ref "VSLUE11") (pin "10") (pinfunction "GND_10") (pintype "power_in"))
      (node (ref "VSLUE2") (pin "10") (pinfunction "GND_10") (pintype "power_in"))
      (node (ref "VSLUE3") (pin "10") (pinfunction "GND_10") (pintype "power_in"))
      (node (ref "VSLUE4") (pin "10") (pinfunction "GND_10") (pintype "power_in"))
      (node (ref "VSLUE5") (pin "10") (pinfunction "GND_10") (pintype "power_in"))
      (node (ref "VSLUE6") (pin "10") (pinfunction "GND_10") (pintype "power_in"))
      (node (ref "VSLUE7") (pin "10") (pinfunction "GND_10") (pintype "power_in"))
      (node (ref "VSLUE8") (pin "10") (pinfunction "GND_10") (pintype "power_in"))
      (node (ref "VSLUE9") (pin "10") (pinfunction "GND_10") (pintype "power_in"))
    )
    (net (code "100") (name "Net-(LED1-PadC)") (class "Default")
      (node (ref "LED1") (pin "C") (pinfunction "C_C") (pintype "passive"))
      (node (ref "R8") (pin "1") (pinfunction "1_1") (pintype "passive"))
    )
    (net (code "101") (name "Net-(VSLUE-1Y1)") (class "Default")
      (node (ref "J14") (pin "1") (pinfunction "1_1") (pintype "passive"))
      (node (ref "OJ1") (pin "1") (pinfunction "1_1") (pintype "bidirectional"))
      (node (ref "VSLUE") (pin "16") (pinfunction "1Y2_16") (pintype "output"))
      (node (ref "VSLUE") (pin "18") (pinfunction "1Y1_18") (pintype "output"))
    )
    (net (code "102") (name "Net-(VSLUE-1Y3)") (class "Default")
      (node (ref "D11") (pin "1") (pinfunction "1_1") (pintype "passive"))
      (node (ref "OJ2") (pin "1") (pinfunction "1_1") (pintype "bidirectional"))
      (node (ref "VSLUE") (pin "12") (pinfunction "1Y4_12") (pintype "output"))
      (node (ref "VSLUE") (pin "14") (pinfunction "1Y3_14") (pintype "output"))
    )
    (net (code "103") (name "Net-(VSLUE-2Y1)") (class "Default")
      (node (ref "B11") (pin "1") (pinfunction "1_1") (pintype "passive"))
      (node (ref "OJ3") (pin "1") (pinfunction "1_1") (pintype "bidirectional"))
      (node (ref "VSLUE") (pin "7") (pinfunction "2Y2_7") (pintype "output"))
      (node (ref "VSLUE") (pin "9") (pinfunction "2Y1_9") (pintype "output"))
    )
    (net (code "104") (name "Net-(VSLUE-2Y3)") (class "Default")
      (node (ref "E10") (pin "1") (pinfunction "1_1") (pintype "passive"))
      (node (ref "OJ4") (pin "1") (pinfunction "1_1") (pintype "bidirectional"))
      (node (ref "VSLUE") (pin "3") (pinfunction "2Y4_3") (pintype "output"))
      (node (ref "VSLUE") (pin "5") (pinfunction "2Y3_5") (pintype "output"))
    )
    (net (code "105") (name "Net-(VSLUE2-1Y1)") (class "Default")
      (node (ref "N12") (pin "1") (pinfunction "1_1") (pintype "passive"))
      (node (ref "OJ20") (pin "1") (pinfunction "1_1") (pintype "bidirectional"))
      (node (ref "VSLUE2") (pin "16") (pinfunction "1Y2_16") (pintype "output"))
      (node (ref "VSLUE2") (pin "18") (pinfunction "1Y1_18") (pintype "output"))
    )
    (net (code "106") (name "Net-(VSLUE2-1Y3)") (class "Default")
      (node (ref "E9") (pin "1") (pinfunction "1_1") (pintype "passive"))
      (node (ref "OJ19") (pin "1") (pinfunction "1_1") (pintype "bidirectional"))
      (node (ref "VSLUE2") (pin "12") (pinfunction "1Y4_12") (pintype "output"))
      (node (ref "VSLUE2") (pin "14") (pinfunction "1Y3_14") (pintype "output"))
    )
    (net (code "107") (name "Net-(VSLUE2-2Y1)") (class "Default")
      (node (ref "B16") (pin "1") (pinfunction "1_1") (pintype "passive"))
      (node (ref "OJ18") (pin "1") (pinfunction "1_1") (pintype "bidirectional"))
      (node (ref "VSLUE2") (pin "7") (pinfunction "2Y2_7") (pintype "output"))
      (node (ref "VSLUE2") (pin "9") (pinfunction "2Y1_9") (pintype "output"))
    )
    (net (code "108") (name "Net-(VSLUE2-2Y3)") (class "Default")
      (node (ref "D8") (pin "1") (pinfunction "1_1") (pintype "passive"))
      (node (ref "OJ17") (pin "1") (pinfunction "1_1") (pintype "bidirectional"))
      (node (ref "VSLUE2") (pin "3") (pinfunction "2Y4_3") (pintype "output"))
      (node (ref "VSLUE2") (pin "5") (pinfunction "2Y3_5") (pintype "output"))
    )
    (net (code "109") (name "Net-(VSLUE3-1Y1)") (class "Default")
      (node (ref "C15") (pin "1") (pinfunction "1_1") (pintype "passive"))
      (node (ref "OJ28") (pin "1") (pinfunction "1_1") (pintype "bidirectional"))
      (node (ref "VSLUE3") (pin "16") (pinfunction "1Y2_16") (pintype "output"))
      (node (ref "VSLUE3") (pin "18") (pinfunction "1Y1_18") (pintype "output"))
    )
    (net (code "110") (name "Net-(VSLUE3-1Y3)") (class "Default")
      (node (ref "C14") (pin "1") (pinfunction "1_1") (pintype "passive"))
      (node (ref "OJ27") (pin "1") (pinfunction "1_1") (pintype "bidirectional"))
      (node (ref "VSLUE3") (pin "12") (pinfunction "1Y4_12") (pintype "output"))
      (node (ref "VSLUE3") (pin "14") (pinfunction "1Y3_14") (pintype "output"))
    )
    (net (code "111") (name "Net-(VSLUE3-2Y1)") (class "Default")
      (node (ref "F14") (pin "1") (pinfunction "1_1") (pintype "passive"))
      (node (ref "OJ26") (pin "1") (pinfunction "1_1") (pintype "bidirectional"))
      (node (ref "VSLUE3") (pin "7") (pinfunction "2Y2_7") (pintype "output"))
      (node (ref "VSLUE3") (pin "9") (pinfunction "2Y1_9") (pintype "output"))
    )
    (net (code "112") (name "Net-(VSLUE3-2Y3)") (class "Default")
      (node (ref "D15") (pin "1") (pinfunction "1_1") (pintype "passive"))
      (node (ref "OJ25") (pin "1") (pinfunction "1_1") (pintype "bidirectional"))
      (node (ref "VSLUE3") (pin "3") (pinfunction "2Y4_3") (pintype "output"))
      (node (ref "VSLUE3") (pin "5") (pinfunction "2Y3_5") (pintype "output"))
    )
    (net (code "113") (name "Net-(VSLUE4-1Y1)") (class "Default")
      (node (ref "D16") (pin "1") (pinfunction "1_1") (pintype "passive"))
      (node (ref "OJ36") (pin "1") (pinfunction "1_1") (pintype "bidirectional"))
      (node (ref "VSLUE4") (pin "16") (pinfunction "1Y2_16") (pintype "output"))
      (node (ref "VSLUE4") (pin "18") (pinfunction "1Y1_18") (pintype "output"))
    )
    (net (code "114") (name "Net-(VSLUE4-1Y3)") (class "Default")
      (node (ref "D14") (pin "1") (pinfunction "1_1") (pintype "passive"))
      (node (ref "OJ35") (pin "1") (pinfunction "1_1") (pintype "bidirectional"))
      (node (ref "VSLUE4") (pin "12") (pinfunction "1Y4_12") (pintype "output"))
      (node (ref "VSLUE4") (pin "14") (pinfunction "1Y3_14") (pintype "output"))
    )
    (net (code "115") (name "Net-(VSLUE4-2Y1)") (class "Default")
      (node (ref "F16") (pin "1") (pinfunction "1_1") (pintype "passive"))
      (node (ref "OJ34") (pin "1") (pinfunction "1_1") (pintype "bidirectional"))
      (node (ref "VSLUE4") (pin "7") (pinfunction "2Y2_7") (pintype "output"))
      (node (ref "VSLUE4") (pin "9") (pinfunction "2Y1_9") (pintype "output"))
    )
    (net (code "116") (name "Net-(VSLUE4-2Y3)") (class "Default")
      (node (ref "F15") (pin "1") (pinfunction "1_1") (pintype "passive"))
      (node (ref "OJ33") (pin "1") (pinfunction "1_1") (pintype "bidirectional"))
      (node (ref "VSLUE4") (pin "3") (pinfunction "2Y4_3") (pintype "output"))
      (node (ref "VSLUE4") (pin "5") (pinfunction "2Y3_5") (pintype "output"))
    )
    (net (code "117") (name "Net-(VSLUE5-1Y1)") (class "Default")
      (node (ref "B6") (pin "1") (pinfunction "1_1") (pintype "passive"))
      (node (ref "OJ44") (pin "1") (pinfunction "1_1") (pintype "bidirectional"))
      (node (ref "VSLUE5") (pin "16") (pinfunction "1Y2_16") (pintype "output"))
      (node (ref "VSLUE5") (pin "18") (pinfunction "1Y1_18") (pintype "output"))
    )
    (net (code "118") (name "Net-(VSLUE5-1Y3)") (class "Default")
      (node (ref "A6") (pin "1") (pinfunction "1_1") (pintype "passive"))
      (node (ref "OJ43") (pin "1") (pinfunction "1_1") (pintype "bidirectional"))
      (node (ref "VSLUE5") (pin "12") (pinfunction "1Y4_12") (pintype "output"))
      (node (ref "VSLUE5") (pin "14") (pinfunction "1Y3_14") (pintype "output"))
    )
    (net (code "119") (name "Net-(VSLUE5-2Y1)") (class "Default")
      (node (ref "N11") (pin "1") (pinfunction "1_1") (pintype "passive"))
      (node (ref "OJ42") (pin "1") (pinfunction "1_1") (pintype "bidirectional"))
      (node (ref "VSLUE5") (pin "7") (pinfunction "2Y2_7") (pintype "output"))
      (node (ref "VSLUE5") (pin "9") (pinfunction "2Y1_9") (pintype "output"))
    )
    (net (code "120") (name "Net-(VSLUE5-2Y3)") (class "Default")
      (node (ref "OJ41") (pin "1") (pinfunction "1_1") (pintype "bidirectional"))
      (node (ref "P9") (pin "1") (pinfunction "1_1") (pintype "passive"))
      (node (ref "VSLUE5") (pin "3") (pinfunction "2Y4_3") (pintype "output"))
      (node (ref "VSLUE5") (pin "5") (pinfunction "2Y3_5") (pintype "output"))
    )
    (net (code "121") (name "Net-(VSLUE6-1Y1)") (class "Default")
      (node (ref "D6") (pin "1") (pinfunction "1_1") (pintype "passive"))
      (node (ref "OJ52") (pin "1") (pinfunction "1_1") (pintype "bidirectional"))
      (node (ref "VSLUE6") (pin "16") (pinfunction "1Y2_16") (pintype "output"))
      (node (ref "VSLUE6") (pin "18") (pinfunction "1Y1_18") (pintype "output"))
    )
    (net (code "122") (name "Net-(VSLUE6-1Y3)") (class "Default")
      (node (ref "C6") (pin "1") (pinfunction "1_1") (pintype "passive"))
      (node (ref "OJ51") (pin "1") (pinfunction "1_1") (pintype "bidirectional"))
      (node (ref "VSLUE6") (pin "12") (pinfunction "1Y4_12") (pintype "output"))
      (node (ref "VSLUE6") (pin "14") (pinfunction "1Y3_14") (pintype "output"))
    )
    (net (code "123") (name "Net-(VSLUE6-2Y1)") (class "Default")
      (node (ref "E6") (pin "1") (pinfunction "1_1") (pintype "passive"))
      (node (ref "OJ50") (pin "1") (pinfunction "1_1") (pintype "bidirectional"))
      (node (ref "VSLUE6") (pin "7") (pinfunction "2Y2_7") (pintype "output"))
      (node (ref "VSLUE6") (pin "9") (pinfunction "2Y1_9") (pintype "output"))
    )
    (net (code "124") (name "Net-(VSLUE6-2Y3)") (class "Default")
      (node (ref "C8") (pin "1") (pinfunction "1_1") (pintype "passive"))
      (node (ref "OJ49") (pin "1") (pinfunction "1_1") (pintype "bidirectional"))
      (node (ref "VSLUE6") (pin "3") (pinfunction "2Y4_3") (pintype "output"))
      (node (ref "VSLUE6") (pin "5") (pinfunction "2Y3_5") (pintype "output"))
    )
    (net (code "125") (name "Net-(VSLUE7-1Y1)") (class "Default")
      (node (ref "C16") (pin "1") (pinfunction "1_1") (pintype "passive"))
      (node (ref "OJ60") (pin "1") (pinfunction "1_1") (pintype "bidirectional"))
      (node (ref "VSLUE7") (pin "16") (pinfunction "1Y2_16") (pintype "output"))
      (node (ref "VSLUE7") (pin "18") (pinfunction "1Y1_18") (pintype "output"))
    )
    (net (code "126") (name "Net-(VSLUE7-1Y3)") (class "Default")
      (node (ref "E7") (pin "1") (pinfunction "1_1") (pintype "passive"))
      (node (ref "OJ59") (pin "1") (pinfunction "1_1") (pintype "bidirectional"))
      (node (ref "VSLUE7") (pin "12") (pinfunction "1Y4_12") (pintype "output"))
      (node (ref "VSLUE7") (pin "14") (pinfunction "1Y3_14") (pintype "output"))
    )
    (net (code "127") (name "Net-(VSLUE7-2Y1)") (class "Default")
      (node (ref "F9") (pin "1") (pinfunction "1_1") (pintype "passive"))
      (node (ref "OJ58") (pin "1") (pinfunction "1_1") (pintype "bidirectional"))
      (node (ref "VSLUE7") (pin "7") (pinfunction "2Y2_7") (pintype "output"))
      (node (ref "VSLUE7") (pin "9") (pinfunction "2Y1_9") (pintype "output"))
    )
    (net (code "128") (name "Net-(VSLUE7-2Y3)") (class "Default")
      (node (ref "OJ57") (pin "1") (pinfunction "1_1") (pintype "bidirectional"))
      (node (ref "P15") (pin "1") (pinfunction "1_1") (pintype "passive"))
      (node (ref "VSLUE7") (pin "3") (pinfunction "2Y4_3") (pintype "output"))
      (node (ref "VSLUE7") (pin "5") (pinfunction "2Y3_5") (pintype "output"))
    )
    (net (code "129") (name "Net-(VSLUE8-1Y1)") (class "Default")
      (node (ref "B5") (pin "1") (pinfunction "1_1") (pintype "passive"))
      (node (ref "OJ68") (pin "1") (pinfunction "1_1") (pintype "bidirectional"))
      (node (ref "VSLUE8") (pin "16") (pinfunction "1Y2_16") (pintype "output"))
      (node (ref "VSLUE8") (pin "18") (pinfunction "1Y1_18") (pintype "output"))
    )
    (net (code "130") (name "Net-(VSLUE8-1Y3)") (class "Default")
      (node (ref "A5") (pin "1") (pinfunction "1_1") (pintype "passive"))
      (node (ref "OJ67") (pin "1") (pinfunction "1_1") (pintype "bidirectional"))
      (node (ref "VSLUE8") (pin "12") (pinfunction "1Y4_12") (pintype "output"))
      (node (ref "VSLUE8") (pin "14") (pinfunction "1Y3_14") (pintype "output"))
    )
    (net (code "131") (name "Net-(VSLUE8-2Y1)") (class "Default")
      (node (ref "N14") (pin "1") (pinfunction "1_1") (pintype "passive"))
      (node (ref "OJ66") (pin "1") (pinfunction "1_1") (pintype "bidirectional"))
      (node (ref "VSLUE8") (pin "7") (pinfunction "2Y2_7") (pintype "output"))
      (node (ref "VSLUE8") (pin "9") (pinfunction "2Y1_9") (pintype "output"))
    )
    (net (code "132") (name "Net-(VSLUE8-2Y3)") (class "Default")
      (node (ref "D5") (pin "1") (pinfunction "1_1") (pintype "passive"))
      (node (ref "OJ65") (pin "1") (pinfunction "1_1") (pintype "bidirectional"))
      (node (ref "VSLUE8") (pin "3") (pinfunction "2Y4_3") (pintype "output"))
      (node (ref "VSLUE8") (pin "5") (pinfunction "2Y3_5") (pintype "output"))
    )
    (net (code "133") (name "Net-(VSLUE9-1Y1)") (class "Default")
      (node (ref "E11") (pin "1") (pinfunction "1_1") (pintype "passive"))
      (node (ref "OJ76") (pin "1") (pinfunction "1_1") (pintype "bidirectional"))
      (node (ref "VSLUE9") (pin "16") (pinfunction "1Y2_16") (pintype "output"))
      (node (ref "VSLUE9") (pin "18") (pinfunction "1Y1_18") (pintype "output"))
    )
    (net (code "134") (name "Net-(VSLUE9-1Y3)") (class "Default")
      (node (ref "OJ75") (pin "1") (pinfunction "1_1") (pintype "bidirectional"))
      (node (ref "P11") (pin "1") (pinfunction "1_1") (pintype "passive"))
      (node (ref "VSLUE9") (pin "12") (pinfunction "1Y4_12") (pintype "output"))
      (node (ref "VSLUE9") (pin "14") (pinfunction "1Y3_14") (pintype "output"))
    )
    (net (code "135") (name "Net-(VSLUE9-2Y1)") (class "Default")
      (node (ref "C11") (pin "1") (pinfunction "1_1") (pintype "passive"))
      (node (ref "OJ74") (pin "1") (pinfunction "1_1") (pintype "bidirectional"))
      (node (ref "VSLUE9") (pin "7") (pinfunction "2Y2_7") (pintype "output"))
      (node (ref "VSLUE9") (pin "9") (pinfunction "2Y1_9") (pintype "output"))
    )
    (net (code "136") (name "Net-(VSLUE9-2Y3)") (class "Default")
      (node (ref "J13") (pin "1") (pinfunction "1_1") (pintype "passive"))
      (node (ref "OJ73") (pin "1") (pinfunction "1_1") (pintype "bidirectional"))
      (node (ref "VSLUE9") (pin "3") (pinfunction "2Y4_3") (pintype "output"))
      (node (ref "VSLUE9") (pin "5") (pinfunction "2Y3_5") (pintype "output"))
    )
    (net (code "137") (name "Net-(VSLUE11-1Y1)") (class "Default")
      (node (ref "D12") (pin "1") (pinfunction "1_1") (pintype "passive"))
      (node (ref "OJ92") (pin "1") (pinfunction "1_1") (pintype "bidirectional"))
      (node (ref "VSLUE11") (pin "16") (pinfunction "1Y2_16") (pintype "output"))
      (node (ref "VSLUE11") (pin "18") (pinfunction "1Y1_18") (pintype "output"))
    )
    (net (code "138") (name "Net-(VSLUE11-1Y3)") (class "Default")
      (node (ref "B3") (pin "1") (pinfunction "1_1") (pintype "passive"))
      (node (ref "OJ91") (pin "1") (pinfunction "1_1") (pintype "bidirectional"))
      (node (ref "VSLUE11") (pin "12") (pinfunction "1Y4_12") (pintype "output"))
      (node (ref "VSLUE11") (pin "14") (pinfunction "1Y3_14") (pintype "output"))
    )
    (net (code "139") (name "Net-(VSLUE11-2Y1)") (class "Default")
      (node (ref "B4") (pin "1") (pinfunction "1_1") (pintype "passive"))
      (node (ref "OJ90") (pin "1") (pinfunction "1_1") (pintype "bidirectional"))
      (node (ref "VSLUE11") (pin "7") (pinfunction "2Y2_7") (pintype "output"))
      (node (ref "VSLUE11") (pin "9") (pinfunction "2Y1_9") (pintype "output"))
    )
    (net (code "140") (name "Net-(VSLUE11-2Y3)") (class "Default")
      (node (ref "A4") (pin "1") (pinfunction "1_1") (pintype "passive"))
      (node (ref "OJ89") (pin "1") (pinfunction "1_1") (pintype "bidirectional"))
      (node (ref "VSLUE11") (pin "3") (pinfunction "2Y4_3") (pintype "output"))
      (node (ref "VSLUE11") (pin "5") (pinfunction "2Y3_5") (pintype "output"))
    )
    (net (code "141") (name "unconnected-(J2-Pad1)") (class "Default")
      (node (ref "J2") (pin "1") (pinfunction "1_1") (pintype "passive"))
    )
    (net (code "142") (name "unconnected-(J2-Pad2)") (class "Default")
      (node (ref "J2") (pin "2") (pinfunction "2_2") (pintype "passive"))
    )
    (net (code "143") (name "unconnected-(J2-Pad3)") (class "Default")
      (node (ref "J2") (pin "3") (pinfunction "3_3") (pintype "passive"))
    )
    (net (code "144") (name "unconnected-(J2-Pad4)") (class "Default")
      (node (ref "J2") (pin "4") (pinfunction "4_4") (pintype "passive"))
    )
    (net (code "145") (name "unconnected-(J2-Pad5)") (class "Default")
      (node (ref "J2") (pin "5") (pinfunction "5_5") (pintype "passive"))
    )
    (net (code "146") (name "unconnected-(J2-Pad6)") (class "Default")
      (node (ref "J2") (pin "6") (pinfunction "6_6") (pintype "passive"))
    )
    (net (code "147") (name "unconnected-(J2-Pad7)") (class "Default")
      (node (ref "J2") (pin "7") (pinfunction "7_7") (pintype "passive"))
    )
    (net (code "148") (name "unconnected-(J2-Pad8)") (class "Default")
      (node (ref "J2") (pin "8") (pinfunction "8_8") (pintype "passive"))
    )
    (net (code "149") (name "unconnected-(J2-Pad9)") (class "Default")
      (node (ref "J2") (pin "9") (pinfunction "9_9") (pintype "passive"))
    )
    (net (code "150") (name "unconnected-(J2-Pad10)") (class "Default")
      (node (ref "J2") (pin "10") (pinfunction "10_10") (pintype "passive"))
    )
    (net (code "151") (name "unconnected-(J2-Pad11)") (class "Default")
      (node (ref "J2") (pin "11") (pinfunction "11_11") (pintype "passive"))
    )
    (net (code "152") (name "unconnected-(J2-Pad12)") (class "Default")
      (node (ref "J2") (pin "12") (pinfunction "12_12") (pintype "passive"))
    )
    (net (code "153") (name "unconnected-(J2-Pad13)") (class "Default")
      (node (ref "J2") (pin "13") (pinfunction "13_13") (pintype "passive"))
    )
    (net (code "154") (name "unconnected-(J2-Pad14)") (class "Default")
      (node (ref "J2") (pin "14") (pinfunction "14_14") (pintype "passive"))
    )
    (net (code "155") (name "unconnected-(J2-Pad15)") (class "Default")
      (node (ref "J2") (pin "15") (pinfunction "15_15") (pintype "passive"))
    )
    (net (code "156") (name "unconnected-(J2-Pad16)") (class "Default")
      (node (ref "J2") (pin "16") (pinfunction "16_16") (pintype "passive"))
    )
    (net (code "157") (name "unconnected-(J2-Pad17)") (class "Default")
      (node (ref "J2") (pin "17") (pinfunction "17_17") (pintype "passive"))
    )
    (net (code "158") (name "unconnected-(J2-Pad18)") (class "Default")
      (node (ref "J2") (pin "18") (pinfunction "18_18") (pintype "passive"))
    )
    (net (code "159") (name "unconnected-(J2-Pad19)") (class "Default")
      (node (ref "J2") (pin "19") (pinfunction "19_19") (pintype "passive"))
    )
    (net (code "160") (name "unconnected-(J2-Pad20)") (class "Default")
      (node (ref "J2") (pin "20") (pinfunction "20_20") (pintype "passive"))
    )
    (net (code "161") (name "unconnected-(J2-Pad21)") (class "Default")
      (node (ref "J2") (pin "21") (pinfunction "21_21") (pintype "passive"))
    )
    (net (code "162") (name "unconnected-(J2-Pad22)") (class "Default")
      (node (ref "J2") (pin "22") (pinfunction "22_22") (pintype "passive"))
    )
    (net (code "163") (name "unconnected-(J2-Pad23)") (class "Default")
      (node (ref "J2") (pin "23") (pinfunction "23_23") (pintype "passive"))
    )
    (net (code "164") (name "unconnected-(J2-Pad24)") (class "Default")
      (node (ref "J2") (pin "24") (pinfunction "24_24") (pintype "passive"))
    )
    (net (code "165") (name "unconnected-(J2-Pad25)") (class "Default")
      (node (ref "J2") (pin "25") (pinfunction "25_25") (pintype "passive"))
    )
    (net (code "166") (name "unconnected-(J2-Pad26)") (class "Default")
      (node (ref "J2") (pin "26") (pinfunction "26_26") (pintype "passive"))
    )
  )
)
